# ADCS.net
KiCad netlist of a schematic drawn in EAGLE
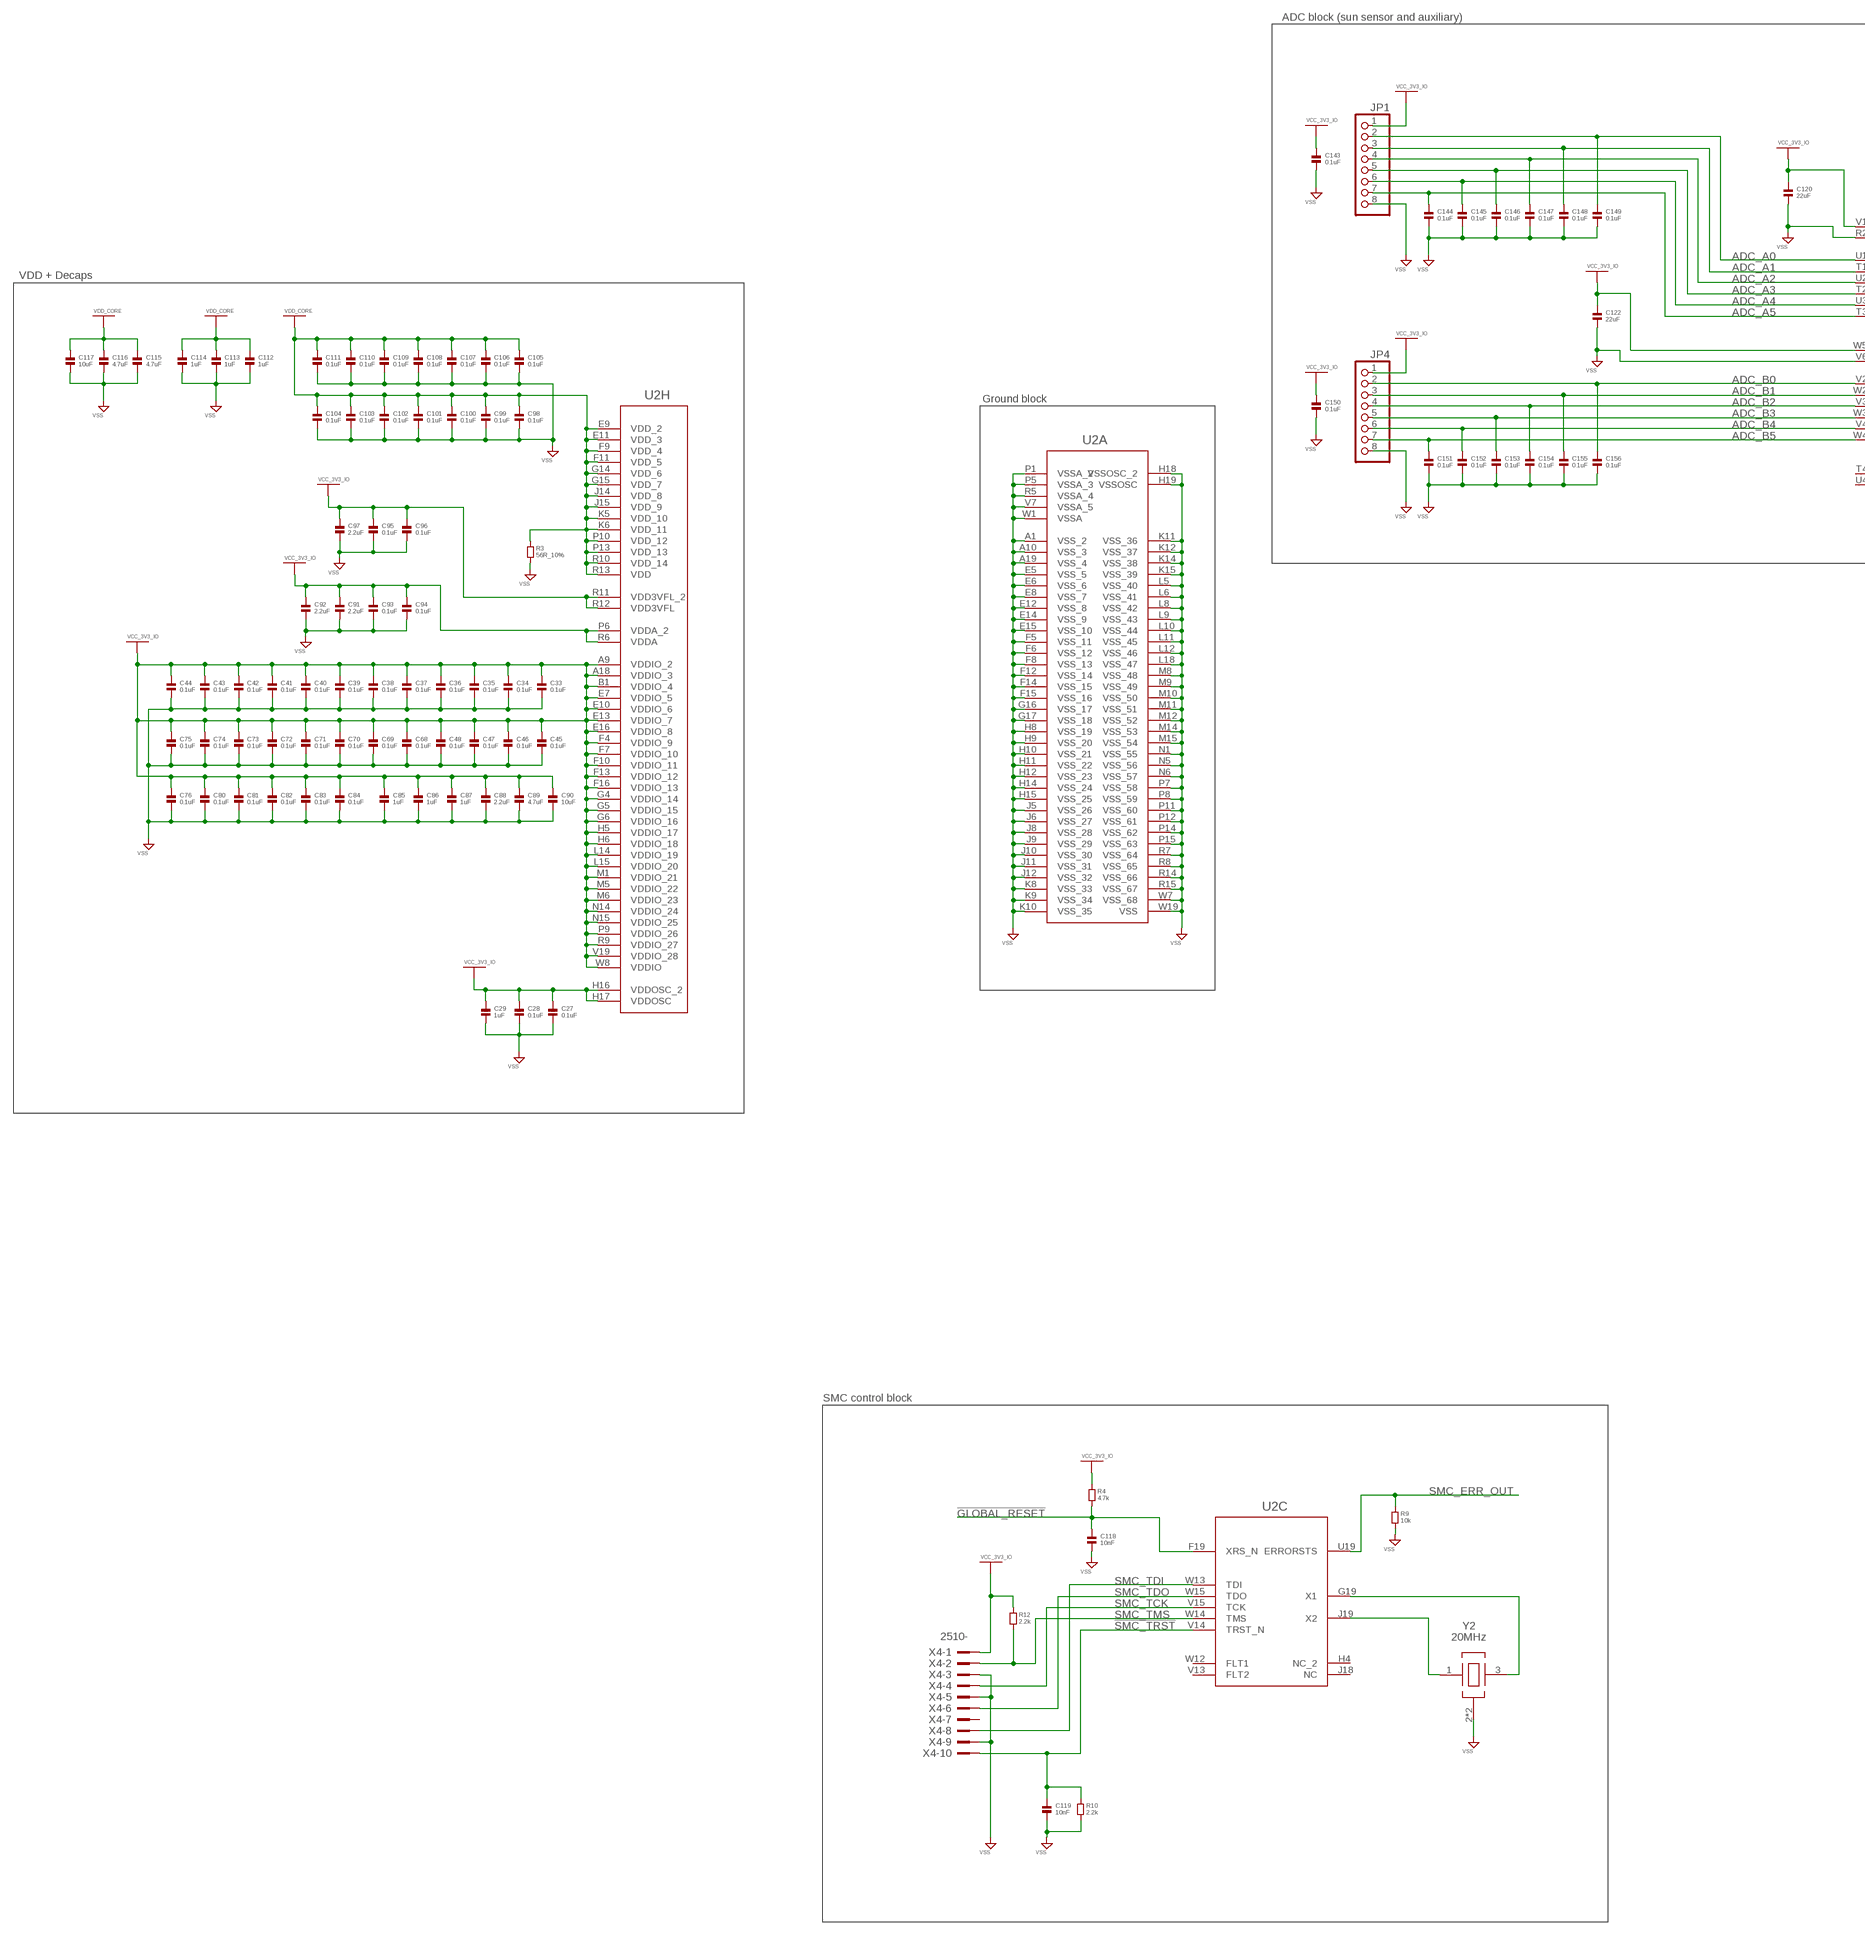
[diagram p0: schematic, sheet 1, part 1 of 2]
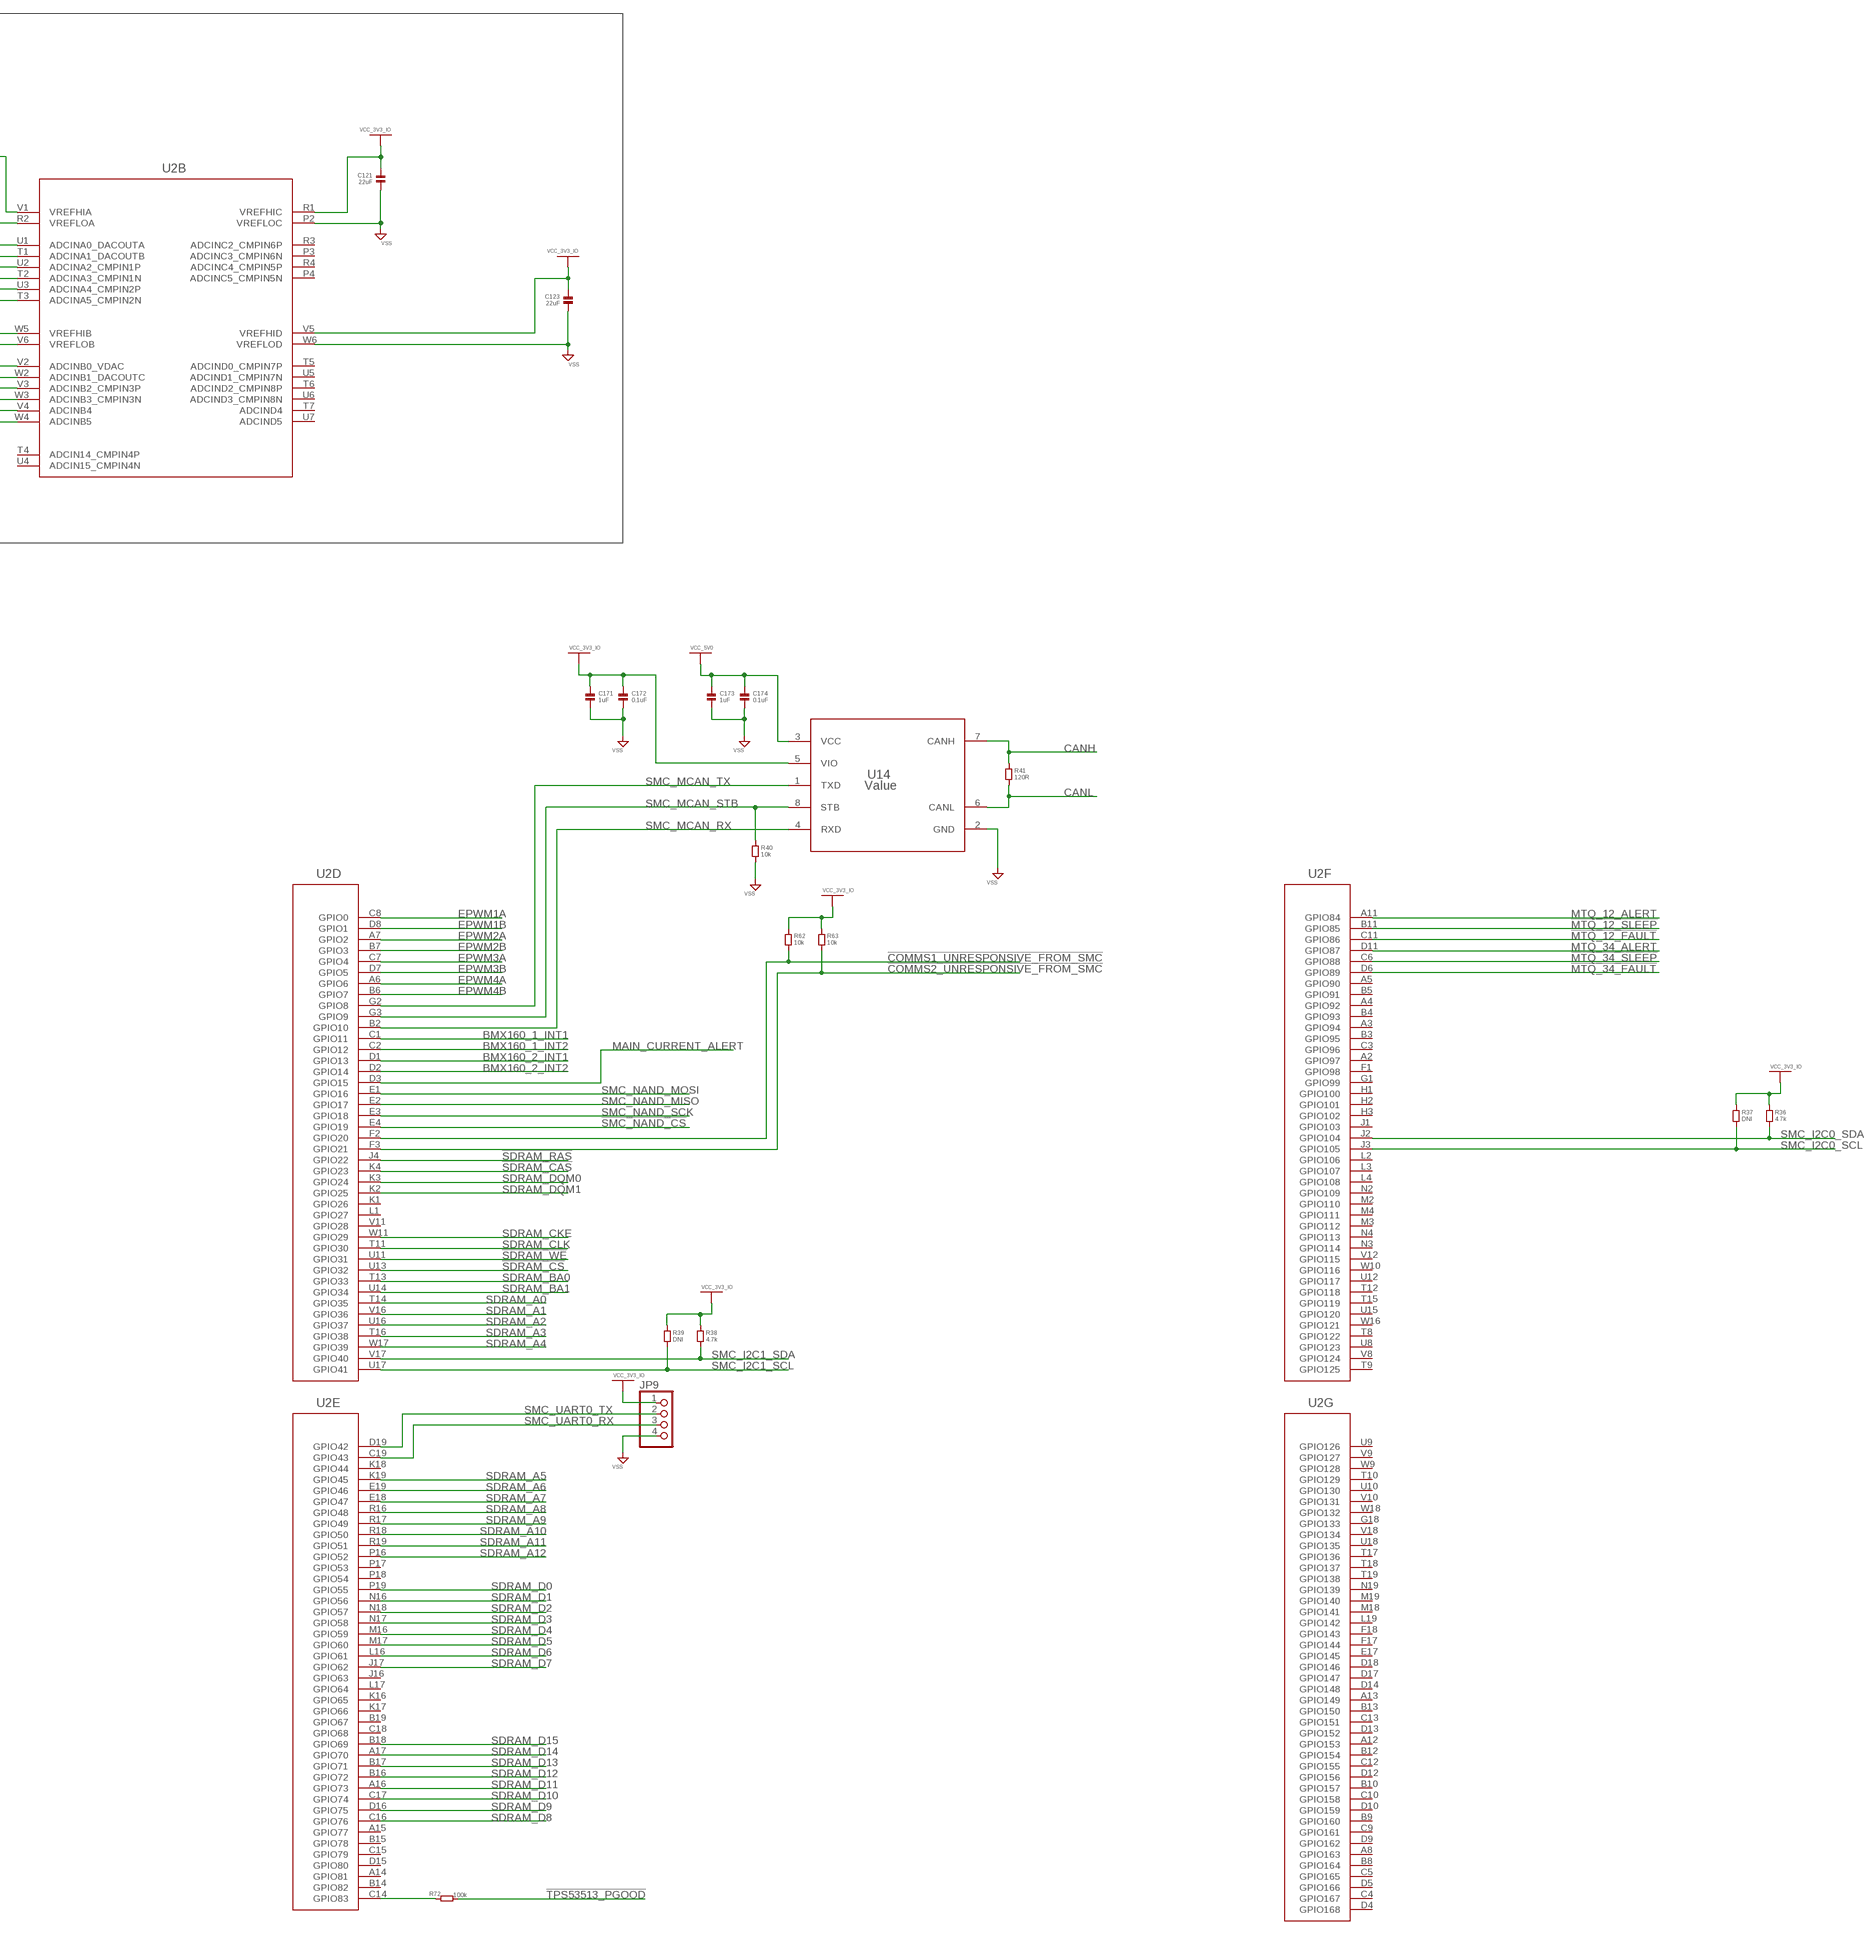
[diagram p1: schematic, sheet 1, part 2 of 2]
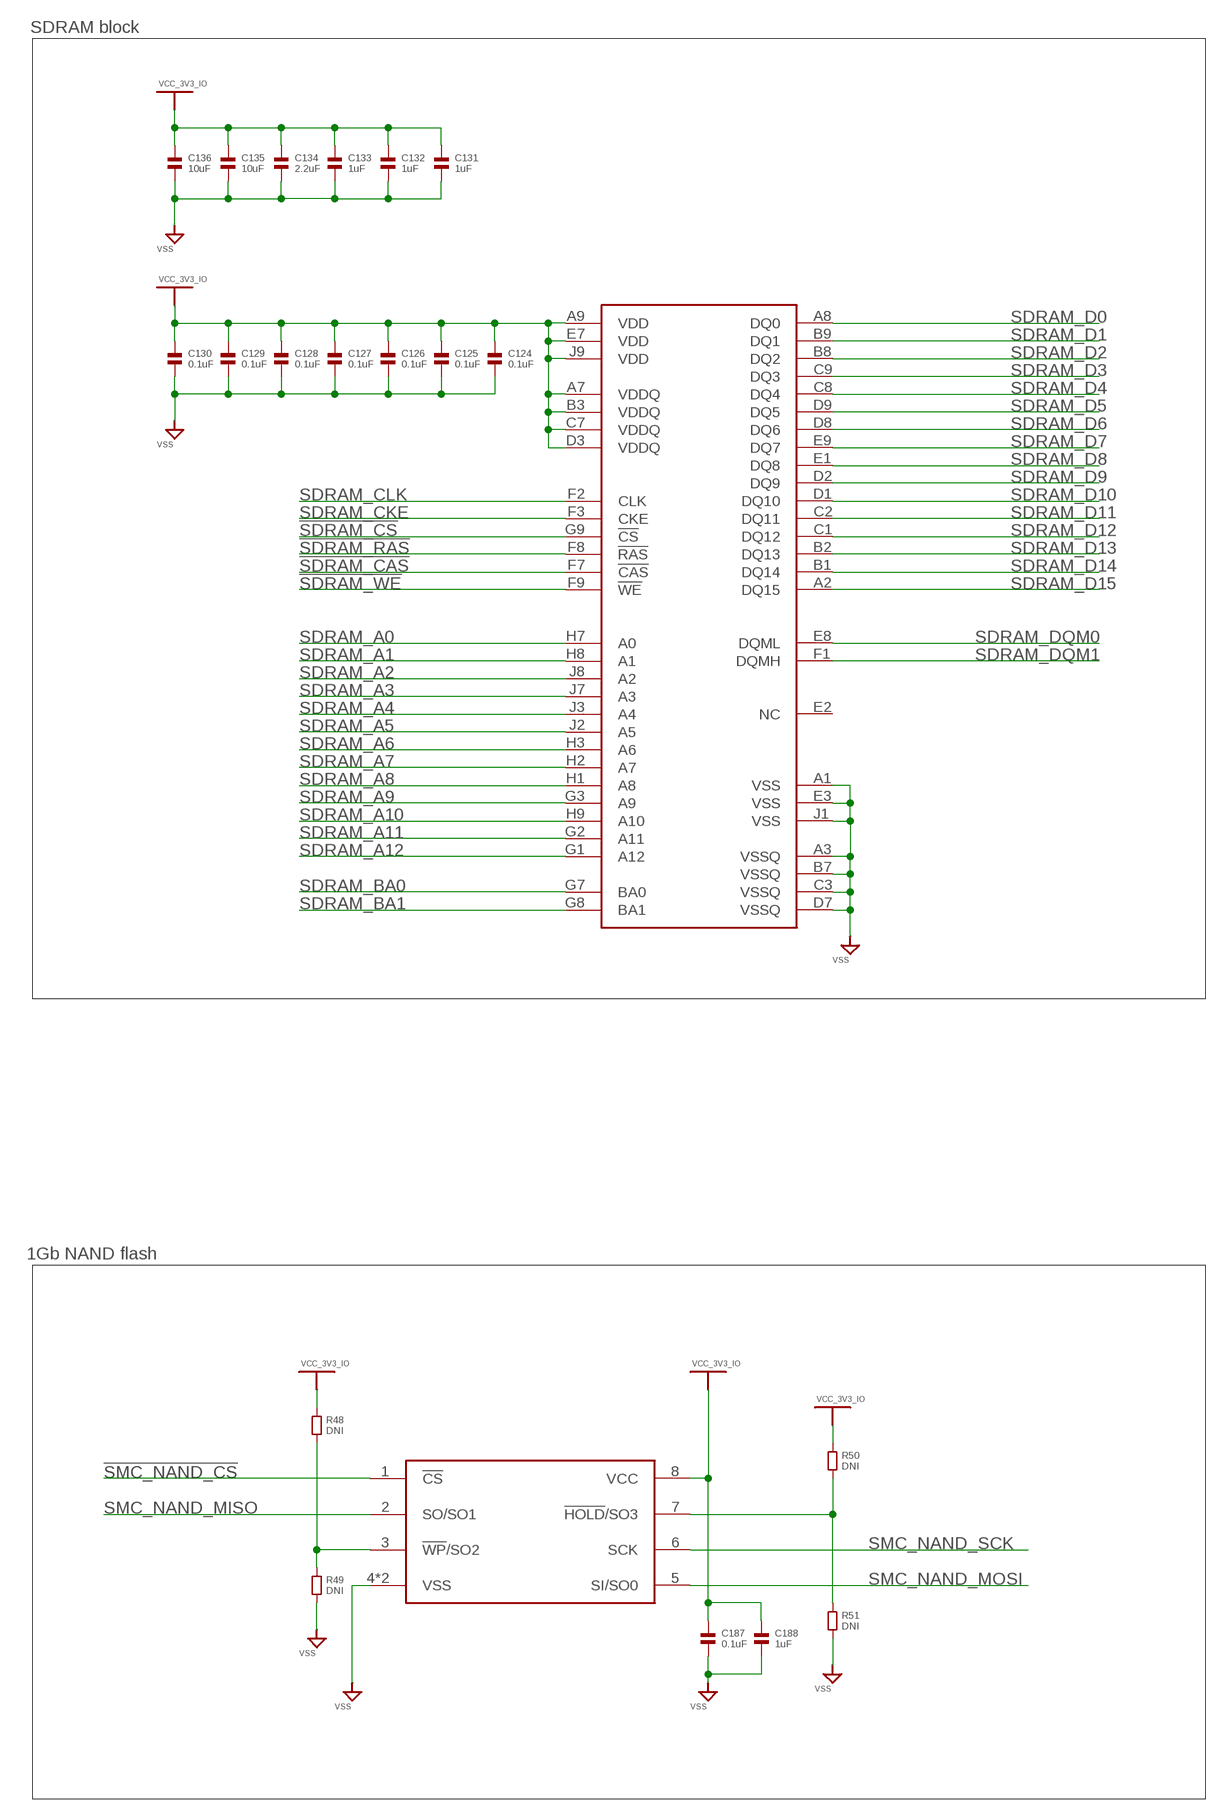
[diagram p2: schematic, sheet 2]
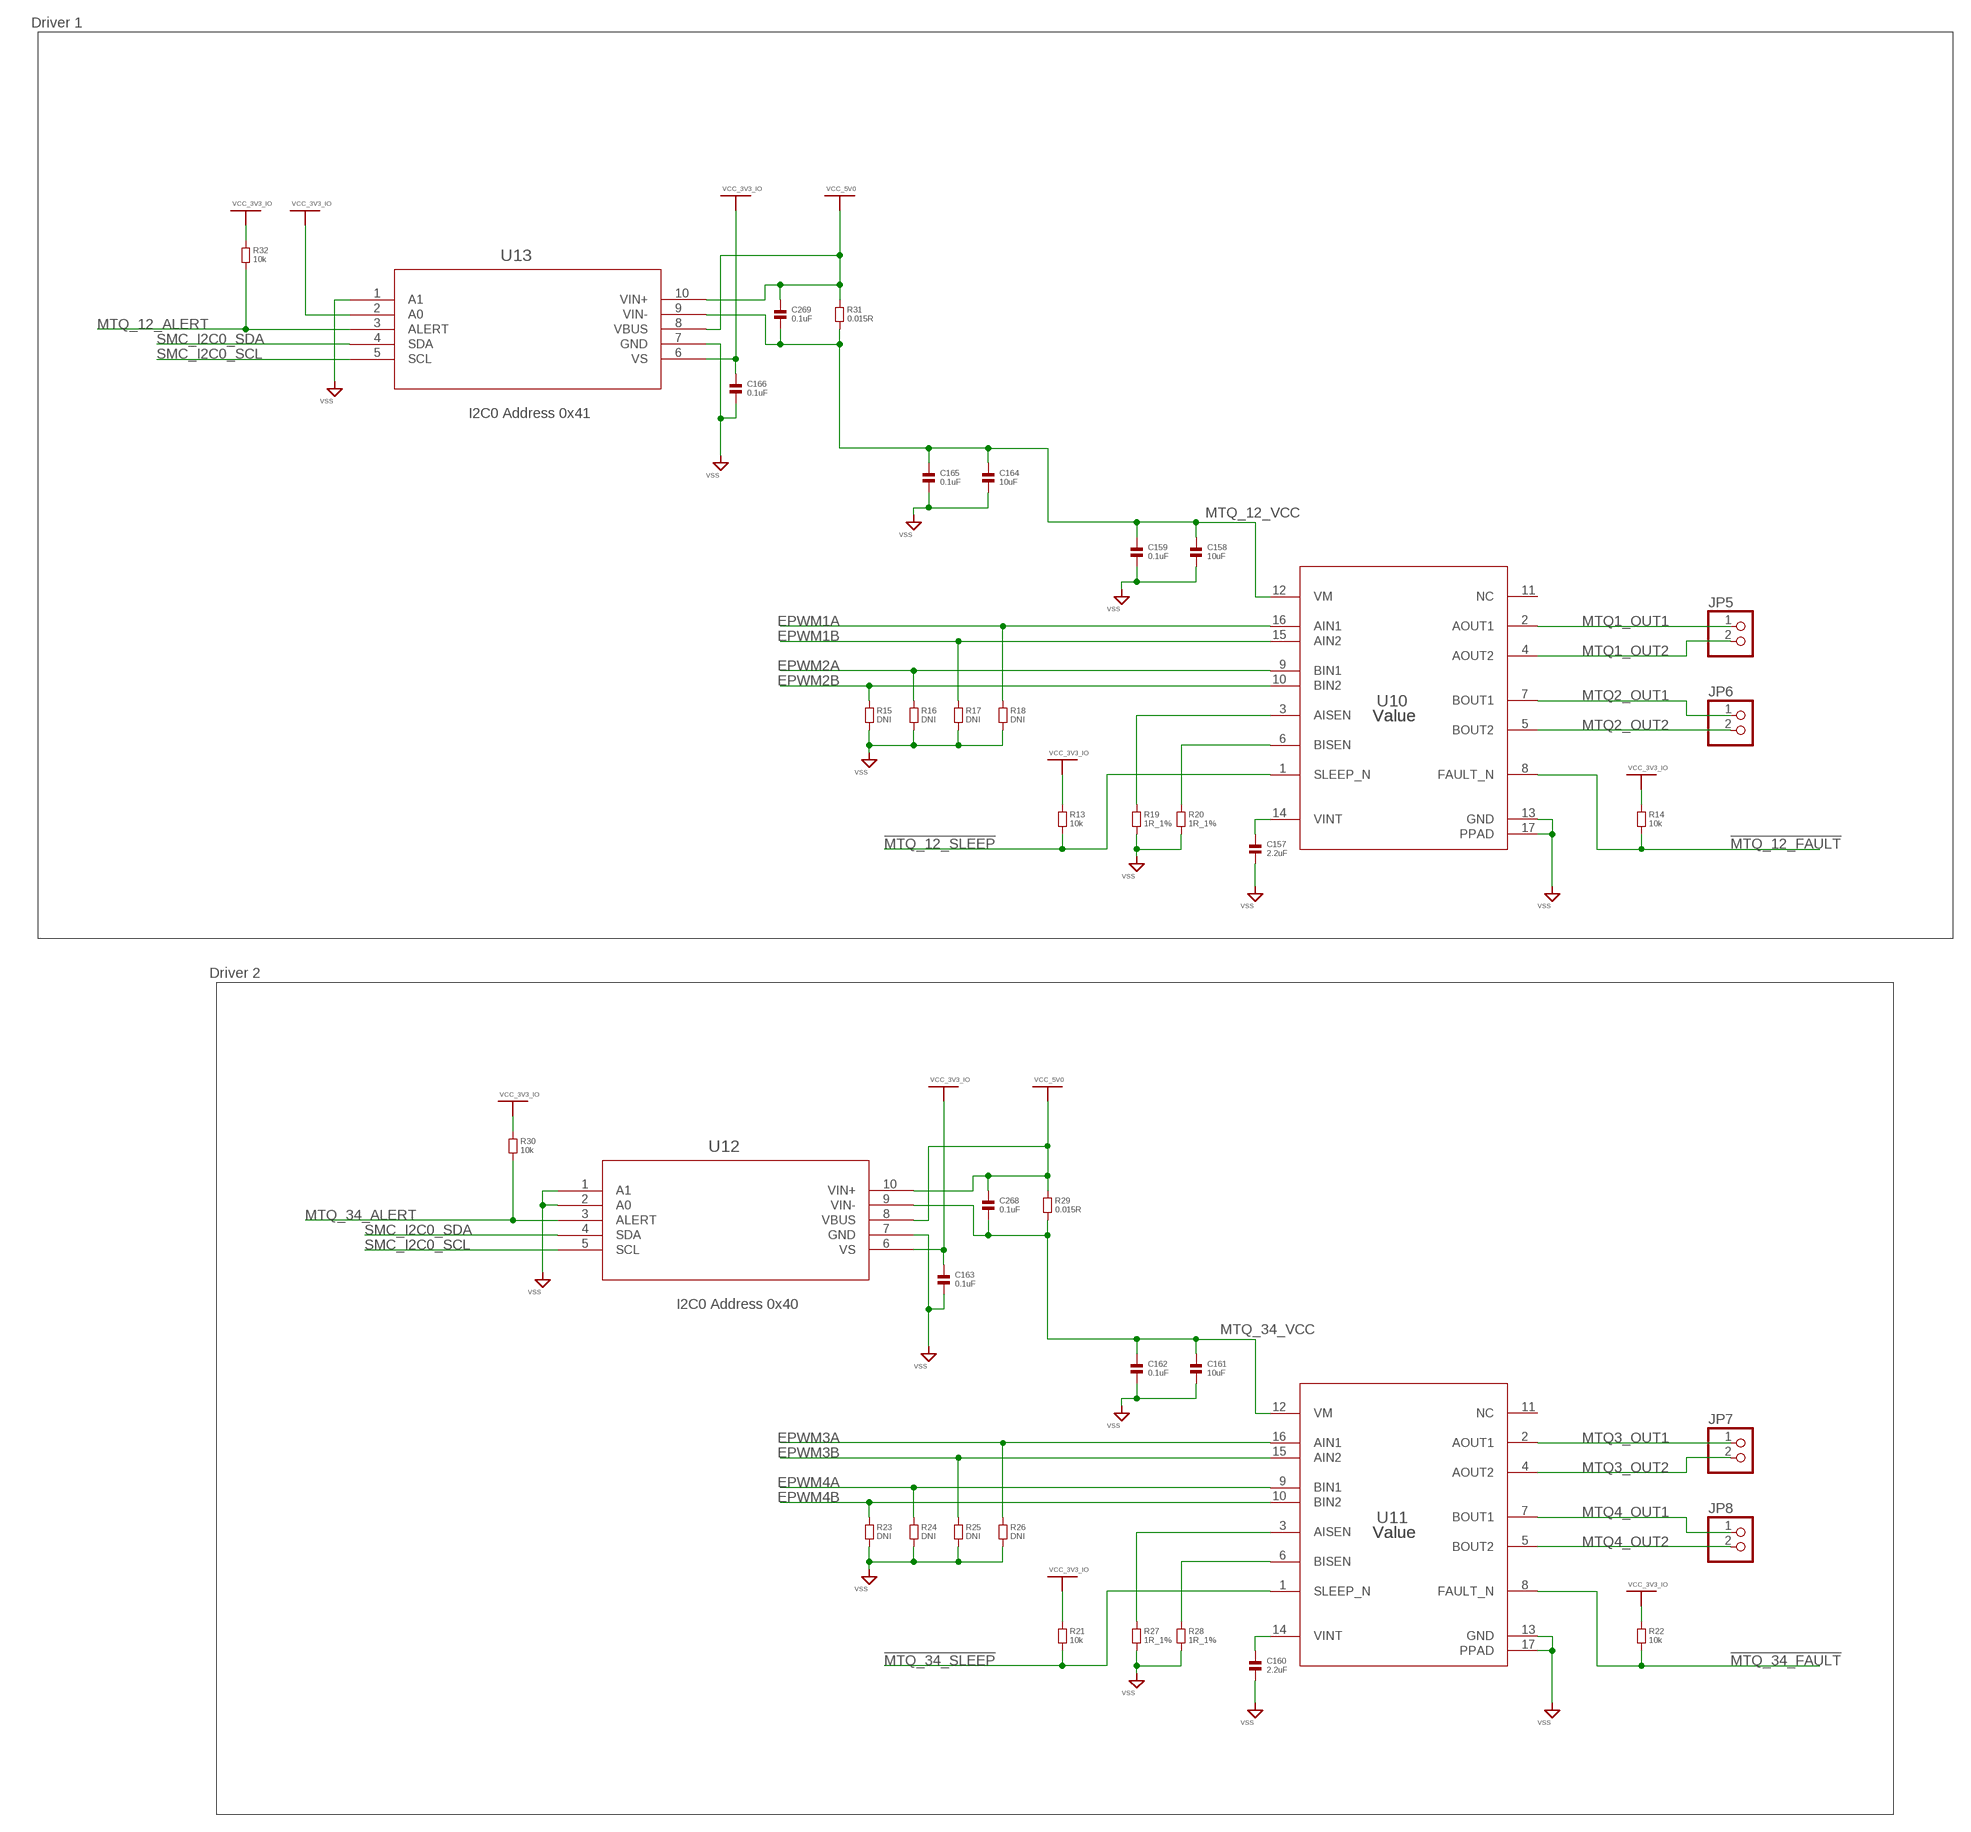
[diagram p3: schematic, sheet 3]
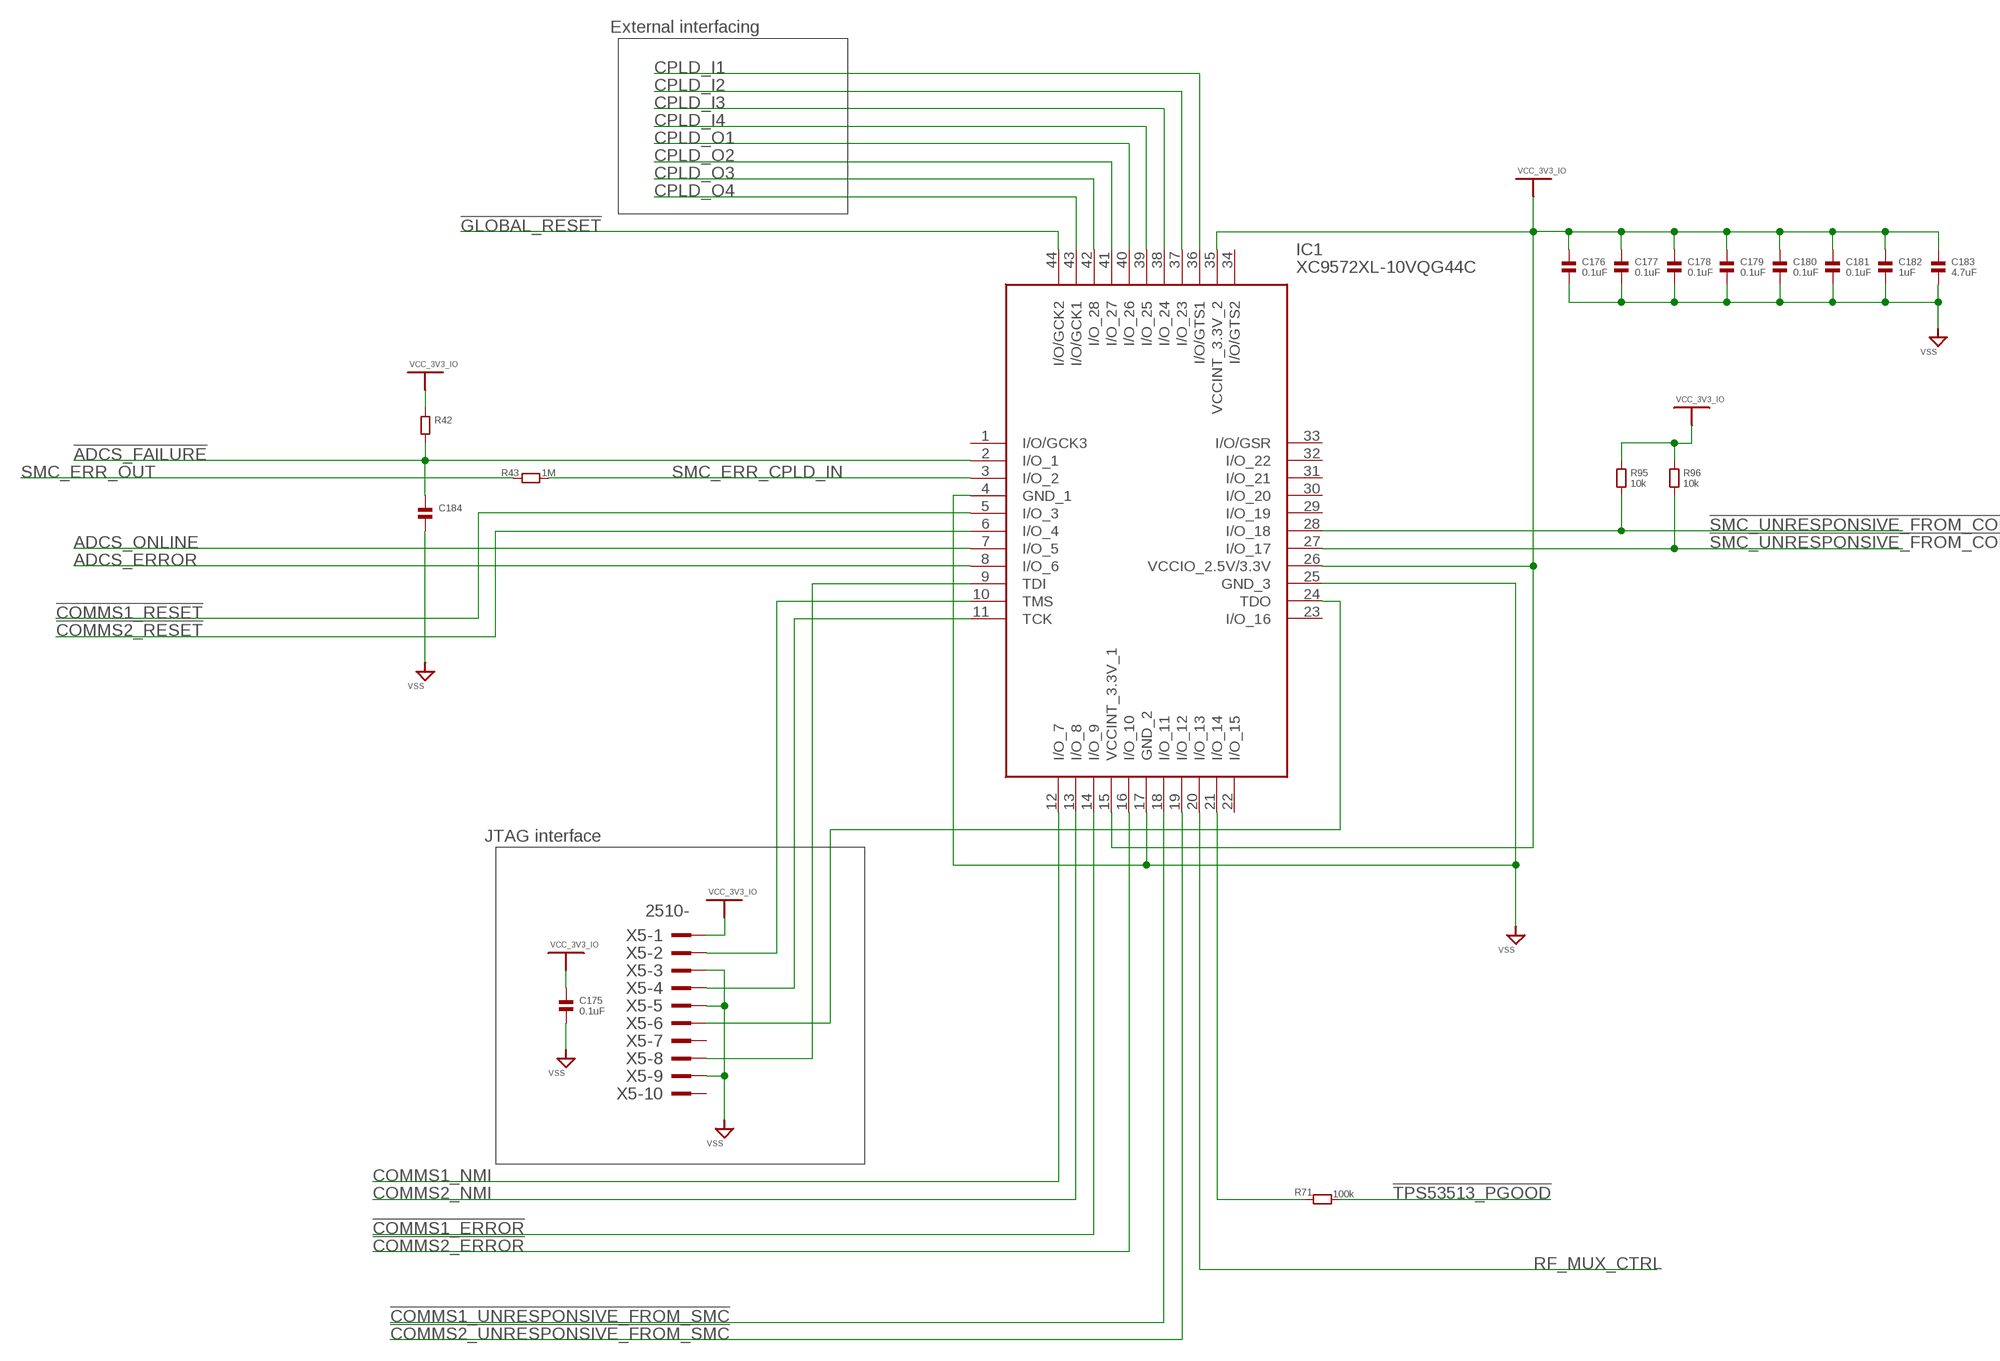
[diagram p4: schematic, sheet 4]
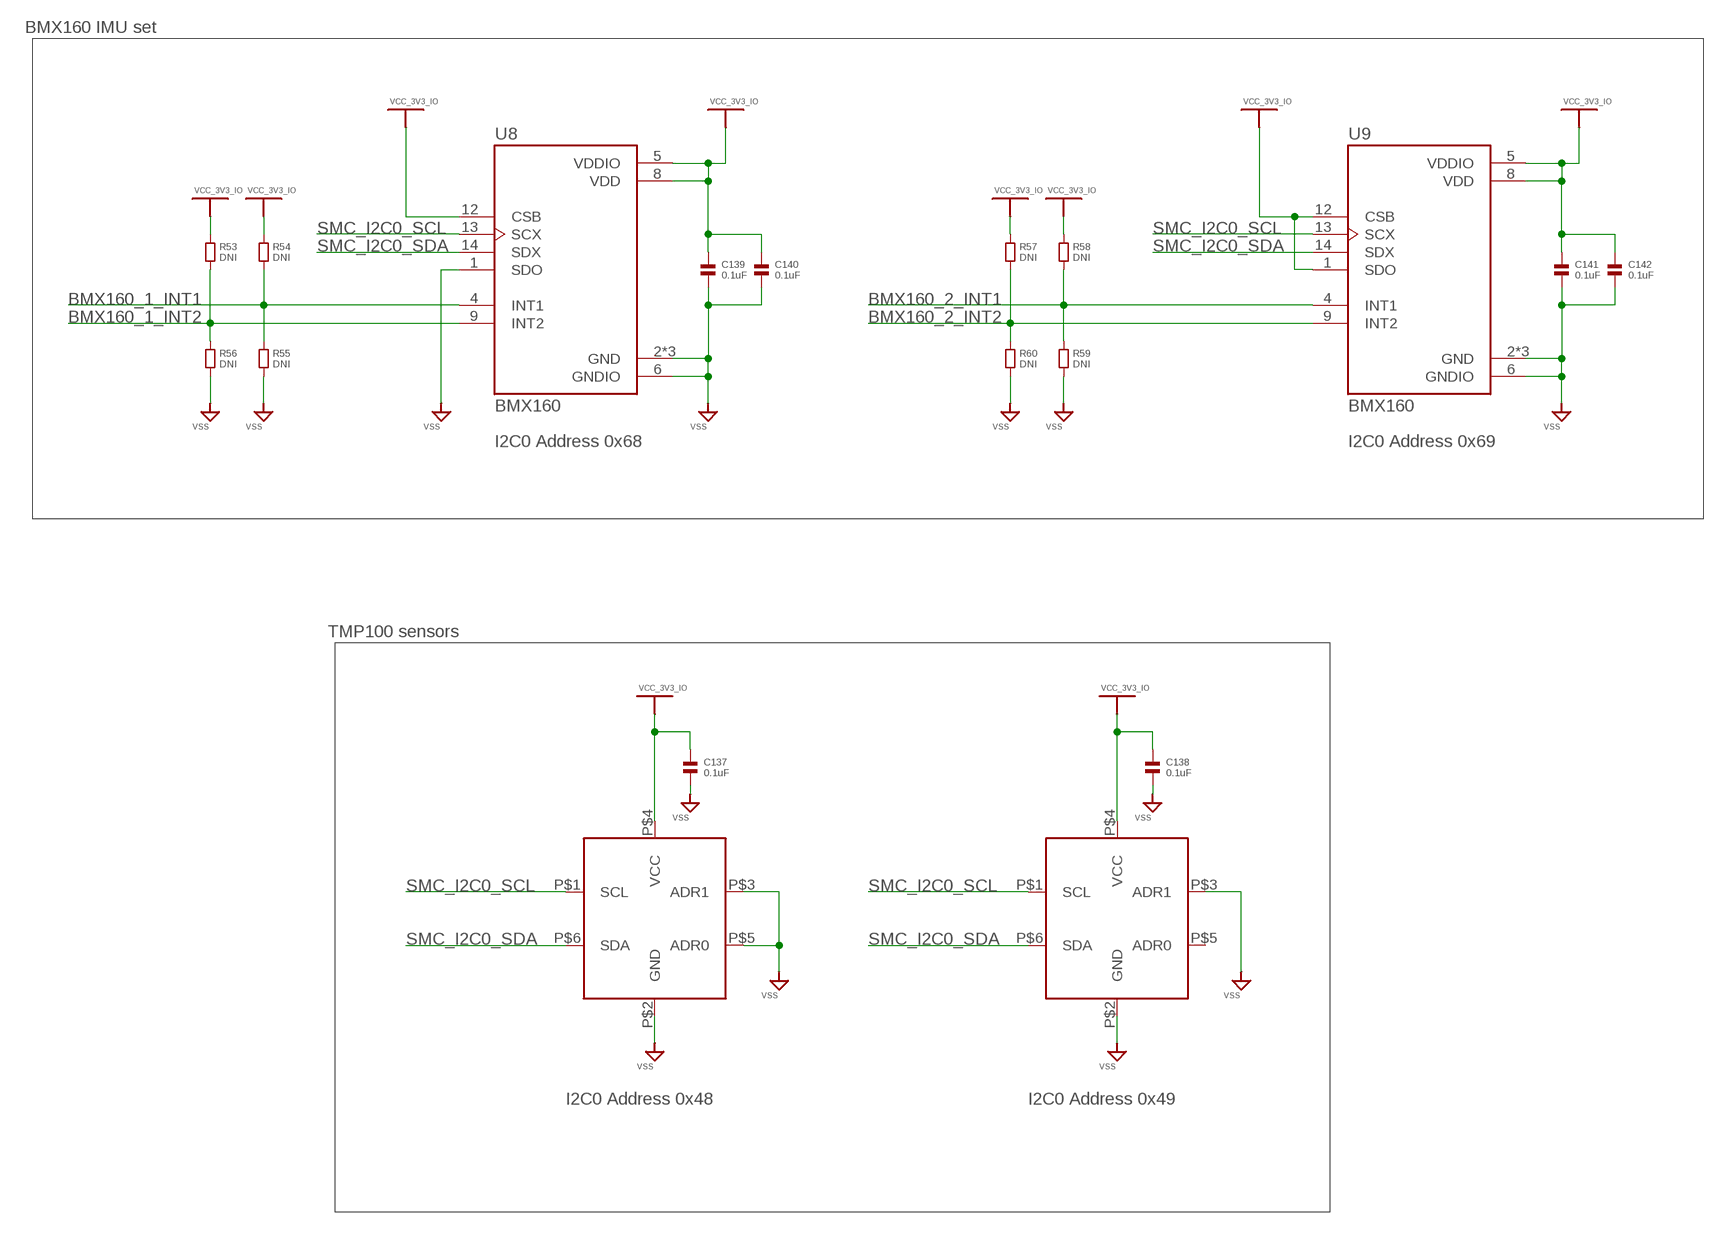
[diagram p5: schematic, sheet 5]
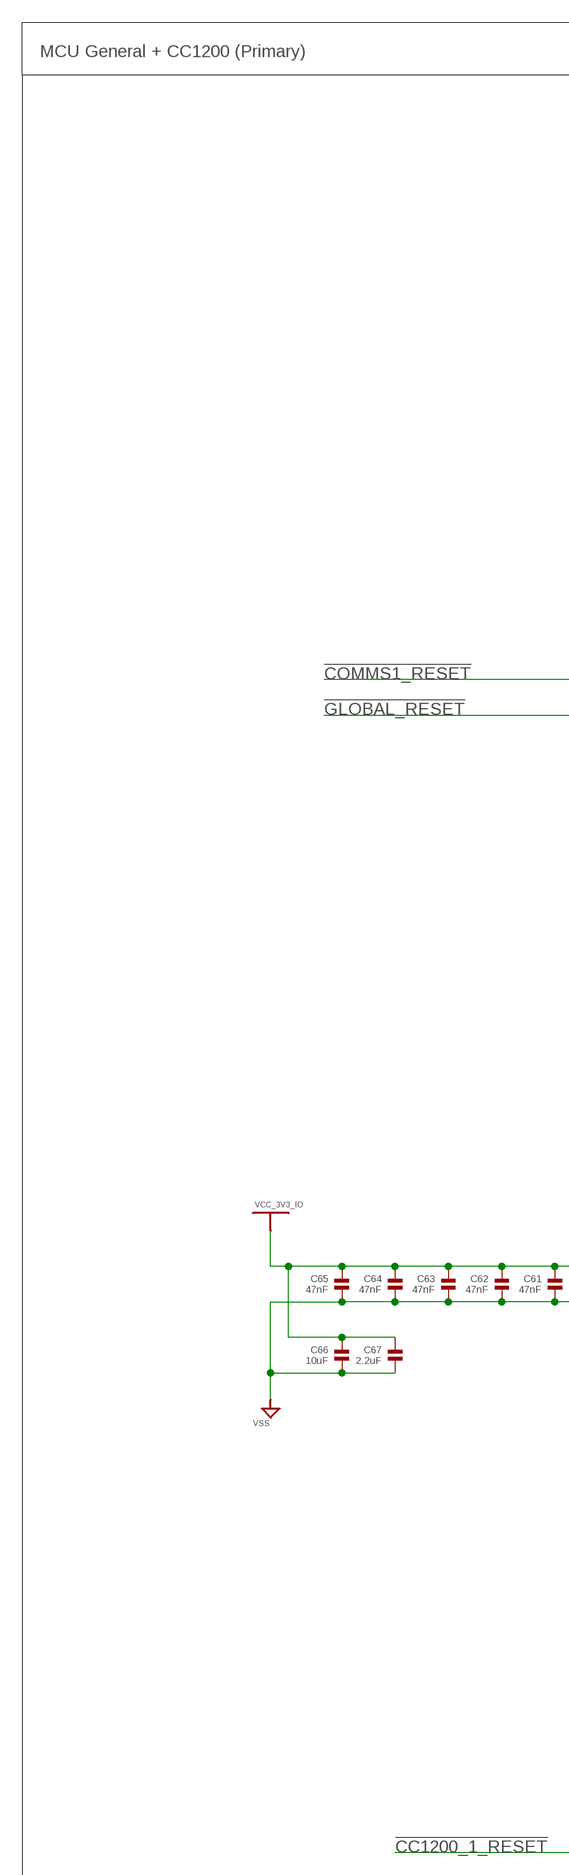
[diagram p6: schematic, sheet 6, part 1 of 2]
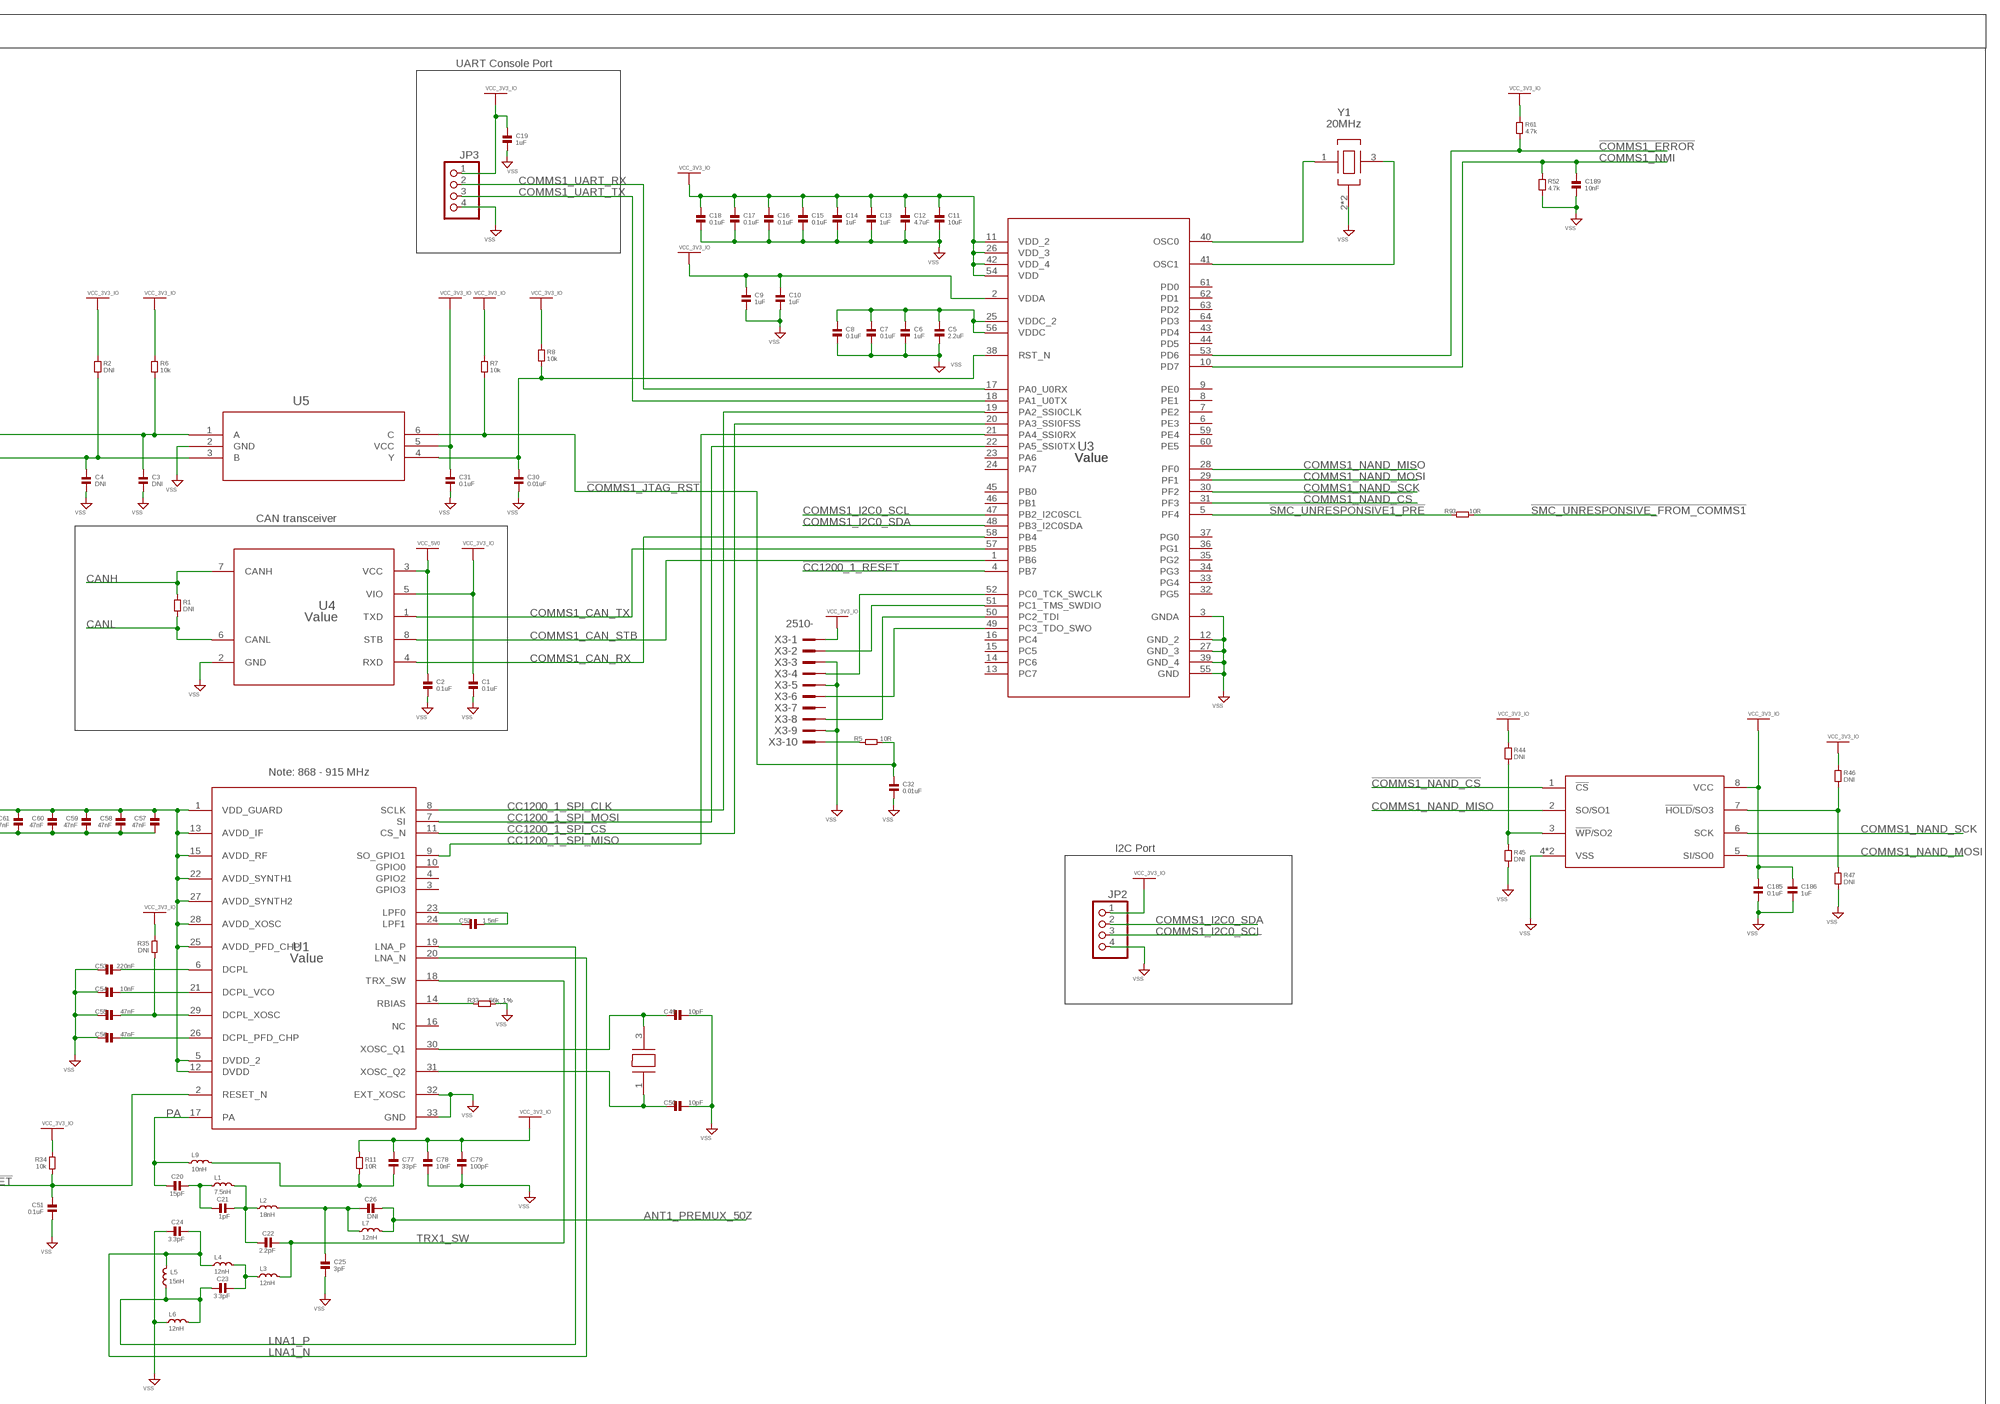
[diagram p7: schematic, sheet 6, part 2 of 2]
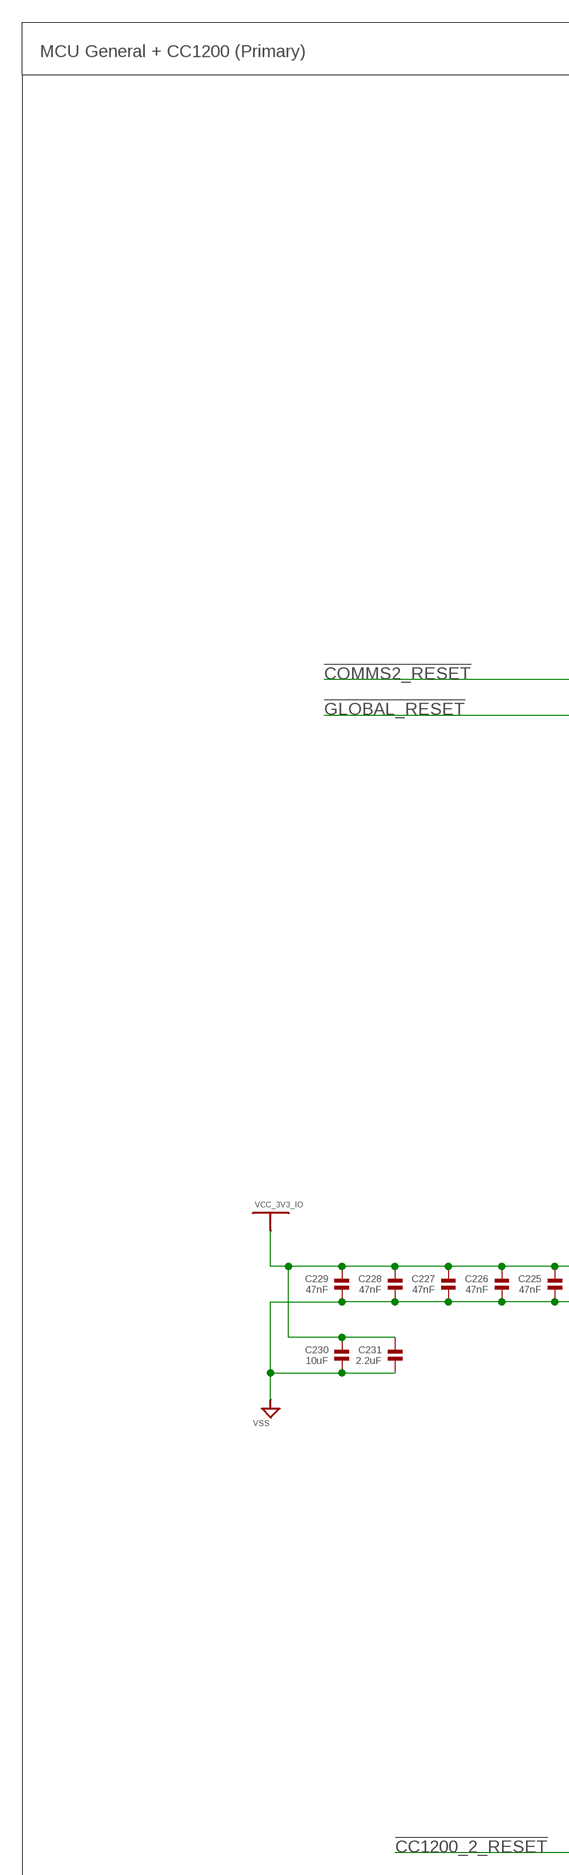
[diagram p8: schematic, sheet 7, part 1 of 2]
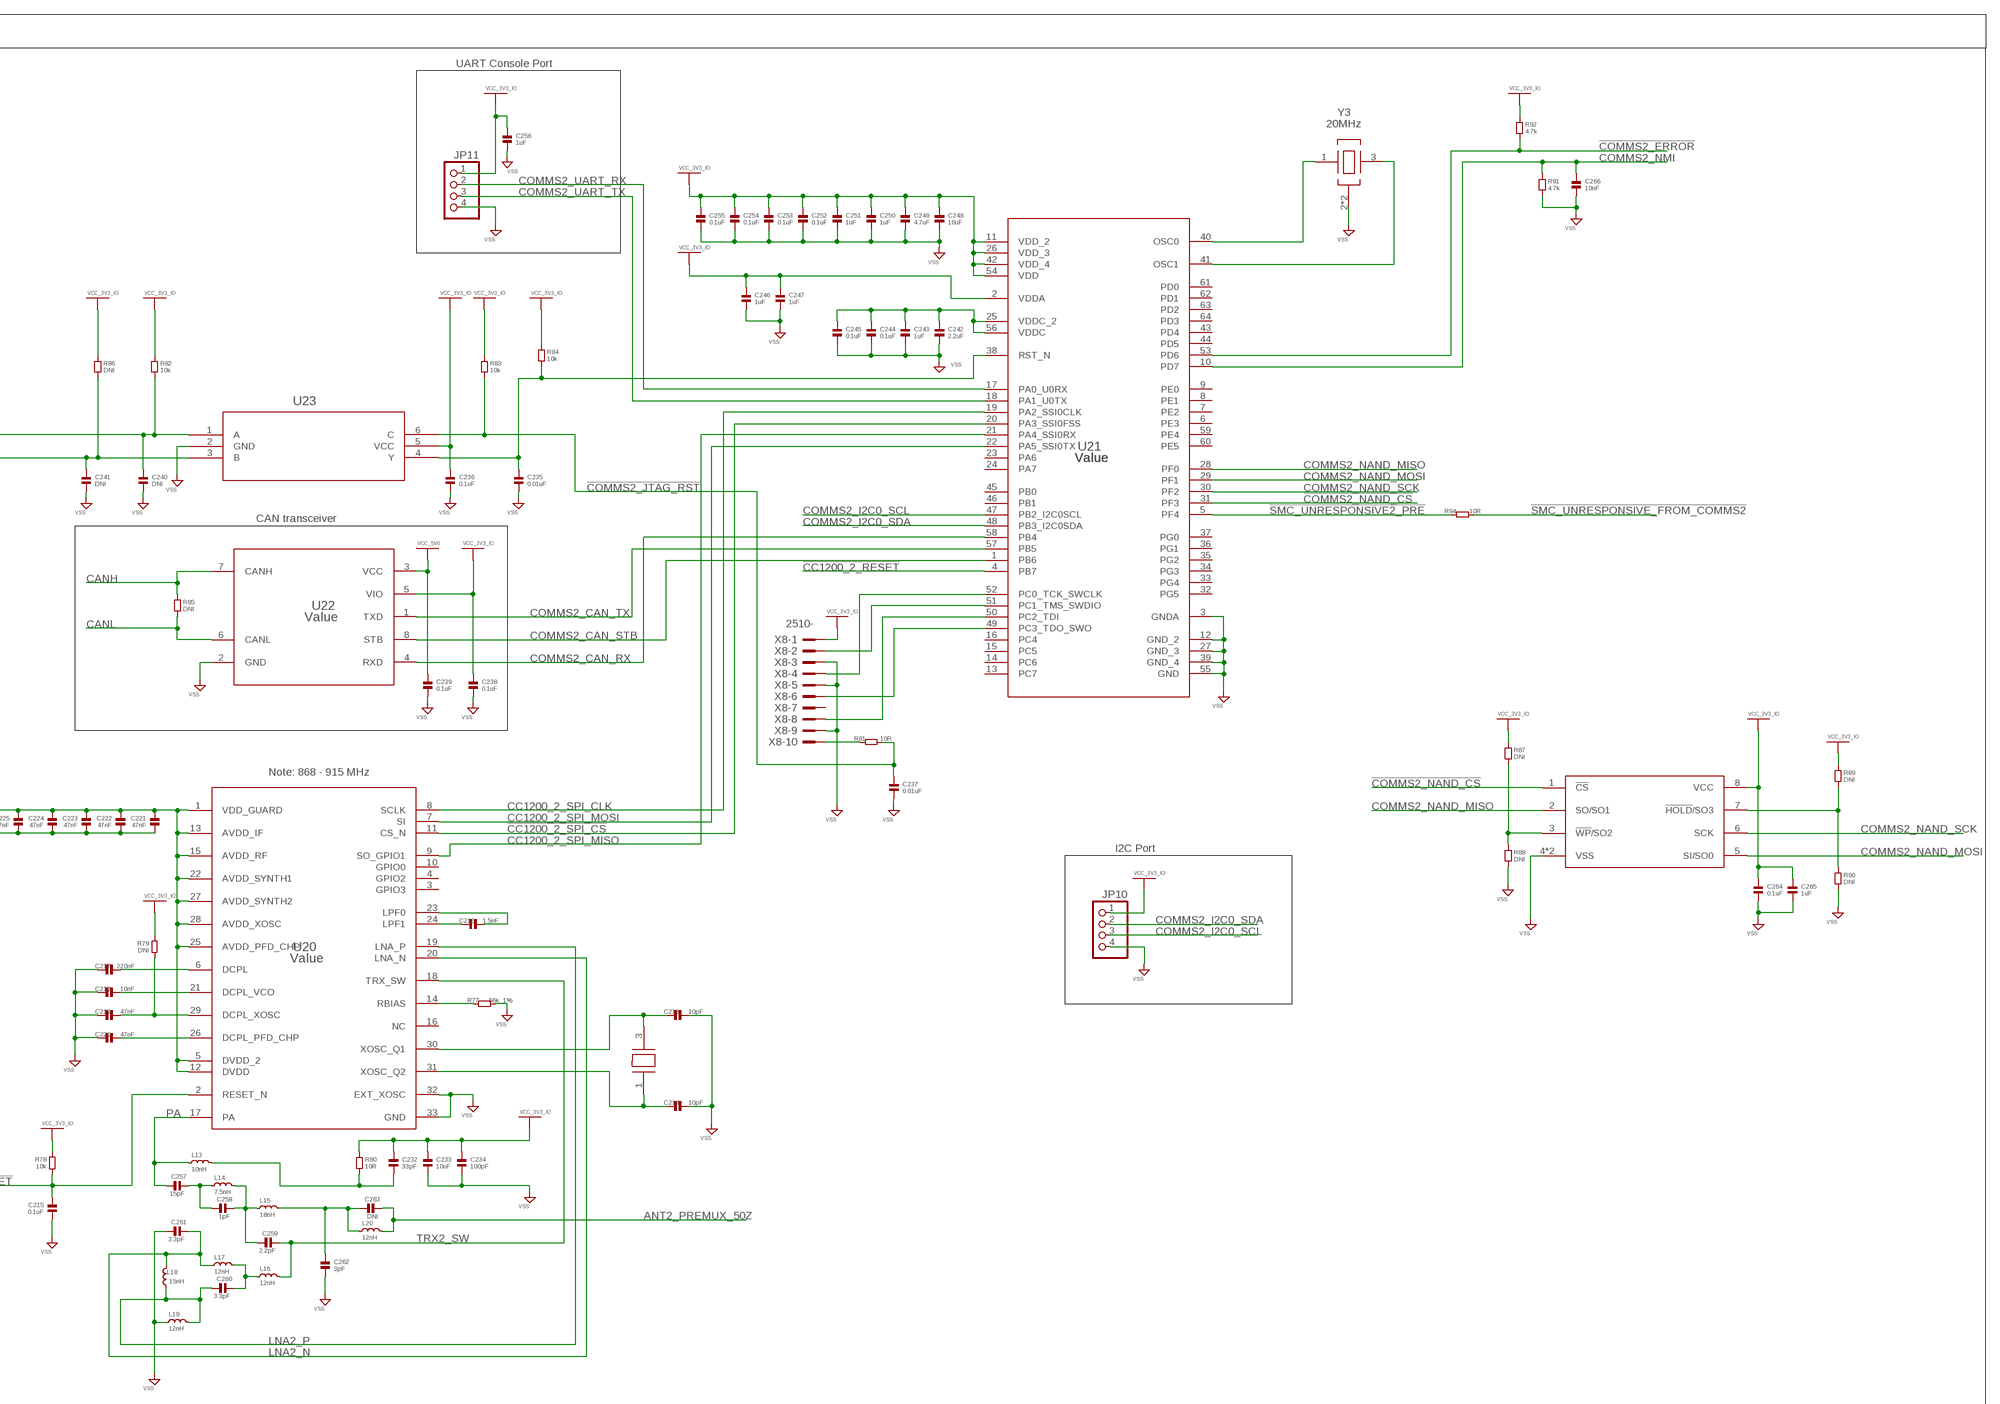
[diagram p9: schematic, sheet 7, part 2 of 2]
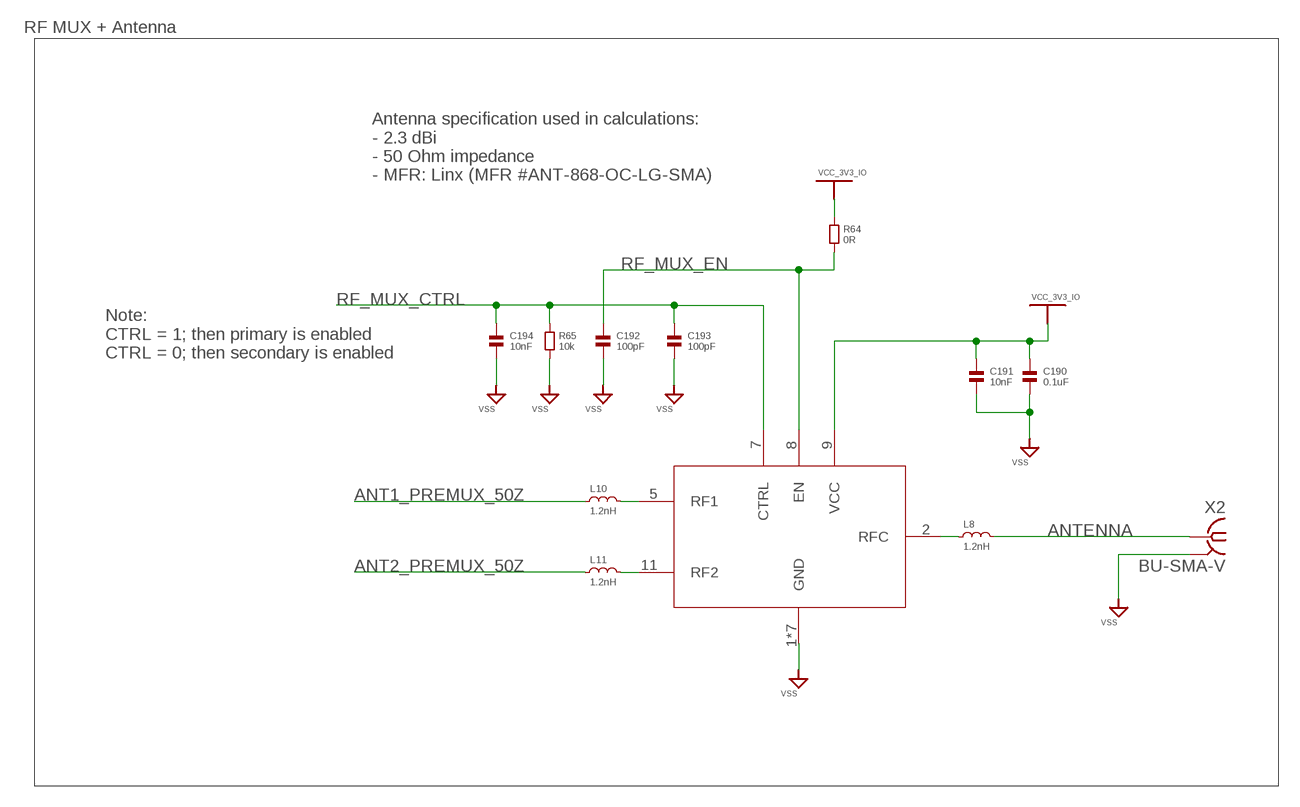
[diagram p10: schematic, sheet 8]
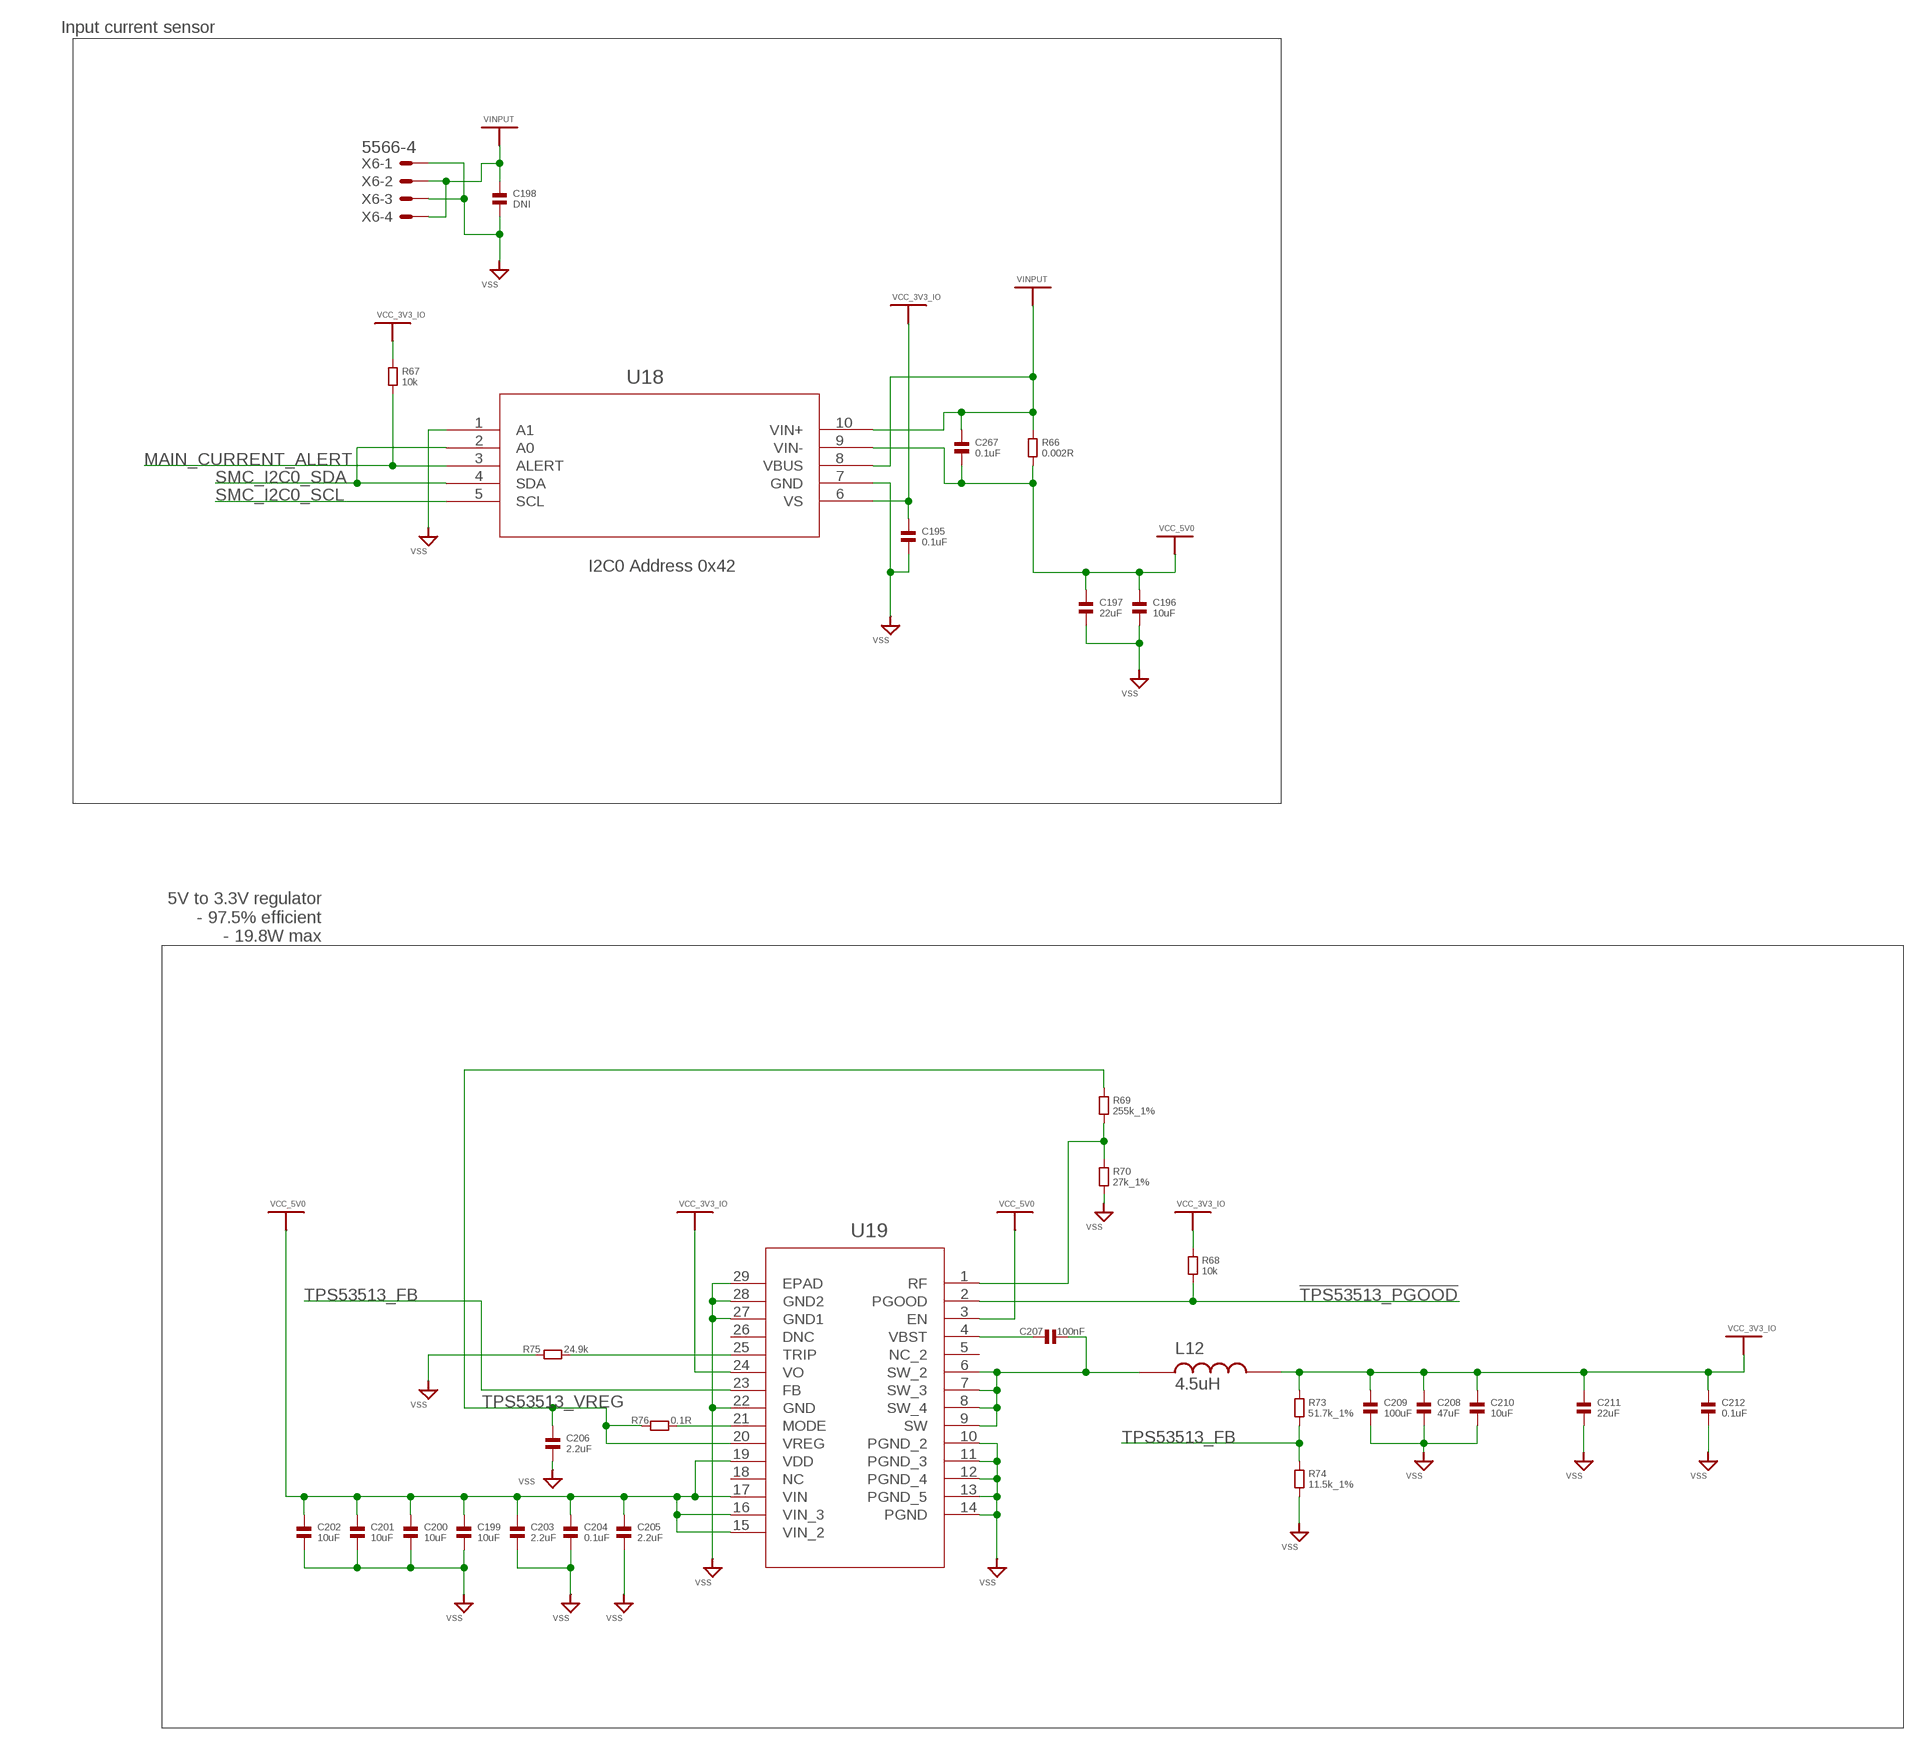
[diagram p11: schematic, sheet 9]
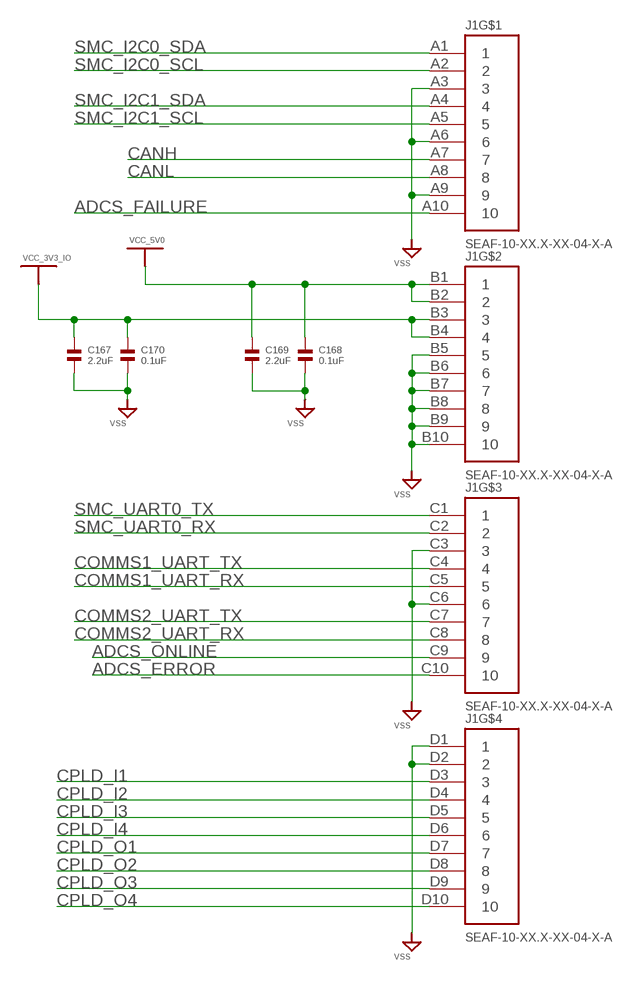
[diagram p12: schematic, sheet 10]

(export (version "E")
  (design (tool "Eeschema 10.0.6"))
  (components
    (comp (ref "C190")
      (value "0.1uF")
      (footprint "eagle-import:0603")
      (libsource (lib "eagle-import") (part "CAPACITOR.0603"))
    )
    (comp (ref "C191")
      (value "10nF")
      (footprint "eagle-import:0603")
      (libsource (lib "eagle-import") (part "CAPACITOR.0603"))
    )
    (comp (ref "C192")
      (value "100pF")
      (footprint "eagle-import:0603")
      (libsource (lib "eagle-import") (part "CAPACITOR.0603"))
    )
    (comp (ref "C193")
      (value "100pF")
      (footprint "eagle-import:0603")
      (libsource (lib "eagle-import") (part "CAPACITOR.0603"))
    )
    (comp (ref "C194")
      (value "10nF")
      (footprint "eagle-import:0603")
      (libsource (lib "eagle-import") (part "CAPACITOR.0603"))
    )
    (comp (ref "L8")
      (value "1.2nH")
      (footprint "eagle-import:0402")
      (libsource (lib "eagle-import") (part "RF-INDUCTOR.0402"))
    )
    (comp (ref "L10")
      (value "1.2nH")
      (footprint "eagle-import:0402")
      (libsource (lib "eagle-import") (part "RF-INDUCTOR.0402"))
    )
    (comp (ref "L11")
      (value "1.2nH")
      (footprint "eagle-import:0402")
      (libsource (lib "eagle-import") (part "RF-INDUCTOR.0402"))
    )
    (comp (ref "R64")
      (value "0R")
      (footprint "eagle-import:0603")
      (libsource (lib "eagle-import") (part "RESISTOR.0603"))
    )
    (comp (ref "R65")
      (value "10k")
      (footprint "eagle-import:0603")
      (libsource (lib "eagle-import") (part "RESISTOR.0603"))
    )
    (comp (ref "U17")
      (value "QORVO-RF_SWITCH-QPC7512")
      (footprint "eagle-import:QORVO-RF_SWITCH-QPC7512")
      (libsource (lib "eagle-import") (part "QORVO-RF_SWITCH-QPC7512"))
    )
    (comp (ref "X2")
      (value "BU-SMA-V")
      (footprint "eagle-import:BU-SMA-V")
      (libsource (lib "eagle-import") (part "BU-SMA-V"))
    )
    (comp (ref "C175")
      (value "0.1uF")
      (footprint "eagle-import:0603")
      (libsource (lib "eagle-import") (part "CAPACITOR.0603"))
    )
    (comp (ref "C176")
      (value "0.1uF")
      (footprint "eagle-import:0603")
      (libsource (lib "eagle-import") (part "CAPACITOR.0603"))
    )
    (comp (ref "C177")
      (value "0.1uF")
      (footprint "eagle-import:0603")
      (libsource (lib "eagle-import") (part "CAPACITOR.0603"))
    )
    (comp (ref "C178")
      (value "0.1uF")
      (footprint "eagle-import:0603")
      (libsource (lib "eagle-import") (part "CAPACITOR.0603"))
    )
    (comp (ref "C179")
      (value "0.1uF")
      (footprint "eagle-import:0603")
      (libsource (lib "eagle-import") (part "CAPACITOR.0603"))
    )
    (comp (ref "C180")
      (value "0.1uF")
      (footprint "eagle-import:0603")
      (libsource (lib "eagle-import") (part "CAPACITOR.0603"))
    )
    (comp (ref "C181")
      (value "0.1uF")
      (footprint "eagle-import:0603")
      (libsource (lib "eagle-import") (part "CAPACITOR.0603"))
    )
    (comp (ref "C182")
      (value "1uF")
      (footprint "eagle-import:0603")
      (libsource (lib "eagle-import") (part "CAPACITOR.0603"))
    )
    (comp (ref "C183")
      (value "4.7uF")
      (footprint "eagle-import:0603")
      (libsource (lib "eagle-import") (part "CAPACITOR.0603"))
    )
    (comp (ref "C184")
      (value "CAPACITOR.0603")
      (footprint "eagle-import:0603")
      (libsource (lib "eagle-import") (part "CAPACITOR.0603"))
    )
    (comp (ref "IC1")
      (value "XC9572XL-10VQG44C")
      (footprint "eagle-import:QFP80P1200X1200X120-44N")
      (libsource (lib "eagle-import") (part "XC9572XL-10VQG44C"))
    )
    (comp (ref "R42")
      (value "RESISTOR.0603")
      (footprint "eagle-import:0603")
      (libsource (lib "eagle-import") (part "RESISTOR.0603"))
    )
    (comp (ref "R43")
      (value "1M")
      (footprint "eagle-import:0603")
      (libsource (lib "eagle-import") (part "RESISTOR.0603"))
    )
    (comp (ref "R71")
      (value "100k")
      (footprint "eagle-import:0603")
      (libsource (lib "eagle-import") (part "RESISTOR.0603"))
    )
    (comp (ref "R95")
      (value "10k")
      (footprint "eagle-import:0603")
      (libsource (lib "eagle-import") (part "RESISTOR.0603"))
    )
    (comp (ref "R96")
      (value "10k")
      (footprint "eagle-import:0603")
      (libsource (lib "eagle-import") (part "RESISTOR.0603"))
    )
    (comp (ref "X5")
      (value "2510-")
      (footprint "eagle-import:PAK100_2500-10")
      (fields (field (name "MF") "3M") (field (name "MPN") "2510-6002UB"))
      (libsource (lib "eagle-import") (part "2510-"))
    )
    (comp (ref "C1")
      (value "0.1uF")
      (footprint "eagle-import:0603")
      (libsource (lib "eagle-import") (part "CAPACITOR.0603"))
    )
    (comp (ref "C2")
      (value "0.1uF")
      (footprint "eagle-import:0603")
      (libsource (lib "eagle-import") (part "CAPACITOR.0603"))
    )
    (comp (ref "C3")
      (value "DNI")
      (footprint "eagle-import:0603")
      (libsource (lib "eagle-import") (part "CAPACITOR.0603"))
    )
    (comp (ref "C4")
      (value "DNI")
      (footprint "eagle-import:0603")
      (libsource (lib "eagle-import") (part "CAPACITOR.0603"))
    )
    (comp (ref "C5")
      (value "2.2uF")
      (footprint "eagle-import:0603")
      (libsource (lib "eagle-import") (part "CAPACITOR.0603"))
    )
    (comp (ref "C6")
      (value "1uF")
      (footprint "eagle-import:0603")
      (libsource (lib "eagle-import") (part "CAPACITOR.0603"))
    )
    (comp (ref "C7")
      (value "0.1uF")
      (footprint "eagle-import:0603")
      (libsource (lib "eagle-import") (part "CAPACITOR.0603"))
    )
    (comp (ref "C8")
      (value "0.1uF")
      (footprint "eagle-import:0603")
      (libsource (lib "eagle-import") (part "CAPACITOR.0603"))
    )
    (comp (ref "C9")
      (value "1uF")
      (footprint "eagle-import:0603")
      (libsource (lib "eagle-import") (part "CAPACITOR.0603"))
    )
    (comp (ref "C10")
      (value "1uF")
      (footprint "eagle-import:0603")
      (libsource (lib "eagle-import") (part "CAPACITOR.0603"))
    )
    (comp (ref "C11")
      (value "10uF")
      (footprint "eagle-import:0603")
      (libsource (lib "eagle-import") (part "CAPACITOR.0603"))
    )
    (comp (ref "C12")
      (value "4.7uF")
      (footprint "eagle-import:0603")
      (libsource (lib "eagle-import") (part "CAPACITOR.0603"))
    )
    (comp (ref "C13")
      (value "1uF")
      (footprint "eagle-import:0603")
      (libsource (lib "eagle-import") (part "CAPACITOR.0603"))
    )
    (comp (ref "C14")
      (value "1uF")
      (footprint "eagle-import:0603")
      (libsource (lib "eagle-import") (part "CAPACITOR.0603"))
    )
    (comp (ref "C15")
      (value "0.1uF")
      (footprint "eagle-import:0603")
      (libsource (lib "eagle-import") (part "CAPACITOR.0603"))
    )
    (comp (ref "C16")
      (value "0.1uF")
      (footprint "eagle-import:0603")
      (libsource (lib "eagle-import") (part "CAPACITOR.0603"))
    )
    (comp (ref "C17")
      (value "0.1uF")
      (footprint "eagle-import:0603")
      (libsource (lib "eagle-import") (part "CAPACITOR.0603"))
    )
    (comp (ref "C18")
      (value "0.1uF")
      (footprint "eagle-import:0603")
      (libsource (lib "eagle-import") (part "CAPACITOR.0603"))
    )
    (comp (ref "C19")
      (value "1uF")
      (footprint "eagle-import:0603")
      (libsource (lib "eagle-import") (part "CAPACITOR.0603"))
    )
    (comp (ref "C20")
      (value "15pF")
      (footprint "eagle-import:0402")
      (libsource (lib "eagle-import") (part "CAPACITOR.0402"))
    )
    (comp (ref "C21")
      (value "1pF")
      (footprint "eagle-import:0402")
      (libsource (lib "eagle-import") (part "CAPACITOR.0402"))
    )
    (comp (ref "C22")
      (value "2.2pF")
      (footprint "eagle-import:0402")
      (libsource (lib "eagle-import") (part "CAPACITOR.0402"))
    )
    (comp (ref "C23")
      (value "3.3pF")
      (footprint "eagle-import:0402")
      (libsource (lib "eagle-import") (part "CAPACITOR.0402"))
    )
    (comp (ref "C24")
      (value "3.3pF")
      (footprint "eagle-import:0402")
      (libsource (lib "eagle-import") (part "CAPACITOR.0402"))
    )
    (comp (ref "C25")
      (value "3pF")
      (footprint "eagle-import:0402")
      (libsource (lib "eagle-import") (part "CAPACITOR.0402"))
    )
    (comp (ref "C26")
      (value "DNI")
      (footprint "eagle-import:0402")
      (libsource (lib "eagle-import") (part "CAPACITOR.0402"))
    )
    (comp (ref "C30")
      (value "0.01uF")
      (footprint "eagle-import:0603")
      (libsource (lib "eagle-import") (part "CAPACITOR.0603"))
    )
    (comp (ref "C31")
      (value "0.1uF")
      (footprint "eagle-import:0603")
      (libsource (lib "eagle-import") (part "CAPACITOR.0603"))
    )
    (comp (ref "C32")
      (value "0.01uF")
      (footprint "eagle-import:0603")
      (libsource (lib "eagle-import") (part "CAPACITOR.0603"))
    )
    (comp (ref "C49")
      (value "10pF")
      (footprint "eagle-import:0603")
      (libsource (lib "eagle-import") (part "CAPACITOR.0603"))
    )
    (comp (ref "C50")
      (value "10pF")
      (footprint "eagle-import:0603")
      (libsource (lib "eagle-import") (part "CAPACITOR.0603"))
    )
    (comp (ref "C51")
      (value "0.1uF")
      (footprint "eagle-import:0603")
      (libsource (lib "eagle-import") (part "CAPACITOR.0603"))
    )
    (comp (ref "C52")
      (value "1.5nF")
      (footprint "eagle-import:0402")
      (libsource (lib "eagle-import") (part "CAPACITOR.0402"))
    )
    (comp (ref "C53")
      (value "220nF")
      (footprint "eagle-import:0402")
      (libsource (lib "eagle-import") (part "CAPACITOR.0402"))
    )
    (comp (ref "C54")
      (value "10nF")
      (footprint "eagle-import:0402")
      (libsource (lib "eagle-import") (part "CAPACITOR.0402"))
    )
    (comp (ref "C55")
      (value "47nF")
      (footprint "eagle-import:0402")
      (libsource (lib "eagle-import") (part "CAPACITOR.0402"))
    )
    (comp (ref "C56")
      (value "47nF")
      (footprint "eagle-import:0402")
      (libsource (lib "eagle-import") (part "CAPACITOR.0402"))
    )
    (comp (ref "C57")
      (value "47nF")
      (footprint "eagle-import:0402")
      (libsource (lib "eagle-import") (part "CAPACITOR.0402"))
    )
    (comp (ref "C58")
      (value "47nF")
      (footprint "eagle-import:0402")
      (libsource (lib "eagle-import") (part "CAPACITOR.0402"))
    )
    (comp (ref "C59")
      (value "47nF")
      (footprint "eagle-import:0402")
      (libsource (lib "eagle-import") (part "CAPACITOR.0402"))
    )
    (comp (ref "C60")
      (value "47nF")
      (footprint "eagle-import:0402")
      (libsource (lib "eagle-import") (part "CAPACITOR.0402"))
    )
    (comp (ref "C61")
      (value "47nF")
      (footprint "eagle-import:0402")
      (libsource (lib "eagle-import") (part "CAPACITOR.0402"))
    )
    (comp (ref "C62")
      (value "47nF")
      (footprint "eagle-import:0402")
      (libsource (lib "eagle-import") (part "CAPACITOR.0402"))
    )
    (comp (ref "C63")
      (value "47nF")
      (footprint "eagle-import:0402")
      (libsource (lib "eagle-import") (part "CAPACITOR.0402"))
    )
    (comp (ref "C64")
      (value "47nF")
      (footprint "eagle-import:0402")
      (libsource (lib "eagle-import") (part "CAPACITOR.0402"))
    )
    (comp (ref "C65")
      (value "47nF")
      (footprint "eagle-import:0402")
      (libsource (lib "eagle-import") (part "CAPACITOR.0402"))
    )
    (comp (ref "C66")
      (value "10uF")
      (footprint "eagle-import:0603")
      (libsource (lib "eagle-import") (part "CAPACITOR.0603"))
    )
    (comp (ref "C67")
      (value "2.2uF")
      (footprint "eagle-import:0603")
      (libsource (lib "eagle-import") (part "CAPACITOR.0603"))
    )
    (comp (ref "C77")
      (value "33pF")
      (footprint "eagle-import:0402")
      (libsource (lib "eagle-import") (part "CAPACITOR.0402"))
    )
    (comp (ref "C78")
      (value "10nF")
      (footprint "eagle-import:0402")
      (libsource (lib "eagle-import") (part "CAPACITOR.0402"))
    )
    (comp (ref "C79")
      (value "100pF")
      (footprint "eagle-import:0402")
      (libsource (lib "eagle-import") (part "CAPACITOR.0402"))
    )
    (comp (ref "C185")
      (value "0.1uF")
      (footprint "eagle-import:0603")
      (libsource (lib "eagle-import") (part "CAPACITOR.0603"))
    )
    (comp (ref "C186")
      (value "1uF")
      (footprint "eagle-import:0603")
      (libsource (lib "eagle-import") (part "CAPACITOR.0603"))
    )
    (comp (ref "C189")
      (value "10nF")
      (footprint "eagle-import:0603")
      (libsource (lib "eagle-import") (part "CAPACITOR.0603"))
    )
    (comp (ref "JP2")
      (value "PINHD-1X4")
      (footprint "eagle-import:1X04")
      (libsource (lib "eagle-import") (part "PINHD-1X4"))
    )
    (comp (ref "JP3")
      (value "PINHD-1X4")
      (footprint "eagle-import:1X04")
      (libsource (lib "eagle-import") (part "PINHD-1X4"))
    )
    (comp (ref "L1")
      (value "7.5nH")
      (footprint "eagle-import:0402")
      (libsource (lib "eagle-import") (part "RF-INDUCTOR.0402"))
    )
    (comp (ref "L2")
      (value "18nH")
      (footprint "eagle-import:0402")
      (libsource (lib "eagle-import") (part "RF-INDUCTOR.0402"))
    )
    (comp (ref "L3")
      (value "12nH")
      (footprint "eagle-import:0402")
      (libsource (lib "eagle-import") (part "RF-INDUCTOR.0402"))
    )
    (comp (ref "L4")
      (value "12nH")
      (footprint "eagle-import:0402")
      (libsource (lib "eagle-import") (part "RF-INDUCTOR.0402"))
    )
    (comp (ref "L5")
      (value "15nH")
      (footprint "eagle-import:0402")
      (libsource (lib "eagle-import") (part "RF-INDUCTOR.0402"))
    )
    (comp (ref "L6")
      (value "12nH")
      (footprint "eagle-import:0402")
      (libsource (lib "eagle-import") (part "RF-INDUCTOR.0402"))
    )
    (comp (ref "L7")
      (value "12nH")
      (footprint "eagle-import:0402")
      (libsource (lib "eagle-import") (part "RF-INDUCTOR.0402"))
    )
    (comp (ref "L9")
      (value "10nH")
      (footprint "eagle-import:0402")
      (libsource (lib "eagle-import") (part "RF-INDUCTOR.0402"))
    )
    (comp (ref "R1")
      (value "DNI")
      (footprint "eagle-import:0603")
      (libsource (lib "eagle-import") (part "RESISTOR.0603"))
    )
    (comp (ref "R2")
      (value "DNI")
      (footprint "eagle-import:0603")
      (libsource (lib "eagle-import") (part "RESISTOR.0603"))
    )
    (comp (ref "R5")
      (value "10R")
      (footprint "eagle-import:0603")
      (libsource (lib "eagle-import") (part "RESISTOR.0603"))
    )
    (comp (ref "R6")
      (value "10k")
      (footprint "eagle-import:0603")
      (libsource (lib "eagle-import") (part "RESISTOR.0603"))
    )
    (comp (ref "R7")
      (value "10k")
      (footprint "eagle-import:0603")
      (libsource (lib "eagle-import") (part "RESISTOR.0603"))
    )
    (comp (ref "R8")
      (value "10k")
      (footprint "eagle-import:0603")
      (libsource (lib "eagle-import") (part "RESISTOR.0603"))
    )
    (comp (ref "R11")
      (value "10R")
      (footprint "eagle-import:0402")
      (libsource (lib "eagle-import") (part "RESISTOR.0402"))
    )
    (comp (ref "R33")
      (value "56k_1%")
      (footprint "eagle-import:0603")
      (libsource (lib "eagle-import") (part "RESISTOR.0603"))
    )
    (comp (ref "R34")
      (value "10k")
      (footprint "eagle-import:0603")
      (libsource (lib "eagle-import") (part "RESISTOR.0603"))
    )
    (comp (ref "R35")
      (value "DNI")
      (footprint "eagle-import:0402")
      (libsource (lib "eagle-import") (part "RESISTOR.0402"))
    )
    (comp (ref "R44")
      (value "DNI")
      (footprint "eagle-import:0603")
      (libsource (lib "eagle-import") (part "RESISTOR.0603"))
    )
    (comp (ref "R45")
      (value "DNI")
      (footprint "eagle-import:0603")
      (libsource (lib "eagle-import") (part "RESISTOR.0603"))
    )
    (comp (ref "R46")
      (value "DNI")
      (footprint "eagle-import:0603")
      (libsource (lib "eagle-import") (part "RESISTOR.0603"))
    )
    (comp (ref "R47")
      (value "DNI")
      (footprint "eagle-import:0603")
      (libsource (lib "eagle-import") (part "RESISTOR.0603"))
    )
    (comp (ref "R52")
      (value "4.7k")
      (footprint "eagle-import:0603")
      (libsource (lib "eagle-import") (part "RESISTOR.0603"))
    )
    (comp (ref "R61")
      (value "4.7k")
      (footprint "eagle-import:0603")
      (libsource (lib "eagle-import") (part "RESISTOR.0603"))
    )
    (comp (ref "R93")
      (value "10R")
      (footprint "eagle-import:0603")
      (libsource (lib "eagle-import") (part "RESISTOR.0603"))
    )
    (comp (ref "U1")
      (value "Value")
      (footprint "eagle-import:TEXAS_INSTRUMENTS-RADAR-CC1200RHBR")
      (fields
        (field (name "ALTERNATEPARTNUMBER") "CC1200RHBT")
        (field (name "MANUFACTURER") "Texas Instruments")
        (field (name "PARTNUMBER") "CC1200RHBR")
      )
      (libsource (lib "eagle-import") (part "TEXAS_INSTRUMENTS-RADAR-CC1200RHBR"))
    )
    (comp (ref "U3")
      (value "Value")
      (footprint "eagle-import:PM0064A_N")
      (fields
        (field (name "ALTERNATE_PARTNUMBER") "TM4C1230D5PMI")
        (field (name "MANUFACTURER") "Texas Instruments")
        (field (name "PARTNUMBER") "TM4C1230D5PMIR")
      )
      (libsource (lib "eagle-import") (part "TEXAS_INSTRUMENTS-MICROCONTROLLER-TM4C1230D5PMI7R"))
    )
    (comp (ref "U4")
      (value "Value")
      (footprint "eagle-import:TEXAS_INSTRUMENTS-CAN_TRANSCEIVER-TCAN1042_LED_DRIVER-TLC59731DR")
      (fields (field (name "MANUFACTURER") "Texas Instruments") (field (name "PARTNUMBER") "TCAN1042VDRQ1"))
      (libsource (lib "eagle-import") (part "TEXAS_INSTRUMENTS-CAN_TRANSCEIVER-TCAN1042VDRQ1"))
    )
    (comp (ref "U5")
      (value "TEXAS_INSTRUMENTS-AND_GATE-SN74LVC1G11_DCK_6")
      (footprint "eagle-import:TEXAS_INSTRUMENTS-AND_GATE-SN74LVC1G11_DCK_6")
      (fields
        (field (name "GENERIC_PART_NUMBER") "SN74LVC1G11")
        (field (name "MANUFACTURER") "Texas Instruments")
        (field (name "MANUFACTURER_PART_NUMBER") "sn74lvc1g11_dck_6")
      )
      (libsource (lib "eagle-import") (part "TEXAS_INSTRUMENTS-AND_GATE-SN74LVC1G11_DCK_6"))
    )
    (comp (ref "U15")
      (value "KIOXIA_AMERICA-NAND_FLASH-TC58CVG0S3HRAIG")
      (footprint "eagle-import:KIOXIA_AMERICA-NAND_FLASH-TC58CVG0S3HRAIG")
      (libsource (lib "eagle-import") (part "KIOXIA_AMERICA-NAND_FLASH-TC58CVG0S3HRAIG"))
    )
    (comp (ref "X1")
      (value "ECS_INC-OSCILLATOR-ECS-400-10-37-CKM-TR")
      (footprint "eagle-import:ECS_INC-OSCILLATOR-ECS-400-10-37-CKM-TR")
      (libsource (lib "eagle-import") (part "ECS_INC-OSCILLATOR-ECS-400-10-37-CKM-TR"))
    )
    (comp (ref "X3")
      (value "2510-")
      (footprint "eagle-import:PAK100_2500-10")
      (fields (field (name "MF") "3M") (field (name "MPN") "2510-6002UB"))
      (libsource (lib "eagle-import") (part "2510-"))
    )
    (comp (ref "Y1")
      (value "20MHz")
      (footprint "eagle-import:ESC-OSCILLATOR-ECS_200_9_33B_CTP_TR")
      (libsource (lib "eagle-import") (part "ESC-OSCILLATOR-ECS_200_9_33B_CTP_TR"))
    )
    (comp (ref "C195")
      (value "0.1uF")
      (footprint "eagle-import:0603")
      (libsource (lib "eagle-import") (part "CAPACITOR.0603"))
    )
    (comp (ref "C196")
      (value "10uF")
      (footprint "eagle-import:0805")
      (libsource (lib "eagle-import") (part "CAPACITOR.0805"))
    )
    (comp (ref "C197")
      (value "22uF")
      (footprint "eagle-import:0805")
      (libsource (lib "eagle-import") (part "CAPACITOR.0805"))
    )
    (comp (ref "C198")
      (value "DNI")
      (footprint "eagle-import:0805")
      (libsource (lib "eagle-import") (part "CAPACITOR.0805"))
    )
    (comp (ref "C199")
      (value "10uF")
      (footprint "eagle-import:0805")
      (libsource (lib "eagle-import") (part "CAPACITOR.0805"))
    )
    (comp (ref "C200")
      (value "10uF")
      (footprint "eagle-import:0805")
      (libsource (lib "eagle-import") (part "CAPACITOR.0805"))
    )
    (comp (ref "C201")
      (value "10uF")
      (footprint "eagle-import:0805")
      (libsource (lib "eagle-import") (part "CAPACITOR.0805"))
    )
    (comp (ref "C202")
      (value "10uF")
      (footprint "eagle-import:0805")
      (libsource (lib "eagle-import") (part "CAPACITOR.0805"))
    )
    (comp (ref "C203")
      (value "2.2uF")
      (footprint "eagle-import:0603")
      (libsource (lib "eagle-import") (part "CAPACITOR.0603"))
    )
    (comp (ref "C204")
      (value "0.1uF")
      (footprint "eagle-import:0603")
      (libsource (lib "eagle-import") (part "CAPACITOR.0603"))
    )
    (comp (ref "C205")
      (value "2.2uF")
      (footprint "eagle-import:0603")
      (libsource (lib "eagle-import") (part "CAPACITOR.0603"))
    )
    (comp (ref "C206")
      (value "2.2uF")
      (footprint "eagle-import:0603")
      (libsource (lib "eagle-import") (part "CAPACITOR.0603"))
    )
    (comp (ref "C207")
      (value "100nF")
      (footprint "eagle-import:0805")
      (libsource (lib "eagle-import") (part "CAPACITOR.0805"))
    )
    (comp (ref "C208")
      (value "47uF")
      (footprint "eagle-import:1206")
      (libsource (lib "eagle-import") (part "CAPACITOR.1206"))
    )
    (comp (ref "C209")
      (value "100uF")
      (footprint "eagle-import:1206")
      (libsource (lib "eagle-import") (part "CAPACITOR.1206"))
    )
    (comp (ref "C210")
      (value "10uF")
      (footprint "eagle-import:0805")
      (libsource (lib "eagle-import") (part "CAPACITOR.0805"))
    )
    (comp (ref "C211")
      (value "22uF")
      (footprint "eagle-import:0805")
      (libsource (lib "eagle-import") (part "CAPACITOR.0805"))
    )
    (comp (ref "C212")
      (value "0.1uF")
      (footprint "eagle-import:0805")
      (libsource (lib "eagle-import") (part "CAPACITOR.0805"))
    )
    (comp (ref "C267")
      (value "0.1uF")
      (footprint "eagle-import:0603")
      (libsource (lib "eagle-import") (part "CAPACITOR.0603"))
    )
    (comp (ref "L12")
      (value "4.5uH")
      (footprint "eagle-import:BOURNS-INDUCTOR-SRR1208-4R5ML")
      (libsource (lib "eagle-import") (part "BOURNS-INDUCTOR-SRR1208-4R5ML"))
    )
    (comp (ref "R66")
      (value "0.002R")
      (footprint "eagle-import:1812")
      (libsource (lib "eagle-import") (part "RESISTOR.1812"))
    )
    (comp (ref "R67")
      (value "10k")
      (footprint "eagle-import:0603")
      (libsource (lib "eagle-import") (part "RESISTOR.0603"))
    )
    (comp (ref "R68")
      (value "10k")
      (footprint "eagle-import:0603")
      (libsource (lib "eagle-import") (part "RESISTOR.0603"))
    )
    (comp (ref "R69")
      (value "255k_1%")
      (footprint "eagle-import:0603")
      (libsource (lib "eagle-import") (part "RESISTOR.0603"))
    )
    (comp (ref "R70")
      (value "27k_1%")
      (footprint "eagle-import:0603")
      (libsource (lib "eagle-import") (part "RESISTOR.0603"))
    )
    (comp (ref "R73")
      (value "51.7k_1%")
      (footprint "eagle-import:0603")
      (libsource (lib "eagle-import") (part "RESISTOR.0603"))
    )
    (comp (ref "R74")
      (value "11.5k_1%")
      (footprint "eagle-import:0603")
      (libsource (lib "eagle-import") (part "RESISTOR.0603"))
    )
    (comp (ref "R75")
      (value "24.9k")
      (footprint "eagle-import:0603")
      (libsource (lib "eagle-import") (part "RESISTOR.0603"))
    )
    (comp (ref "R76")
      (value "0.1R")
      (footprint "eagle-import:0603")
      (libsource (lib "eagle-import") (part "RESISTOR.0603"))
    )
    (comp (ref "U18")
      (value "TEXAS_INSTRUMENTS-CURRENT_MONITOR-INA226_DGS_10")
      (footprint "eagle-import:TEXAS_INSTRUMENTS-CURRENT_MONITOR-INA226_DGS_10")
      (fields
        (field (name "GENERIC_PART_NUMBER") "INA226")
        (field (name "MANUFACTURER") "Texas Instruments")
        (field (name "MANUFACTURER_PART_NUMBER") "ina226_dgs_10")
      )
      (libsource (lib "eagle-import") (part "TEXAS_INSTRUMENTS-CURRENT_MONITOR-INA226_DGS_10"))
    )
    (comp (ref "U19")
      (value "TEXAS_INSTRUMENTS-BUCK_CONVERTER-TPS53513RVER")
      (footprint "eagle-import:RVE28_TEX")
      (fields
        (field (name "MANUFACTURER_PART_NUMBER") "TPS53513RVER")
        (field (name "COPYRIGHT") "Copyright (C) 2018 Accelerated Designs. All rights reserved")
      )
      (libsource (lib "eagle-import") (part "TEXAS_INSTRUMENTS-BUCK_CONVERTER-TPS53513RVER"))
    )
    (comp (ref "X6")
      (value "5566-4")
      (footprint "eagle-import:5566-4")
      (fields (field (name "MF") "MOLEX"))
      (libsource (lib "eagle-import") (part "5566-4"))
    )
    (comp (ref "C213")
      (value "10pF")
      (footprint "eagle-import:0603")
      (libsource (lib "eagle-import") (part "CAPACITOR.0603"))
    )
    (comp (ref "C214")
      (value "10pF")
      (footprint "eagle-import:0603")
      (libsource (lib "eagle-import") (part "CAPACITOR.0603"))
    )
    (comp (ref "C215")
      (value "0.1uF")
      (footprint "eagle-import:0603")
      (libsource (lib "eagle-import") (part "CAPACITOR.0603"))
    )
    (comp (ref "C216")
      (value "1.5nF")
      (footprint "eagle-import:0402")
      (libsource (lib "eagle-import") (part "CAPACITOR.0402"))
    )
    (comp (ref "C217")
      (value "220nF")
      (footprint "eagle-import:0402")
      (libsource (lib "eagle-import") (part "CAPACITOR.0402"))
    )
    (comp (ref "C218")
      (value "10nF")
      (footprint "eagle-import:0402")
      (libsource (lib "eagle-import") (part "CAPACITOR.0402"))
    )
    (comp (ref "C219")
      (value "47nF")
      (footprint "eagle-import:0402")
      (libsource (lib "eagle-import") (part "CAPACITOR.0402"))
    )
    (comp (ref "C220")
      (value "47nF")
      (footprint "eagle-import:0402")
      (libsource (lib "eagle-import") (part "CAPACITOR.0402"))
    )
    (comp (ref "C221")
      (value "47nF")
      (footprint "eagle-import:0402")
      (libsource (lib "eagle-import") (part "CAPACITOR.0402"))
    )
    (comp (ref "C222")
      (value "47nF")
      (footprint "eagle-import:0402")
      (libsource (lib "eagle-import") (part "CAPACITOR.0402"))
    )
    (comp (ref "C223")
      (value "47nF")
      (footprint "eagle-import:0402")
      (libsource (lib "eagle-import") (part "CAPACITOR.0402"))
    )
    (comp (ref "C224")
      (value "47nF")
      (footprint "eagle-import:0402")
      (libsource (lib "eagle-import") (part "CAPACITOR.0402"))
    )
    (comp (ref "C225")
      (value "47nF")
      (footprint "eagle-import:0402")
      (libsource (lib "eagle-import") (part "CAPACITOR.0402"))
    )
    (comp (ref "C226")
      (value "47nF")
      (footprint "eagle-import:0402")
      (libsource (lib "eagle-import") (part "CAPACITOR.0402"))
    )
    (comp (ref "C227")
      (value "47nF")
      (footprint "eagle-import:0402")
      (libsource (lib "eagle-import") (part "CAPACITOR.0402"))
    )
    (comp (ref "C228")
      (value "47nF")
      (footprint "eagle-import:0402")
      (libsource (lib "eagle-import") (part "CAPACITOR.0402"))
    )
    (comp (ref "C229")
      (value "47nF")
      (footprint "eagle-import:0402")
      (libsource (lib "eagle-import") (part "CAPACITOR.0402"))
    )
    (comp (ref "C230")
      (value "10uF")
      (footprint "eagle-import:0603")
      (libsource (lib "eagle-import") (part "CAPACITOR.0603"))
    )
    (comp (ref "C231")
      (value "2.2uF")
      (footprint "eagle-import:0603")
      (libsource (lib "eagle-import") (part "CAPACITOR.0603"))
    )
    (comp (ref "C232")
      (value "33pF")
      (footprint "eagle-import:0402")
      (libsource (lib "eagle-import") (part "CAPACITOR.0402"))
    )
    (comp (ref "C233")
      (value "10nF")
      (footprint "eagle-import:0402")
      (libsource (lib "eagle-import") (part "CAPACITOR.0402"))
    )
    (comp (ref "C234")
      (value "100pF")
      (footprint "eagle-import:0402")
      (libsource (lib "eagle-import") (part "CAPACITOR.0402"))
    )
    (comp (ref "C235")
      (value "0.01uF")
      (footprint "eagle-import:0603")
      (libsource (lib "eagle-import") (part "CAPACITOR.0603"))
    )
    (comp (ref "C236")
      (value "0.1uF")
      (footprint "eagle-import:0603")
      (libsource (lib "eagle-import") (part "CAPACITOR.0603"))
    )
    (comp (ref "C237")
      (value "0.01uF")
      (footprint "eagle-import:0603")
      (libsource (lib "eagle-import") (part "CAPACITOR.0603"))
    )
    (comp (ref "C238")
      (value "0.1uF")
      (footprint "eagle-import:0603")
      (libsource (lib "eagle-import") (part "CAPACITOR.0603"))
    )
    (comp (ref "C239")
      (value "0.1uF")
      (footprint "eagle-import:0603")
      (libsource (lib "eagle-import") (part "CAPACITOR.0603"))
    )
    (comp (ref "C240")
      (value "DNI")
      (footprint "eagle-import:0603")
      (libsource (lib "eagle-import") (part "CAPACITOR.0603"))
    )
    (comp (ref "C241")
      (value "DNI")
      (footprint "eagle-import:0603")
      (libsource (lib "eagle-import") (part "CAPACITOR.0603"))
    )
    (comp (ref "C242")
      (value "2.2uF")
      (footprint "eagle-import:0603")
      (libsource (lib "eagle-import") (part "CAPACITOR.0603"))
    )
    (comp (ref "C243")
      (value "1uF")
      (footprint "eagle-import:0603")
      (libsource (lib "eagle-import") (part "CAPACITOR.0603"))
    )
    (comp (ref "C244")
      (value "0.1uF")
      (footprint "eagle-import:0603")
      (libsource (lib "eagle-import") (part "CAPACITOR.0603"))
    )
    (comp (ref "C245")
      (value "0.1uF")
      (footprint "eagle-import:0603")
      (libsource (lib "eagle-import") (part "CAPACITOR.0603"))
    )
    (comp (ref "C246")
      (value "1uF")
      (footprint "eagle-import:0603")
      (libsource (lib "eagle-import") (part "CAPACITOR.0603"))
    )
    (comp (ref "C247")
      (value "1uF")
      (footprint "eagle-import:0603")
      (libsource (lib "eagle-import") (part "CAPACITOR.0603"))
    )
    (comp (ref "C248")
      (value "10uF")
      (footprint "eagle-import:0603")
      (libsource (lib "eagle-import") (part "CAPACITOR.0603"))
    )
    (comp (ref "C249")
      (value "4.7uF")
      (footprint "eagle-import:0603")
      (libsource (lib "eagle-import") (part "CAPACITOR.0603"))
    )
    (comp (ref "C250")
      (value "1uF")
      (footprint "eagle-import:0603")
      (libsource (lib "eagle-import") (part "CAPACITOR.0603"))
    )
    (comp (ref "C251")
      (value "1uF")
      (footprint "eagle-import:0603")
      (libsource (lib "eagle-import") (part "CAPACITOR.0603"))
    )
    (comp (ref "C252")
      (value "0.1uF")
      (footprint "eagle-import:0603")
      (libsource (lib "eagle-import") (part "CAPACITOR.0603"))
    )
    (comp (ref "C253")
      (value "0.1uF")
      (footprint "eagle-import:0603")
      (libsource (lib "eagle-import") (part "CAPACITOR.0603"))
    )
    (comp (ref "C254")
      (value "0.1uF")
      (footprint "eagle-import:0603")
      (libsource (lib "eagle-import") (part "CAPACITOR.0603"))
    )
    (comp (ref "C255")
      (value "0.1uF")
      (footprint "eagle-import:0603")
      (libsource (lib "eagle-import") (part "CAPACITOR.0603"))
    )
    (comp (ref "C256")
      (value "1uF")
      (footprint "eagle-import:0603")
      (libsource (lib "eagle-import") (part "CAPACITOR.0603"))
    )
    (comp (ref "C257")
      (value "15pF")
      (footprint "eagle-import:0402")
      (libsource (lib "eagle-import") (part "CAPACITOR.0402"))
    )
    (comp (ref "C258")
      (value "1pF")
      (footprint "eagle-import:0402")
      (libsource (lib "eagle-import") (part "CAPACITOR.0402"))
    )
    (comp (ref "C259")
      (value "2.2pF")
      (footprint "eagle-import:0402")
      (libsource (lib "eagle-import") (part "CAPACITOR.0402"))
    )
    (comp (ref "C260")
      (value "3.3pF")
      (footprint "eagle-import:0402")
      (libsource (lib "eagle-import") (part "CAPACITOR.0402"))
    )
    (comp (ref "C261")
      (value "3.3pF")
      (footprint "eagle-import:0402")
      (libsource (lib "eagle-import") (part "CAPACITOR.0402"))
    )
    (comp (ref "C262")
      (value "3pF")
      (footprint "eagle-import:0402")
      (libsource (lib "eagle-import") (part "CAPACITOR.0402"))
    )
    (comp (ref "C263")
      (value "DNI")
      (footprint "eagle-import:0402")
      (libsource (lib "eagle-import") (part "CAPACITOR.0402"))
    )
    (comp (ref "C264")
      (value "0.1uF")
      (footprint "eagle-import:0603")
      (libsource (lib "eagle-import") (part "CAPACITOR.0603"))
    )
    (comp (ref "C265")
      (value "1uF")
      (footprint "eagle-import:0603")
      (libsource (lib "eagle-import") (part "CAPACITOR.0603"))
    )
    (comp (ref "C266")
      (value "10nF")
      (footprint "eagle-import:0603")
      (libsource (lib "eagle-import") (part "CAPACITOR.0603"))
    )
    (comp (ref "JP10")
      (value "PINHD-1X4")
      (footprint "eagle-import:1X04")
      (libsource (lib "eagle-import") (part "PINHD-1X4"))
    )
    (comp (ref "JP11")
      (value "PINHD-1X4")
      (footprint "eagle-import:1X04")
      (libsource (lib "eagle-import") (part "PINHD-1X4"))
    )
    (comp (ref "L13")
      (value "10nH")
      (footprint "eagle-import:0402")
      (libsource (lib "eagle-import") (part "RF-INDUCTOR.0402"))
    )
    (comp (ref "L14")
      (value "7.5nH")
      (footprint "eagle-import:0402")
      (libsource (lib "eagle-import") (part "RF-INDUCTOR.0402"))
    )
    (comp (ref "L15")
      (value "18nH")
      (footprint "eagle-import:0402")
      (libsource (lib "eagle-import") (part "RF-INDUCTOR.0402"))
    )
    (comp (ref "L16")
      (value "12nH")
      (footprint "eagle-import:0402")
      (libsource (lib "eagle-import") (part "RF-INDUCTOR.0402"))
    )
    (comp (ref "L17")
      (value "12nH")
      (footprint "eagle-import:0402")
      (libsource (lib "eagle-import") (part "RF-INDUCTOR.0402"))
    )
    (comp (ref "L18")
      (value "15nH")
      (footprint "eagle-import:0402")
      (libsource (lib "eagle-import") (part "RF-INDUCTOR.0402"))
    )
    (comp (ref "L19")
      (value "12nH")
      (footprint "eagle-import:0402")
      (libsource (lib "eagle-import") (part "RF-INDUCTOR.0402"))
    )
    (comp (ref "L20")
      (value "12nH")
      (footprint "eagle-import:0402")
      (libsource (lib "eagle-import") (part "RF-INDUCTOR.0402"))
    )
    (comp (ref "R77")
      (value "56k_1%")
      (footprint "eagle-import:0603")
      (libsource (lib "eagle-import") (part "RESISTOR.0603"))
    )
    (comp (ref "R78")
      (value "10k")
      (footprint "eagle-import:0603")
      (libsource (lib "eagle-import") (part "RESISTOR.0603"))
    )
    (comp (ref "R79")
      (value "DNI")
      (footprint "eagle-import:0402")
      (libsource (lib "eagle-import") (part "RESISTOR.0402"))
    )
    (comp (ref "R80")
      (value "10R")
      (footprint "eagle-import:0402")
      (libsource (lib "eagle-import") (part "RESISTOR.0402"))
    )
    (comp (ref "R81")
      (value "10R")
      (footprint "eagle-import:0603")
      (libsource (lib "eagle-import") (part "RESISTOR.0603"))
    )
    (comp (ref "R82")
      (value "10k")
      (footprint "eagle-import:0603")
      (libsource (lib "eagle-import") (part "RESISTOR.0603"))
    )
    (comp (ref "R83")
      (value "10k")
      (footprint "eagle-import:0603")
      (libsource (lib "eagle-import") (part "RESISTOR.0603"))
    )
    (comp (ref "R84")
      (value "10k")
      (footprint "eagle-import:0603")
      (libsource (lib "eagle-import") (part "RESISTOR.0603"))
    )
    (comp (ref "R85")
      (value "DNI")
      (footprint "eagle-import:0603")
      (libsource (lib "eagle-import") (part "RESISTOR.0603"))
    )
    (comp (ref "R86")
      (value "DNI")
      (footprint "eagle-import:0603")
      (libsource (lib "eagle-import") (part "RESISTOR.0603"))
    )
    (comp (ref "R87")
      (value "DNI")
      (footprint "eagle-import:0603")
      (libsource (lib "eagle-import") (part "RESISTOR.0603"))
    )
    (comp (ref "R88")
      (value "DNI")
      (footprint "eagle-import:0603")
      (libsource (lib "eagle-import") (part "RESISTOR.0603"))
    )
    (comp (ref "R89")
      (value "DNI")
      (footprint "eagle-import:0603")
      (libsource (lib "eagle-import") (part "RESISTOR.0603"))
    )
    (comp (ref "R90")
      (value "DNI")
      (footprint "eagle-import:0603")
      (libsource (lib "eagle-import") (part "RESISTOR.0603"))
    )
    (comp (ref "R91")
      (value "4.7k")
      (footprint "eagle-import:0603")
      (libsource (lib "eagle-import") (part "RESISTOR.0603"))
    )
    (comp (ref "R92")
      (value "4.7k")
      (footprint "eagle-import:0603")
      (libsource (lib "eagle-import") (part "RESISTOR.0603"))
    )
    (comp (ref "R94")
      (value "10R")
      (footprint "eagle-import:0603")
      (libsource (lib "eagle-import") (part "RESISTOR.0603"))
    )
    (comp (ref "U20")
      (value "Value")
      (footprint "eagle-import:TEXAS_INSTRUMENTS-RADAR-CC1200RHBR")
      (fields
        (field (name "ALTERNATEPARTNUMBER") "CC1200RHBT")
        (field (name "MANUFACTURER") "Texas Instruments")
        (field (name "PARTNUMBER") "CC1200RHBR")
      )
      (libsource (lib "eagle-import") (part "TEXAS_INSTRUMENTS-RADAR-CC1200RHBR"))
    )
    (comp (ref "U21")
      (value "Value")
      (footprint "eagle-import:PM0064A_N")
      (fields
        (field (name "ALTERNATE_PARTNUMBER") "TM4C1230D5PMI")
        (field (name "MANUFACTURER") "Texas Instruments")
        (field (name "PARTNUMBER") "TM4C1230D5PMIR")
      )
      (libsource (lib "eagle-import") (part "TEXAS_INSTRUMENTS-MICROCONTROLLER-TM4C1230D5PMI7R"))
    )
    (comp (ref "U22")
      (value "Value")
      (footprint "eagle-import:TEXAS_INSTRUMENTS-CAN_TRANSCEIVER-TCAN1042_LED_DRIVER-TLC59731DR")
      (fields (field (name "MANUFACTURER") "Texas Instruments") (field (name "PARTNUMBER") "TCAN1042VDRQ1"))
      (libsource (lib "eagle-import") (part "TEXAS_INSTRUMENTS-CAN_TRANSCEIVER-TCAN1042VDRQ1"))
    )
    (comp (ref "U23")
      (value "TEXAS_INSTRUMENTS-AND_GATE-SN74LVC1G11_DCK_6")
      (footprint "eagle-import:TEXAS_INSTRUMENTS-AND_GATE-SN74LVC1G11_DCK_6")
      (fields
        (field (name "GENERIC_PART_NUMBER") "SN74LVC1G11")
        (field (name "MANUFACTURER") "Texas Instruments")
        (field (name "MANUFACTURER_PART_NUMBER") "sn74lvc1g11_dck_6")
      )
      (libsource (lib "eagle-import") (part "TEXAS_INSTRUMENTS-AND_GATE-SN74LVC1G11_DCK_6"))
    )
    (comp (ref "U24")
      (value "KIOXIA_AMERICA-NAND_FLASH-TC58CVG0S3HRAIG")
      (footprint "eagle-import:KIOXIA_AMERICA-NAND_FLASH-TC58CVG0S3HRAIG")
      (libsource (lib "eagle-import") (part "KIOXIA_AMERICA-NAND_FLASH-TC58CVG0S3HRAIG"))
    )
    (comp (ref "X7")
      (value "ECS_INC-OSCILLATOR-ECS-400-10-37-CKM-TR")
      (footprint "eagle-import:ECS_INC-OSCILLATOR-ECS-400-10-37-CKM-TR")
      (libsource (lib "eagle-import") (part "ECS_INC-OSCILLATOR-ECS-400-10-37-CKM-TR"))
    )
    (comp (ref "X8")
      (value "2510-")
      (footprint "eagle-import:PAK100_2500-10")
      (fields (field (name "MF") "3M") (field (name "MPN") "2510-6002UB"))
      (libsource (lib "eagle-import") (part "2510-"))
    )
    (comp (ref "Y3")
      (value "20MHz")
      (footprint "eagle-import:ESC-OSCILLATOR-ECS_200_9_33B_CTP_TR")
      (libsource (lib "eagle-import") (part "ESC-OSCILLATOR-ECS_200_9_33B_CTP_TR"))
    )
    (comp (ref "C137")
      (value "0.1uF")
      (footprint "eagle-import:0603")
      (libsource (lib "eagle-import") (part "CAPACITOR.0603"))
    )
    (comp (ref "C138")
      (value "0.1uF")
      (footprint "eagle-import:0603")
      (libsource (lib "eagle-import") (part "CAPACITOR.0603"))
    )
    (comp (ref "C139")
      (value "0.1uF")
      (footprint "eagle-import:0603")
      (libsource (lib "eagle-import") (part "CAPACITOR.0603"))
    )
    (comp (ref "C140")
      (value "0.1uF")
      (footprint "eagle-import:0603")
      (libsource (lib "eagle-import") (part "CAPACITOR.0603"))
    )
    (comp (ref "C141")
      (value "0.1uF")
      (footprint "eagle-import:0603")
      (libsource (lib "eagle-import") (part "CAPACITOR.0603"))
    )
    (comp (ref "C142")
      (value "0.1uF")
      (footprint "eagle-import:0603")
      (libsource (lib "eagle-import") (part "CAPACITOR.0603"))
    )
    (comp (ref "R53")
      (value "DNI")
      (footprint "eagle-import:0603")
      (libsource (lib "eagle-import") (part "RESISTOR.0603"))
    )
    (comp (ref "R54")
      (value "DNI")
      (footprint "eagle-import:0603")
      (libsource (lib "eagle-import") (part "RESISTOR.0603"))
    )
    (comp (ref "R55")
      (value "DNI")
      (footprint "eagle-import:0603")
      (libsource (lib "eagle-import") (part "RESISTOR.0603"))
    )
    (comp (ref "R56")
      (value "DNI")
      (footprint "eagle-import:0603")
      (libsource (lib "eagle-import") (part "RESISTOR.0603"))
    )
    (comp (ref "R57")
      (value "DNI")
      (footprint "eagle-import:0603")
      (libsource (lib "eagle-import") (part "RESISTOR.0603"))
    )
    (comp (ref "R58")
      (value "DNI")
      (footprint "eagle-import:0603")
      (libsource (lib "eagle-import") (part "RESISTOR.0603"))
    )
    (comp (ref "R59")
      (value "DNI")
      (footprint "eagle-import:0603")
      (libsource (lib "eagle-import") (part "RESISTOR.0603"))
    )
    (comp (ref "R60")
      (value "DNI")
      (footprint "eagle-import:0603")
      (libsource (lib "eagle-import") (part "RESISTOR.0603"))
    )
    (comp (ref "U7")
      (value "TMP100")
      (footprint "eagle-import:SOT23-6")
      (libsource (lib "eagle-import") (part "TMP100"))
    )
    (comp (ref "U8")
      (value "BMX160")
      (footprint "eagle-import:PQFN50P250X300X100-14N")
      (fields (field (name "MF") "Bosch Sensortec"))
      (libsource (lib "eagle-import") (part "BMX160"))
    )
    (comp (ref "U9")
      (value "BMX160")
      (footprint "eagle-import:PQFN50P250X300X100-14N")
      (fields (field (name "MF") "Bosch Sensortec"))
      (libsource (lib "eagle-import") (part "BMX160"))
    )
    (comp (ref "U34")
      (value "TMP100")
      (footprint "eagle-import:SOT23-6")
      (libsource (lib "eagle-import") (part "TMP100"))
    )
    (comp (ref "C157")
      (value "2.2uF")
      (footprint "eagle-import:0603")
      (libsource (lib "eagle-import") (part "CAPACITOR.0603"))
    )
    (comp (ref "C158")
      (value "10uF")
      (footprint "eagle-import:0805")
      (libsource (lib "eagle-import") (part "CAPACITOR.0805"))
    )
    (comp (ref "C159")
      (value "0.1uF")
      (footprint "eagle-import:0603")
      (libsource (lib "eagle-import") (part "CAPACITOR.0603"))
    )
    (comp (ref "C160")
      (value "2.2uF")
      (footprint "eagle-import:0603")
      (libsource (lib "eagle-import") (part "CAPACITOR.0603"))
    )
    (comp (ref "C161")
      (value "10uF")
      (footprint "eagle-import:0805")
      (libsource (lib "eagle-import") (part "CAPACITOR.0805"))
    )
    (comp (ref "C162")
      (value "0.1uF")
      (footprint "eagle-import:0603")
      (libsource (lib "eagle-import") (part "CAPACITOR.0603"))
    )
    (comp (ref "C163")
      (value "0.1uF")
      (footprint "eagle-import:0603")
      (libsource (lib "eagle-import") (part "CAPACITOR.0603"))
    )
    (comp (ref "C164")
      (value "10uF")
      (footprint "eagle-import:0805")
      (libsource (lib "eagle-import") (part "CAPACITOR.0805"))
    )
    (comp (ref "C165")
      (value "0.1uF")
      (footprint "eagle-import:0603")
      (libsource (lib "eagle-import") (part "CAPACITOR.0603"))
    )
    (comp (ref "C166")
      (value "0.1uF")
      (footprint "eagle-import:0603")
      (libsource (lib "eagle-import") (part "CAPACITOR.0603"))
    )
    (comp (ref "C268")
      (value "0.1uF")
      (footprint "eagle-import:0603")
      (libsource (lib "eagle-import") (part "CAPACITOR.0603"))
    )
    (comp (ref "C269")
      (value "0.1uF")
      (footprint "eagle-import:0603")
      (libsource (lib "eagle-import") (part "CAPACITOR.0603"))
    )
    (comp (ref "JP5")
      (value "PINHD-1X2")
      (footprint "eagle-import:1X02")
      (libsource (lib "eagle-import") (part "PINHD-1X2"))
    )
    (comp (ref "JP6")
      (value "PINHD-1X2")
      (footprint "eagle-import:1X02")
      (libsource (lib "eagle-import") (part "PINHD-1X2"))
    )
    (comp (ref "JP7")
      (value "PINHD-1X2")
      (footprint "eagle-import:1X02")
      (libsource (lib "eagle-import") (part "PINHD-1X2"))
    )
    (comp (ref "JP8")
      (value "PINHD-1X2")
      (footprint "eagle-import:1X02")
      (libsource (lib "eagle-import") (part "PINHD-1X2"))
    )
    (comp (ref "R13")
      (value "10k")
      (footprint "eagle-import:0603")
      (libsource (lib "eagle-import") (part "RESISTOR.0603"))
    )
    (comp (ref "R14")
      (value "10k")
      (footprint "eagle-import:0603")
      (libsource (lib "eagle-import") (part "RESISTOR.0603"))
    )
    (comp (ref "R15")
      (value "DNI")
      (footprint "eagle-import:0603")
      (libsource (lib "eagle-import") (part "RESISTOR.0603"))
    )
    (comp (ref "R16")
      (value "DNI")
      (footprint "eagle-import:0603")
      (libsource (lib "eagle-import") (part "RESISTOR.0603"))
    )
    (comp (ref "R17")
      (value "DNI")
      (footprint "eagle-import:0603")
      (libsource (lib "eagle-import") (part "RESISTOR.0603"))
    )
    (comp (ref "R18")
      (value "DNI")
      (footprint "eagle-import:0603")
      (libsource (lib "eagle-import") (part "RESISTOR.0603"))
    )
    (comp (ref "R19")
      (value "1R_1%")
      (footprint "eagle-import:0603")
      (libsource (lib "eagle-import") (part "RESISTOR.0603"))
    )
    (comp (ref "R20")
      (value "1R_1%")
      (footprint "eagle-import:0603")
      (libsource (lib "eagle-import") (part "RESISTOR.0603"))
    )
    (comp (ref "R21")
      (value "10k")
      (footprint "eagle-import:0603")
      (libsource (lib "eagle-import") (part "RESISTOR.0603"))
    )
    (comp (ref "R22")
      (value "10k")
      (footprint "eagle-import:0603")
      (libsource (lib "eagle-import") (part "RESISTOR.0603"))
    )
    (comp (ref "R23")
      (value "DNI")
      (footprint "eagle-import:0603")
      (libsource (lib "eagle-import") (part "RESISTOR.0603"))
    )
    (comp (ref "R24")
      (value "DNI")
      (footprint "eagle-import:0603")
      (libsource (lib "eagle-import") (part "RESISTOR.0603"))
    )
    (comp (ref "R25")
      (value "DNI")
      (footprint "eagle-import:0603")
      (libsource (lib "eagle-import") (part "RESISTOR.0603"))
    )
    (comp (ref "R26")
      (value "DNI")
      (footprint "eagle-import:0603")
      (libsource (lib "eagle-import") (part "RESISTOR.0603"))
    )
    (comp (ref "R27")
      (value "1R_1%")
      (footprint "eagle-import:0603")
      (libsource (lib "eagle-import") (part "RESISTOR.0603"))
    )
    (comp (ref "R28")
      (value "1R_1%")
      (footprint "eagle-import:0603")
      (libsource (lib "eagle-import") (part "RESISTOR.0603"))
    )
    (comp (ref "R29")
      (value "0.015R")
      (footprint "eagle-import:1206")
      (libsource (lib "eagle-import") (part "RESISTOR.1206"))
    )
    (comp (ref "R30")
      (value "10k")
      (footprint "eagle-import:0603")
      (libsource (lib "eagle-import") (part "RESISTOR.0603"))
    )
    (comp (ref "R31")
      (value "0.015R")
      (footprint "eagle-import:1206")
      (libsource (lib "eagle-import") (part "RESISTOR.1206"))
    )
    (comp (ref "R32")
      (value "10k")
      (footprint "eagle-import:0603")
      (libsource (lib "eagle-import") (part "RESISTOR.0603"))
    )
    (comp (ref "U10")
      (value "Value")
      (footprint "eagle-import:PWP0016K_N")
      (fields (field (name "MANUFACTURER") "Texas Instruments") (field (name "PARTNUMBER") "DRV8833CPWPR"))
      (libsource (lib "eagle-import") (part "TEXAS_INSTRUMENTS-MOTOR_PWM_DRIVER-DRV8833CPWP"))
    )
    (comp (ref "U11")
      (value "Value")
      (footprint "eagle-import:PWP0016K_N")
      (fields (field (name "MANUFACTURER") "Texas Instruments") (field (name "PARTNUMBER") "DRV8833CPWPR"))
      (libsource (lib "eagle-import") (part "TEXAS_INSTRUMENTS-MOTOR_PWM_DRIVER-DRV8833CPWP"))
    )
    (comp (ref "U12")
      (value "TEXAS_INSTRUMENTS-CURRENT_MONITOR-INA226_DGS_10")
      (footprint "eagle-import:TEXAS_INSTRUMENTS-CURRENT_MONITOR-INA226_DGS_10")
      (fields
        (field (name "GENERIC_PART_NUMBER") "INA226")
        (field (name "MANUFACTURER") "Texas Instruments")
        (field (name "MANUFACTURER_PART_NUMBER") "ina226_dgs_10")
      )
      (libsource (lib "eagle-import") (part "TEXAS_INSTRUMENTS-CURRENT_MONITOR-INA226_DGS_10"))
    )
    (comp (ref "U13")
      (value "TEXAS_INSTRUMENTS-CURRENT_MONITOR-INA226_DGS_10")
      (footprint "eagle-import:TEXAS_INSTRUMENTS-CURRENT_MONITOR-INA226_DGS_10")
      (fields
        (field (name "GENERIC_PART_NUMBER") "INA226")
        (field (name "MANUFACTURER") "Texas Instruments")
        (field (name "MANUFACTURER_PART_NUMBER") "ina226_dgs_10")
      )
      (libsource (lib "eagle-import") (part "TEXAS_INSTRUMENTS-CURRENT_MONITOR-INA226_DGS_10"))
    )
    (comp (ref "C27")
      (value "0.1uF")
      (footprint "eagle-import:0402")
      (libsource (lib "eagle-import") (part "CAPACITOR.0402"))
    )
    (comp (ref "C28")
      (value "0.1uF")
      (footprint "eagle-import:0402")
      (libsource (lib "eagle-import") (part "CAPACITOR.0402"))
    )
    (comp (ref "C29")
      (value "1uF")
      (footprint "eagle-import:0402")
      (libsource (lib "eagle-import") (part "CAPACITOR.0402"))
    )
    (comp (ref "C33")
      (value "0.1uF")
      (footprint "eagle-import:0402")
      (libsource (lib "eagle-import") (part "CAPACITOR.0402"))
    )
    (comp (ref "C34")
      (value "0.1uF")
      (footprint "eagle-import:0402")
      (libsource (lib "eagle-import") (part "CAPACITOR.0402"))
    )
    (comp (ref "C35")
      (value "0.1uF")
      (footprint "eagle-import:0402")
      (libsource (lib "eagle-import") (part "CAPACITOR.0402"))
    )
    (comp (ref "C36")
      (value "0.1uF")
      (footprint "eagle-import:0402")
      (libsource (lib "eagle-import") (part "CAPACITOR.0402"))
    )
    (comp (ref "C37")
      (value "0.1uF")
      (footprint "eagle-import:0402")
      (libsource (lib "eagle-import") (part "CAPACITOR.0402"))
    )
    (comp (ref "C38")
      (value "0.1uF")
      (footprint "eagle-import:0402")
      (libsource (lib "eagle-import") (part "CAPACITOR.0402"))
    )
    (comp (ref "C39")
      (value "0.1uF")
      (footprint "eagle-import:0402")
      (libsource (lib "eagle-import") (part "CAPACITOR.0402"))
    )
    (comp (ref "C40")
      (value "0.1uF")
      (footprint "eagle-import:0402")
      (libsource (lib "eagle-import") (part "CAPACITOR.0402"))
    )
    (comp (ref "C41")
      (value "0.1uF")
      (footprint "eagle-import:0402")
      (libsource (lib "eagle-import") (part "CAPACITOR.0402"))
    )
    (comp (ref "C42")
      (value "0.1uF")
      (footprint "eagle-import:0402")
      (libsource (lib "eagle-import") (part "CAPACITOR.0402"))
    )
    (comp (ref "C43")
      (value "0.1uF")
      (footprint "eagle-import:0402")
      (libsource (lib "eagle-import") (part "CAPACITOR.0402"))
    )
    (comp (ref "C44")
      (value "0.1uF")
      (footprint "eagle-import:0402")
      (libsource (lib "eagle-import") (part "CAPACITOR.0402"))
    )
    (comp (ref "C45")
      (value "0.1uF")
      (footprint "eagle-import:0402")
      (libsource (lib "eagle-import") (part "CAPACITOR.0402"))
    )
    (comp (ref "C46")
      (value "0.1uF")
      (footprint "eagle-import:0402")
      (libsource (lib "eagle-import") (part "CAPACITOR.0402"))
    )
    (comp (ref "C47")
      (value "0.1uF")
      (footprint "eagle-import:0402")
      (libsource (lib "eagle-import") (part "CAPACITOR.0402"))
    )
    (comp (ref "C48")
      (value "0.1uF")
      (footprint "eagle-import:0402")
      (libsource (lib "eagle-import") (part "CAPACITOR.0402"))
    )
    (comp (ref "C68")
      (value "0.1uF")
      (footprint "eagle-import:0402")
      (libsource (lib "eagle-import") (part "CAPACITOR.0402"))
    )
    (comp (ref "C69")
      (value "0.1uF")
      (footprint "eagle-import:0402")
      (libsource (lib "eagle-import") (part "CAPACITOR.0402"))
    )
    (comp (ref "C70")
      (value "0.1uF")
      (footprint "eagle-import:0402")
      (libsource (lib "eagle-import") (part "CAPACITOR.0402"))
    )
    (comp (ref "C71")
      (value "0.1uF")
      (footprint "eagle-import:0402")
      (libsource (lib "eagle-import") (part "CAPACITOR.0402"))
    )
    (comp (ref "C72")
      (value "0.1uF")
      (footprint "eagle-import:0402")
      (libsource (lib "eagle-import") (part "CAPACITOR.0402"))
    )
    (comp (ref "C73")
      (value "0.1uF")
      (footprint "eagle-import:0402")
      (libsource (lib "eagle-import") (part "CAPACITOR.0402"))
    )
    (comp (ref "C74")
      (value "0.1uF")
      (footprint "eagle-import:0402")
      (libsource (lib "eagle-import") (part "CAPACITOR.0402"))
    )
    (comp (ref "C75")
      (value "0.1uF")
      (footprint "eagle-import:0402")
      (libsource (lib "eagle-import") (part "CAPACITOR.0402"))
    )
    (comp (ref "C76")
      (value "0.1uF")
      (footprint "eagle-import:0402")
      (libsource (lib "eagle-import") (part "CAPACITOR.0402"))
    )
    (comp (ref "C80")
      (value "0.1uF")
      (footprint "eagle-import:0402")
      (libsource (lib "eagle-import") (part "CAPACITOR.0402"))
    )
    (comp (ref "C81")
      (value "0.1uF")
      (footprint "eagle-import:0402")
      (libsource (lib "eagle-import") (part "CAPACITOR.0402"))
    )
    (comp (ref "C82")
      (value "0.1uF")
      (footprint "eagle-import:0402")
      (libsource (lib "eagle-import") (part "CAPACITOR.0402"))
    )
    (comp (ref "C83")
      (value "0.1uF")
      (footprint "eagle-import:0402")
      (libsource (lib "eagle-import") (part "CAPACITOR.0402"))
    )
    (comp (ref "C84")
      (value "0.1uF")
      (footprint "eagle-import:0402")
      (libsource (lib "eagle-import") (part "CAPACITOR.0402"))
    )
    (comp (ref "C85")
      (value "1uF")
      (footprint "eagle-import:0402")
      (libsource (lib "eagle-import") (part "CAPACITOR.0402"))
    )
    (comp (ref "C86")
      (value "1uF")
      (footprint "eagle-import:0402")
      (libsource (lib "eagle-import") (part "CAPACITOR.0402"))
    )
    (comp (ref "C87")
      (value "1uF")
      (footprint "eagle-import:0402")
      (libsource (lib "eagle-import") (part "CAPACITOR.0402"))
    )
    (comp (ref "C88")
      (value "2.2uF")
      (footprint "eagle-import:0402")
      (libsource (lib "eagle-import") (part "CAPACITOR.0402"))
    )
    (comp (ref "C89")
      (value "4.7uF")
      (footprint "eagle-import:0603")
      (libsource (lib "eagle-import") (part "CAPACITOR.0603"))
    )
    (comp (ref "C90")
      (value "10uF")
      (footprint "eagle-import:0603")
      (libsource (lib "eagle-import") (part "CAPACITOR.0603"))
    )
    (comp (ref "C91")
      (value "2.2uF")
      (footprint "eagle-import:0402")
      (libsource (lib "eagle-import") (part "CAPACITOR.0402"))
    )
    (comp (ref "C92")
      (value "2.2uF")
      (footprint "eagle-import:0402")
      (libsource (lib "eagle-import") (part "CAPACITOR.0402"))
    )
    (comp (ref "C93")
      (value "0.1uF")
      (footprint "eagle-import:0402")
      (libsource (lib "eagle-import") (part "CAPACITOR.0402"))
    )
    (comp (ref "C94")
      (value "0.1uF")
      (footprint "eagle-import:0402")
      (libsource (lib "eagle-import") (part "CAPACITOR.0402"))
    )
    (comp (ref "C95")
      (value "0.1uF")
      (footprint "eagle-import:0402")
      (libsource (lib "eagle-import") (part "CAPACITOR.0402"))
    )
    (comp (ref "C96")
      (value "0.1uF")
      (footprint "eagle-import:0402")
      (libsource (lib "eagle-import") (part "CAPACITOR.0402"))
    )
    (comp (ref "C97")
      (value "2.2uF")
      (footprint "eagle-import:0402")
      (libsource (lib "eagle-import") (part "CAPACITOR.0402"))
    )
    (comp (ref "C98")
      (value "0.1uF")
      (footprint "eagle-import:0402")
      (libsource (lib "eagle-import") (part "CAPACITOR.0402"))
    )
    (comp (ref "C99")
      (value "0.1uF")
      (footprint "eagle-import:0402")
      (libsource (lib "eagle-import") (part "CAPACITOR.0402"))
    )
    (comp (ref "C100")
      (value "0.1uF")
      (footprint "eagle-import:0402")
      (libsource (lib "eagle-import") (part "CAPACITOR.0402"))
    )
    (comp (ref "C101")
      (value "0.1uF")
      (footprint "eagle-import:0402")
      (libsource (lib "eagle-import") (part "CAPACITOR.0402"))
    )
    (comp (ref "C102")
      (value "0.1uF")
      (footprint "eagle-import:0402")
      (libsource (lib "eagle-import") (part "CAPACITOR.0402"))
    )
    (comp (ref "C103")
      (value "0.1uF")
      (footprint "eagle-import:0402")
      (libsource (lib "eagle-import") (part "CAPACITOR.0402"))
    )
    (comp (ref "C104")
      (value "0.1uF")
      (footprint "eagle-import:0402")
      (libsource (lib "eagle-import") (part "CAPACITOR.0402"))
    )
    (comp (ref "C105")
      (value "0.1uF")
      (footprint "eagle-import:0402")
      (libsource (lib "eagle-import") (part "CAPACITOR.0402"))
    )
    (comp (ref "C106")
      (value "0.1uF")
      (footprint "eagle-import:0402")
      (libsource (lib "eagle-import") (part "CAPACITOR.0402"))
    )
    (comp (ref "C107")
      (value "0.1uF")
      (footprint "eagle-import:0402")
      (libsource (lib "eagle-import") (part "CAPACITOR.0402"))
    )
    (comp (ref "C108")
      (value "0.1uF")
      (footprint "eagle-import:0402")
      (libsource (lib "eagle-import") (part "CAPACITOR.0402"))
    )
    (comp (ref "C109")
      (value "0.1uF")
      (footprint "eagle-import:0402")
      (libsource (lib "eagle-import") (part "CAPACITOR.0402"))
    )
    (comp (ref "C110")
      (value "0.1uF")
      (footprint "eagle-import:0402")
      (libsource (lib "eagle-import") (part "CAPACITOR.0402"))
    )
    (comp (ref "C111")
      (value "0.1uF")
      (footprint "eagle-import:0402")
      (libsource (lib "eagle-import") (part "CAPACITOR.0402"))
    )
    (comp (ref "C112")
      (value "1uF")
      (footprint "eagle-import:0402")
      (libsource (lib "eagle-import") (part "CAPACITOR.0402"))
    )
    (comp (ref "C113")
      (value "1uF")
      (footprint "eagle-import:0402")
      (libsource (lib "eagle-import") (part "CAPACITOR.0402"))
    )
    (comp (ref "C114")
      (value "1uF")
      (footprint "eagle-import:0402")
      (libsource (lib "eagle-import") (part "CAPACITOR.0402"))
    )
    (comp (ref "C115")
      (value "4.7uF")
      (footprint "eagle-import:0603")
      (libsource (lib "eagle-import") (part "CAPACITOR.0603"))
    )
    (comp (ref "C116")
      (value "4.7uF")
      (footprint "eagle-import:0603")
      (libsource (lib "eagle-import") (part "CAPACITOR.0603"))
    )
    (comp (ref "C117")
      (value "10uF")
      (footprint "eagle-import:0603")
      (libsource (lib "eagle-import") (part "CAPACITOR.0603"))
    )
    (comp (ref "C118")
      (value "10nF")
      (footprint "eagle-import:0603")
      (libsource (lib "eagle-import") (part "CAPACITOR.0603"))
    )
    (comp (ref "C119")
      (value "10nF")
      (footprint "eagle-import:0603")
      (libsource (lib "eagle-import") (part "CAPACITOR.0603"))
    )
    (comp (ref "C120")
      (value "22uF")
      (footprint "eagle-import:0603")
      (libsource (lib "eagle-import") (part "CAPACITOR.0603"))
    )
    (comp (ref "C121")
      (value "22uF")
      (footprint "eagle-import:0603")
      (libsource (lib "eagle-import") (part "CAPACITOR.0603"))
    )
    (comp (ref "C122")
      (value "22uF")
      (footprint "eagle-import:0603")
      (libsource (lib "eagle-import") (part "CAPACITOR.0603"))
    )
    (comp (ref "C123")
      (value "22uF")
      (footprint "eagle-import:0603")
      (libsource (lib "eagle-import") (part "CAPACITOR.0603"))
    )
    (comp (ref "C143")
      (value "0.1uF")
      (footprint "eagle-import:0603")
      (libsource (lib "eagle-import") (part "CAPACITOR.0603"))
    )
    (comp (ref "C144")
      (value "0.1uF")
      (footprint "eagle-import:0603")
      (libsource (lib "eagle-import") (part "CAPACITOR.0603"))
    )
    (comp (ref "C145")
      (value "0.1uF")
      (footprint "eagle-import:0603")
      (libsource (lib "eagle-import") (part "CAPACITOR.0603"))
    )
    (comp (ref "C146")
      (value "0.1uF")
      (footprint "eagle-import:0603")
      (libsource (lib "eagle-import") (part "CAPACITOR.0603"))
    )
    (comp (ref "C147")
      (value "0.1uF")
      (footprint "eagle-import:0603")
      (libsource (lib "eagle-import") (part "CAPACITOR.0603"))
    )
    (comp (ref "C148")
      (value "0.1uF")
      (footprint "eagle-import:0603")
      (libsource (lib "eagle-import") (part "CAPACITOR.0603"))
    )
    (comp (ref "C149")
      (value "0.1uF")
      (footprint "eagle-import:0603")
      (libsource (lib "eagle-import") (part "CAPACITOR.0603"))
    )
    (comp (ref "C150")
      (value "0.1uF")
      (footprint "eagle-import:0603")
      (libsource (lib "eagle-import") (part "CAPACITOR.0603"))
    )
    (comp (ref "C151")
      (value "0.1uF")
      (footprint "eagle-import:0603")
      (libsource (lib "eagle-import") (part "CAPACITOR.0603"))
    )
    (comp (ref "C152")
      (value "0.1uF")
      (footprint "eagle-import:0603")
      (libsource (lib "eagle-import") (part "CAPACITOR.0603"))
    )
    (comp (ref "C153")
      (value "0.1uF")
      (footprint "eagle-import:0603")
      (libsource (lib "eagle-import") (part "CAPACITOR.0603"))
    )
    (comp (ref "C154")
      (value "0.1uF")
      (footprint "eagle-import:0603")
      (libsource (lib "eagle-import") (part "CAPACITOR.0603"))
    )
    (comp (ref "C155")
      (value "0.1uF")
      (footprint "eagle-import:0603")
      (libsource (lib "eagle-import") (part "CAPACITOR.0603"))
    )
    (comp (ref "C156")
      (value "0.1uF")
      (footprint "eagle-import:0603")
      (libsource (lib "eagle-import") (part "CAPACITOR.0603"))
    )
    (comp (ref "C171")
      (value "1uF")
      (footprint "eagle-import:0603")
      (libsource (lib "eagle-import") (part "CAPACITOR.0603"))
    )
    (comp (ref "C172")
      (value "0.1uF")
      (footprint "eagle-import:0603")
      (libsource (lib "eagle-import") (part "CAPACITOR.0603"))
    )
    (comp (ref "C173")
      (value "1uF")
      (footprint "eagle-import:0603")
      (libsource (lib "eagle-import") (part "CAPACITOR.0603"))
    )
    (comp (ref "C174")
      (value "0.1uF")
      (footprint "eagle-import:0603")
      (libsource (lib "eagle-import") (part "CAPACITOR.0603"))
    )
    (comp (ref "JP1")
      (value "PINHD-1X8")
      (footprint "eagle-import:1X08")
      (libsource (lib "eagle-import") (part "PINHD-1X8"))
    )
    (comp (ref "JP4")
      (value "PINHD-1X8")
      (footprint "eagle-import:1X08")
      (libsource (lib "eagle-import") (part "PINHD-1X8"))
    )
    (comp (ref "JP9")
      (value "PINHD-1X4")
      (footprint "eagle-import:1X04")
      (libsource (lib "eagle-import") (part "PINHD-1X4"))
    )
    (comp (ref "R3")
      (value "56R_10%")
      (footprint "eagle-import:0402")
      (libsource (lib "eagle-import") (part "RESISTOR.0402"))
    )
    (comp (ref "R4")
      (value "4.7k")
      (footprint "eagle-import:0603")
      (libsource (lib "eagle-import") (part "RESISTOR.0603"))
    )
    (comp (ref "R9")
      (value "10k")
      (footprint "eagle-import:0603")
      (libsource (lib "eagle-import") (part "RESISTOR.0603"))
    )
    (comp (ref "R10")
      (value "2.2k")
      (footprint "eagle-import:0603")
      (libsource (lib "eagle-import") (part "RESISTOR.0603"))
    )
    (comp (ref "R12")
      (value "2.2k")
      (footprint "eagle-import:0603")
      (libsource (lib "eagle-import") (part "RESISTOR.0603"))
    )
    (comp (ref "R36")
      (value "4.7k")
      (footprint "eagle-import:0603")
      (libsource (lib "eagle-import") (part "RESISTOR.0603"))
    )
    (comp (ref "R37")
      (value "DNI")
      (footprint "eagle-import:0603")
      (libsource (lib "eagle-import") (part "RESISTOR.0603"))
    )
    (comp (ref "R38")
      (value "4.7k")
      (footprint "eagle-import:0603")
      (libsource (lib "eagle-import") (part "RESISTOR.0603"))
    )
    (comp (ref "R39")
      (value "DNI")
      (footprint "eagle-import:0603")
      (libsource (lib "eagle-import") (part "RESISTOR.0603"))
    )
    (comp (ref "R40")
      (value "10k")
      (footprint "eagle-import:0603")
      (libsource (lib "eagle-import") (part "RESISTOR.0603"))
    )
    (comp (ref "R41")
      (value "120R")
      (footprint "eagle-import:0603")
      (libsource (lib "eagle-import") (part "RESISTOR.0603"))
    )
    (comp (ref "R62")
      (value "10k")
      (footprint "eagle-import:0603")
      (libsource (lib "eagle-import") (part "RESISTOR.0603"))
    )
    (comp (ref "R63")
      (value "10k")
      (footprint "eagle-import:0603")
      (libsource (lib "eagle-import") (part "RESISTOR.0603"))
    )
    (comp (ref "R72")
      (value "100k")
      (footprint "eagle-import:0603")
      (libsource (lib "eagle-import") (part "RESISTOR.0603"))
    )
    (comp (ref "U2")
      (value "Value")
      (footprint "eagle-import:ZWT0337A-IPC_A")
      (fields (field (name "MANUFACTURER") "Texas Instruments") (field (name "PARTNUMBER") "F28386DZWTSR"))
      (libsource (lib "eagle-import") (part "TEXAS_INSTRUMENTS-MICROCONTROLLER-TMS320F28386DZWTQ"))
    )
    (comp (ref "U14")
      (value "Value")
      (footprint "eagle-import:TEXAS_INSTRUMENTS-CAN_TRANSCEIVER-TCAN1042_LED_DRIVER-TLC59731DR")
      (fields (field (name "MANUFACTURER") "Texas Instruments") (field (name "PARTNUMBER") "TCAN1042VDRQ1"))
      (libsource (lib "eagle-import") (part "TEXAS_INSTRUMENTS-CAN_TRANSCEIVER-TCAN1042VDRQ1"))
    )
    (comp (ref "X4")
      (value "2510-")
      (footprint "eagle-import:PAK100_2500-10")
      (fields (field (name "MF") "3M") (field (name "MPN") "2510-6002UB"))
      (libsource (lib "eagle-import") (part "2510-"))
    )
    (comp (ref "Y2")
      (value "20MHz")
      (footprint "eagle-import:ESC-OSCILLATOR-ECS_200_9_33B_CTP_TR")
      (libsource (lib "eagle-import") (part "ESC-OSCILLATOR-ECS_200_9_33B_CTP_TR"))
    )
    (comp (ref "C167")
      (value "2.2uF")
      (footprint "eagle-import:0603")
      (libsource (lib "eagle-import") (part "CAPACITOR.0603"))
    )
    (comp (ref "C168")
      (value "0.1uF")
      (footprint "eagle-import:0603")
      (libsource (lib "eagle-import") (part "CAPACITOR.0603"))
    )
    (comp (ref "C169")
      (value "2.2uF")
      (footprint "eagle-import:0603")
      (libsource (lib "eagle-import") (part "CAPACITOR.0603"))
    )
    (comp (ref "C170")
      (value "0.1uF")
      (footprint "eagle-import:0603")
      (libsource (lib "eagle-import") (part "CAPACITOR.0603"))
    )
    (comp (ref "J1")
      (value "SEAF-10-XX.X-XX-04-X-A")
      (footprint "eagle-import:SEAF-10-XX.X-XX-04-X-A")
      (fields (field (name "MF") "Samtec"))
      (libsource (lib "eagle-import") (part "SEAF-10-XX.X-XX-04-X-A"))
    )
    (comp (ref "C124")
      (value "0.1uF")
      (footprint "eagle-import:0603")
      (libsource (lib "eagle-import") (part "CAPACITOR.0603"))
    )
    (comp (ref "C125")
      (value "0.1uF")
      (footprint "eagle-import:0603")
      (libsource (lib "eagle-import") (part "CAPACITOR.0603"))
    )
    (comp (ref "C126")
      (value "0.1uF")
      (footprint "eagle-import:0603")
      (libsource (lib "eagle-import") (part "CAPACITOR.0603"))
    )
    (comp (ref "C127")
      (value "0.1uF")
      (footprint "eagle-import:0603")
      (libsource (lib "eagle-import") (part "CAPACITOR.0603"))
    )
    (comp (ref "C128")
      (value "0.1uF")
      (footprint "eagle-import:0603")
      (libsource (lib "eagle-import") (part "CAPACITOR.0603"))
    )
    (comp (ref "C129")
      (value "0.1uF")
      (footprint "eagle-import:0603")
      (libsource (lib "eagle-import") (part "CAPACITOR.0603"))
    )
    (comp (ref "C130")
      (value "0.1uF")
      (footprint "eagle-import:0603")
      (libsource (lib "eagle-import") (part "CAPACITOR.0603"))
    )
    (comp (ref "C131")
      (value "1uF")
      (footprint "eagle-import:0603")
      (libsource (lib "eagle-import") (part "CAPACITOR.0603"))
    )
    (comp (ref "C132")
      (value "1uF")
      (footprint "eagle-import:0603")
      (libsource (lib "eagle-import") (part "CAPACITOR.0603"))
    )
    (comp (ref "C133")
      (value "1uF")
      (footprint "eagle-import:0603")
      (libsource (lib "eagle-import") (part "CAPACITOR.0603"))
    )
    (comp (ref "C134")
      (value "2.2uF")
      (footprint "eagle-import:0603")
      (libsource (lib "eagle-import") (part "CAPACITOR.0603"))
    )
    (comp (ref "C135")
      (value "10uF")
      (footprint "eagle-import:0603")
      (libsource (lib "eagle-import") (part "CAPACITOR.0603"))
    )
    (comp (ref "C136")
      (value "10uF")
      (footprint "eagle-import:0603")
      (libsource (lib "eagle-import") (part "CAPACITOR.0603"))
    )
    (comp (ref "C187")
      (value "0.1uF")
      (footprint "eagle-import:0603")
      (libsource (lib "eagle-import") (part "CAPACITOR.0603"))
    )
    (comp (ref "C188")
      (value "1uF")
      (footprint "eagle-import:0603")
      (libsource (lib "eagle-import") (part "CAPACITOR.0603"))
    )
    (comp (ref "R48")
      (value "DNI")
      (footprint "eagle-import:0603")
      (libsource (lib "eagle-import") (part "RESISTOR.0603"))
    )
    (comp (ref "R49")
      (value "DNI")
      (footprint "eagle-import:0603")
      (libsource (lib "eagle-import") (part "RESISTOR.0603"))
    )
    (comp (ref "R50")
      (value "DNI")
      (footprint "eagle-import:0603")
      (libsource (lib "eagle-import") (part "RESISTOR.0603"))
    )
    (comp (ref "R51")
      (value "DNI")
      (footprint "eagle-import:0603")
      (libsource (lib "eagle-import") (part "RESISTOR.0603"))
    )
    (comp (ref "U6")
      (value "ISSI-DRAM-IS42S16320F-7TL")
      (footprint "eagle-import:ISSI-DRAM-IS42S16320F-7TL")
      (libsource (lib "eagle-import") (part "ISSI-DRAM-IS42S16320F-7TL"))
    )
    (comp (ref "U16")
      (value "KIOXIA_AMERICA-NAND_FLASH-TC58CVG0S3HRAIG")
      (footprint "eagle-import:KIOXIA_AMERICA-NAND_FLASH-TC58CVG0S3HRAIG")
      (libsource (lib "eagle-import") (part "KIOXIA_AMERICA-NAND_FLASH-TC58CVG0S3HRAIG"))
    )
  )
  (nets
    (net (code "1") (name "ADCS_ERROR") (class "Default")
      (node (ref "IC1") (pin "8") (pinfunction "I/O_6_8") (pintype "bidirectional"))
      (node (ref "J1") (pin "C10") (pinfunction "10_C10") (pintype "bidirectional"))
    )
    (net (code "2") (name "ADCS_FAILURE") (class "Default")
      (node (ref "J1") (pin "A10") (pinfunction "10_A10") (pintype "bidirectional"))
    )
    (net (code "3") (name "ADCS_ONLINE") (class "Default")
      (node (ref "IC1") (pin "7") (pinfunction "I/O_5_7") (pintype "bidirectional"))
      (node (ref "J1") (pin "C9") (pinfunction "9_C9") (pintype "bidirectional"))
    )
    (net (code "4") (name "ADC_A0") (class "Default")
      (node (ref "C149") (pin "1") (pinfunction "1_1") (pintype "bidirectional"))
      (node (ref "JP1") (pin "2") (pinfunction "2_2") (pintype "passive"))
      (node (ref "U2") (pin "U1") (pinfunction "ADCINA0_DACOUTA_U1") (pintype "passive"))
    )
    (net (code "5") (name "ADC_A1") (class "Default")
      (node (ref "C148") (pin "1") (pinfunction "1_1") (pintype "bidirectional"))
      (node (ref "JP1") (pin "3") (pinfunction "3_3") (pintype "passive"))
      (node (ref "U2") (pin "T1") (pinfunction "ADCINA1_DACOUTB_T1") (pintype "passive"))
    )
    (net (code "6") (name "ADC_A2") (class "Default")
      (node (ref "C147") (pin "1") (pinfunction "1_1") (pintype "bidirectional"))
      (node (ref "JP1") (pin "4") (pinfunction "4_4") (pintype "passive"))
      (node (ref "U2") (pin "U2") (pinfunction "ADCINA2_CMPIN1P_U2") (pintype "passive"))
    )
    (net (code "7") (name "ADC_A3") (class "Default")
      (node (ref "C146") (pin "1") (pinfunction "1_1") (pintype "bidirectional"))
      (node (ref "JP1") (pin "5") (pinfunction "5_5") (pintype "passive"))
      (node (ref "U2") (pin "T2") (pinfunction "ADCINA3_CMPIN1N_T2") (pintype "passive"))
    )
    (net (code "8") (name "ADC_A4") (class "Default")
      (node (ref "C145") (pin "1") (pinfunction "1_1") (pintype "bidirectional"))
      (node (ref "JP1") (pin "6") (pinfunction "6_6") (pintype "passive"))
      (node (ref "U2") (pin "U3") (pinfunction "ADCINA4_CMPIN2P_U3") (pintype "passive"))
    )
    (net (code "9") (name "ADC_A5") (class "Default")
      (node (ref "C144") (pin "1") (pinfunction "1_1") (pintype "bidirectional"))
      (node (ref "JP1") (pin "7") (pinfunction "7_7") (pintype "passive"))
      (node (ref "U2") (pin "T3") (pinfunction "ADCINA5_CMPIN2N_T3") (pintype "passive"))
    )
    (net (code "10") (name "ADC_B0") (class "Default")
      (node (ref "C156") (pin "1") (pinfunction "1_1") (pintype "bidirectional"))
      (node (ref "JP4") (pin "2") (pinfunction "2_2") (pintype "passive"))
      (node (ref "U2") (pin "V2") (pinfunction "ADCINB0_VDAC_V2") (pintype "passive"))
    )
    (net (code "11") (name "ADC_B1") (class "Default")
      (node (ref "C155") (pin "1") (pinfunction "1_1") (pintype "bidirectional"))
      (node (ref "JP4") (pin "3") (pinfunction "3_3") (pintype "passive"))
      (node (ref "U2") (pin "W2") (pinfunction "ADCINB1_DACOUTC_W2") (pintype "passive"))
    )
    (net (code "12") (name "ADC_B2") (class "Default")
      (node (ref "C154") (pin "1") (pinfunction "1_1") (pintype "bidirectional"))
      (node (ref "JP4") (pin "4") (pinfunction "4_4") (pintype "passive"))
      (node (ref "U2") (pin "V3") (pinfunction "ADCINB2_CMPIN3P_V3") (pintype "passive"))
    )
    (net (code "13") (name "ADC_B3") (class "Default")
      (node (ref "C153") (pin "1") (pinfunction "1_1") (pintype "bidirectional"))
      (node (ref "JP4") (pin "5") (pinfunction "5_5") (pintype "passive"))
      (node (ref "U2") (pin "W3") (pinfunction "ADCINB3_CMPIN3N_W3") (pintype "passive"))
    )
    (net (code "14") (name "ADC_B4") (class "Default")
      (node (ref "C152") (pin "1") (pinfunction "1_1") (pintype "bidirectional"))
      (node (ref "JP4") (pin "6") (pinfunction "6_6") (pintype "passive"))
      (node (ref "U2") (pin "V4") (pinfunction "ADCINB4_V4") (pintype "passive"))
    )
    (net (code "15") (name "ADC_B5") (class "Default")
      (node (ref "C151") (pin "1") (pinfunction "1_1") (pintype "bidirectional"))
      (node (ref "JP4") (pin "7") (pinfunction "7_7") (pintype "passive"))
      (node (ref "U2") (pin "W4") (pinfunction "ADCINB5_W4") (pintype "passive"))
    )
    (net (code "16") (name "ANT1_PREMUX_50Z") (class "Default")
      (node (ref "C26") (pin "2") (pinfunction "2_2") (pintype "bidirectional"))
      (node (ref "L10") (pin "1") (pinfunction "1_1") (pintype "passive"))
      (node (ref "L7") (pin "2") (pinfunction "2_2") (pintype "passive"))
    )
    (net (code "17") (name "ANT2_PREMUX_50Z") (class "Default")
      (node (ref "C263") (pin "2") (pinfunction "2_2") (pintype "bidirectional"))
      (node (ref "L11") (pin "1") (pinfunction "1_1") (pintype "passive"))
      (node (ref "L20") (pin "2") (pinfunction "2_2") (pintype "passive"))
    )
    (net (code "18") (name "ANTENNA") (class "Default")
      (node (ref "L8") (pin "2") (pinfunction "2_2") (pintype "passive"))
      (node (ref "X2") (pin "1") (pinfunction "1_1") (pintype "passive"))
    )
    (net (code "19") (name "BMX160_1_INT1") (class "Default")
      (node (ref "R54") (pin "2") (pinfunction "2_2") (pintype "bidirectional"))
      (node (ref "R55") (pin "1") (pinfunction "1_1") (pintype "bidirectional"))
      (node (ref "U2") (pin "C1") (pinfunction "GPIO11_C1") (pintype "bidirectional"))
      (node (ref "U8") (pin "4") (pinfunction "INT1_4") (pintype "bidirectional"))
    )
    (net (code "20") (name "BMX160_1_INT2") (class "Default")
      (node (ref "R53") (pin "2") (pinfunction "2_2") (pintype "bidirectional"))
      (node (ref "R56") (pin "1") (pinfunction "1_1") (pintype "bidirectional"))
      (node (ref "U2") (pin "C2") (pinfunction "GPIO12_C2") (pintype "bidirectional"))
      (node (ref "U8") (pin "9") (pinfunction "INT2_9") (pintype "bidirectional"))
    )
    (net (code "21") (name "BMX160_2_INT1") (class "Default")
      (node (ref "R58") (pin "2") (pinfunction "2_2") (pintype "bidirectional"))
      (node (ref "R59") (pin "1") (pinfunction "1_1") (pintype "bidirectional"))
      (node (ref "U2") (pin "D1") (pinfunction "GPIO13_D1") (pintype "bidirectional"))
      (node (ref "U9") (pin "4") (pinfunction "INT1_4") (pintype "bidirectional"))
    )
    (net (code "22") (name "BMX160_2_INT2") (class "Default")
      (node (ref "R57") (pin "2") (pinfunction "2_2") (pintype "bidirectional"))
      (node (ref "R60") (pin "1") (pinfunction "1_1") (pintype "bidirectional"))
      (node (ref "U2") (pin "D2") (pinfunction "GPIO14_D2") (pintype "bidirectional"))
      (node (ref "U9") (pin "9") (pinfunction "INT2_9") (pintype "bidirectional"))
    )
    (net (code "23") (name "CANH") (class "Default")
      (node (ref "J1") (pin "A7") (pinfunction "7_A7") (pintype "bidirectional"))
      (node (ref "R1") (pin "1") (pinfunction "1_1") (pintype "bidirectional"))
      (node (ref "R41") (pin "1") (pinfunction "1_1") (pintype "bidirectional"))
      (node (ref "R85") (pin "1") (pinfunction "1_1") (pintype "bidirectional"))
      (node (ref "U14") (pin "7") (pinfunction "CANH_7") (pintype "bidirectional"))
      (node (ref "U22") (pin "7") (pinfunction "CANH_7") (pintype "bidirectional"))
      (node (ref "U4") (pin "7") (pinfunction "CANH_7") (pintype "bidirectional"))
    )
    (net (code "24") (name "CANL") (class "Default")
      (node (ref "J1") (pin "A8") (pinfunction "8_A8") (pintype "bidirectional"))
      (node (ref "R1") (pin "2") (pinfunction "2_2") (pintype "bidirectional"))
      (node (ref "R41") (pin "2") (pinfunction "2_2") (pintype "bidirectional"))
      (node (ref "R85") (pin "2") (pinfunction "2_2") (pintype "bidirectional"))
      (node (ref "U14") (pin "6") (pinfunction "CANL_6") (pintype "bidirectional"))
      (node (ref "U22") (pin "6") (pinfunction "CANL_6") (pintype "bidirectional"))
      (node (ref "U4") (pin "6") (pinfunction "CANL_6") (pintype "bidirectional"))
    )
    (net (code "25") (name "CC1200_1_SPI_CLK") (class "Default")
      (node (ref "U1") (pin "8") (pinfunction "SCLK_8") (pintype "input"))
      (node (ref "U3") (pin "19") (pinfunction "PA2_SSI0CLK_19") (pintype "bidirectional"))
    )
    (net (code "26") (name "CC1200_1_SPI_MISO") (class "Default")
      (node (ref "U1") (pin "9") (pinfunction "SO_GPIO1_9") (pintype "bidirectional"))
      (node (ref "U3") (pin "21") (pinfunction "PA4_SSI0RX_21") (pintype "bidirectional"))
    )
    (net (code "27") (name "CC1200_1_SPI_MOSI") (class "Default")
      (node (ref "U1") (pin "7") (pinfunction "SI_7") (pintype "input"))
      (node (ref "U3") (pin "22") (pinfunction "PA5_SSI0TX_22") (pintype "bidirectional"))
    )
    (net (code "28") (name "CC1200_2_SPI_CLK") (class "Default")
      (node (ref "U20") (pin "8") (pinfunction "SCLK_8") (pintype "input"))
      (node (ref "U21") (pin "19") (pinfunction "PA2_SSI0CLK_19") (pintype "bidirectional"))
    )
    (net (code "29") (name "CC1200_2_SPI_MISO") (class "Default")
      (node (ref "U20") (pin "9") (pinfunction "SO_GPIO1_9") (pintype "bidirectional"))
      (node (ref "U21") (pin "21") (pinfunction "PA4_SSI0RX_21") (pintype "bidirectional"))
    )
    (net (code "30") (name "CC1200_2_SPI_MOSI") (class "Default")
      (node (ref "U20") (pin "7") (pinfunction "SI_7") (pintype "input"))
      (node (ref "U21") (pin "22") (pinfunction "PA5_SSI0TX_22") (pintype "bidirectional"))
    )
    (net (code "31") (name "COMMS1_CAN_RX") (class "Default")
      (node (ref "U3") (pin "58") (pinfunction "PB4_58") (pintype "bidirectional"))
      (node (ref "U4") (pin "4") (pinfunction "RXD_4") (pintype "output"))
    )
    (net (code "32") (name "COMMS1_CAN_STB") (class "Default")
      (node (ref "U3") (pin "1") (pinfunction "PB6_1") (pintype "bidirectional"))
      (node (ref "U4") (pin "8") (pinfunction "STB_8") (pintype "input"))
    )
    (net (code "33") (name "COMMS1_CAN_TX") (class "Default")
      (node (ref "U3") (pin "57") (pinfunction "PB5_57") (pintype "bidirectional"))
      (node (ref "U4") (pin "1") (pinfunction "TXD_1") (pintype "input"))
    )
    (net (code "34") (name "COMMS1_I2C0_SCL") (class "Default")
      (node (ref "JP2") (pin "3") (pinfunction "3_3") (pintype "passive"))
      (node (ref "U3") (pin "47") (pinfunction "PB2_I2C0SCL_47") (pintype "bidirectional"))
    )
    (net (code "35") (name "COMMS1_I2C0_SDA") (class "Default")
      (node (ref "JP2") (pin "2") (pinfunction "2_2") (pintype "passive"))
      (node (ref "U3") (pin "48") (pinfunction "PB3_I2C0SDA_48") (pintype "bidirectional"))
    )
    (net (code "36") (name "COMMS1_NAND_MISO") (class "Default")
      (node (ref "U15") (pin "2") (pinfunction "SO/SO1_2") (pintype "bidirectional"))
      (node (ref "U3") (pin "28") (pinfunction "PF0_28") (pintype "bidirectional"))
    )
    (net (code "37") (name "COMMS1_NAND_MOSI") (class "Default")
      (node (ref "U15") (pin "5") (pinfunction "SI/SO0_5") (pintype "bidirectional"))
      (node (ref "U3") (pin "29") (pinfunction "PF1_29") (pintype "bidirectional"))
    )
    (net (code "38") (name "COMMS1_NAND_SCK") (class "Default")
      (node (ref "U15") (pin "6") (pinfunction "SCK_6") (pintype "bidirectional"))
      (node (ref "U3") (pin "30") (pinfunction "PF2_30") (pintype "bidirectional"))
    )
    (net (code "39") (name "COMMS1_NMI") (class "Default")
      (node (ref "C189") (pin "1") (pinfunction "1_1") (pintype "bidirectional"))
      (node (ref "IC1") (pin "12") (pinfunction "I/O_7_12") (pintype "bidirectional"))
      (node (ref "R52") (pin "1") (pinfunction "1_1") (pintype "bidirectional"))
      (node (ref "U3") (pin "10") (pinfunction "PD7_10") (pintype "bidirectional"))
    )
    (net (code "40") (name "COMMS1_UART_RX") (class "Default")
      (node (ref "J1") (pin "C5") (pinfunction "5_C5") (pintype "bidirectional"))
      (node (ref "JP3") (pin "2") (pinfunction "2_2") (pintype "passive"))
      (node (ref "U3") (pin "17") (pinfunction "PA0_U0RX_17") (pintype "bidirectional"))
    )
    (net (code "41") (name "COMMS1_UART_TX") (class "Default")
      (node (ref "J1") (pin "C4") (pinfunction "4_C4") (pintype "bidirectional"))
      (node (ref "JP3") (pin "3") (pinfunction "3_3") (pintype "passive"))
      (node (ref "U3") (pin "18") (pinfunction "PA1_U0TX_18") (pintype "bidirectional"))
    )
    (net (code "42") (name "COMMS2_CAN_RX") (class "Default")
      (node (ref "U21") (pin "58") (pinfunction "PB4_58") (pintype "bidirectional"))
      (node (ref "U22") (pin "4") (pinfunction "RXD_4") (pintype "output"))
    )
    (net (code "43") (name "COMMS2_CAN_STB") (class "Default")
      (node (ref "U21") (pin "1") (pinfunction "PB6_1") (pintype "bidirectional"))
      (node (ref "U22") (pin "8") (pinfunction "STB_8") (pintype "input"))
    )
    (net (code "44") (name "COMMS2_CAN_TX") (class "Default")
      (node (ref "U21") (pin "57") (pinfunction "PB5_57") (pintype "bidirectional"))
      (node (ref "U22") (pin "1") (pinfunction "TXD_1") (pintype "input"))
    )
    (net (code "45") (name "COMMS2_I2C0_SCL") (class "Default")
      (node (ref "JP10") (pin "3") (pinfunction "3_3") (pintype "passive"))
      (node (ref "U21") (pin "47") (pinfunction "PB2_I2C0SCL_47") (pintype "bidirectional"))
    )
    (net (code "46") (name "COMMS2_I2C0_SDA") (class "Default")
      (node (ref "JP10") (pin "2") (pinfunction "2_2") (pintype "passive"))
      (node (ref "U21") (pin "48") (pinfunction "PB3_I2C0SDA_48") (pintype "bidirectional"))
    )
    (net (code "47") (name "COMMS2_NAND_MISO") (class "Default")
      (node (ref "U21") (pin "28") (pinfunction "PF0_28") (pintype "bidirectional"))
      (node (ref "U24") (pin "2") (pinfunction "SO/SO1_2") (pintype "bidirectional"))
    )
    (net (code "48") (name "COMMS2_NAND_MOSI") (class "Default")
      (node (ref "U21") (pin "29") (pinfunction "PF1_29") (pintype "bidirectional"))
      (node (ref "U24") (pin "5") (pinfunction "SI/SO0_5") (pintype "bidirectional"))
    )
    (net (code "49") (name "COMMS2_NAND_SCK") (class "Default")
      (node (ref "U21") (pin "30") (pinfunction "PF2_30") (pintype "bidirectional"))
      (node (ref "U24") (pin "6") (pinfunction "SCK_6") (pintype "bidirectional"))
    )
    (net (code "50") (name "COMMS2_NMI") (class "Default")
      (node (ref "C266") (pin "1") (pinfunction "1_1") (pintype "bidirectional"))
      (node (ref "IC1") (pin "13") (pinfunction "I/O_8_13") (pintype "bidirectional"))
      (node (ref "R91") (pin "1") (pinfunction "1_1") (pintype "bidirectional"))
      (node (ref "U21") (pin "10") (pinfunction "PD7_10") (pintype "bidirectional"))
    )
    (net (code "51") (name "COMMS2_UART_RX") (class "Default")
      (node (ref "J1") (pin "C8") (pinfunction "8_C8") (pintype "bidirectional"))
      (node (ref "JP11") (pin "2") (pinfunction "2_2") (pintype "passive"))
      (node (ref "U21") (pin "17") (pinfunction "PA0_U0RX_17") (pintype "bidirectional"))
    )
    (net (code "52") (name "COMMS2_UART_TX") (class "Default")
      (node (ref "J1") (pin "C7") (pinfunction "7_C7") (pintype "bidirectional"))
      (node (ref "JP11") (pin "3") (pinfunction "3_3") (pintype "passive"))
      (node (ref "U21") (pin "18") (pinfunction "PA1_U0TX_18") (pintype "bidirectional"))
    )
    (net (code "53") (name "CPLD_I1") (class "Default")
      (node (ref "IC1") (pin "36") (pinfunction "I/O/GTS1_36") (pintype "bidirectional"))
      (node (ref "J1") (pin "D3") (pinfunction "3_D3") (pintype "bidirectional"))
    )
    (net (code "54") (name "CPLD_I2") (class "Default")
      (node (ref "IC1") (pin "37") (pinfunction "I/O_23_37") (pintype "bidirectional"))
      (node (ref "J1") (pin "D4") (pinfunction "4_D4") (pintype "bidirectional"))
    )
    (net (code "55") (name "CPLD_I3") (class "Default")
      (node (ref "IC1") (pin "38") (pinfunction "I/O_24_38") (pintype "bidirectional"))
      (node (ref "J1") (pin "D5") (pinfunction "5_D5") (pintype "bidirectional"))
    )
    (net (code "56") (name "CPLD_I4") (class "Default")
      (node (ref "IC1") (pin "39") (pinfunction "I/O_25_39") (pintype "bidirectional"))
      (node (ref "J1") (pin "D6") (pinfunction "6_D6") (pintype "bidirectional"))
    )
    (net (code "57") (name "CPLD_O1") (class "Default")
      (node (ref "IC1") (pin "40") (pinfunction "I/O_26_40") (pintype "bidirectional"))
      (node (ref "J1") (pin "D7") (pinfunction "7_D7") (pintype "bidirectional"))
    )
    (net (code "58") (name "CPLD_O2") (class "Default")
      (node (ref "IC1") (pin "41") (pinfunction "I/O_27_41") (pintype "bidirectional"))
      (node (ref "J1") (pin "D8") (pinfunction "8_D8") (pintype "bidirectional"))
    )
    (net (code "59") (name "CPLD_O3") (class "Default")
      (node (ref "IC1") (pin "42") (pinfunction "I/O_28_42") (pintype "bidirectional"))
      (node (ref "J1") (pin "D9") (pinfunction "9_D9") (pintype "bidirectional"))
    )
    (net (code "60") (name "CPLD_O4") (class "Default")
      (node (ref "IC1") (pin "43") (pinfunction "I/O/GCK1_43") (pintype "bidirectional"))
      (node (ref "J1") (pin "D10") (pinfunction "10_D10") (pintype "bidirectional"))
    )
    (net (code "61") (name "EPWM1A") (class "Default")
      (node (ref "R18") (pin "1") (pinfunction "1_1") (pintype "bidirectional"))
      (node (ref "U10") (pin "16") (pinfunction "AIN1_16") (pintype "input"))
      (node (ref "U2") (pin "C8") (pinfunction "GPIO0_C8") (pintype "bidirectional"))
    )
    (net (code "62") (name "EPWM1B") (class "Default")
      (node (ref "R17") (pin "1") (pinfunction "1_1") (pintype "bidirectional"))
      (node (ref "U10") (pin "15") (pinfunction "AIN2_15") (pintype "input"))
      (node (ref "U2") (pin "D8") (pinfunction "GPIO1_D8") (pintype "bidirectional"))
    )
    (net (code "63") (name "EPWM2A") (class "Default")
      (node (ref "R16") (pin "1") (pinfunction "1_1") (pintype "bidirectional"))
      (node (ref "U10") (pin "9") (pinfunction "BIN1_9") (pintype "input"))
      (node (ref "U2") (pin "A7") (pinfunction "GPIO2_A7") (pintype "bidirectional"))
    )
    (net (code "64") (name "EPWM2B") (class "Default")
      (node (ref "R15") (pin "1") (pinfunction "1_1") (pintype "bidirectional"))
      (node (ref "U10") (pin "10") (pinfunction "BIN2_10") (pintype "input"))
      (node (ref "U2") (pin "B7") (pinfunction "GPIO3_B7") (pintype "bidirectional"))
    )
    (net (code "65") (name "EPWM3A") (class "Default")
      (node (ref "R26") (pin "1") (pinfunction "1_1") (pintype "bidirectional"))
      (node (ref "U11") (pin "16") (pinfunction "AIN1_16") (pintype "input"))
      (node (ref "U2") (pin "C7") (pinfunction "GPIO4_C7") (pintype "bidirectional"))
    )
    (net (code "66") (name "EPWM3B") (class "Default")
      (node (ref "R25") (pin "1") (pinfunction "1_1") (pintype "bidirectional"))
      (node (ref "U11") (pin "15") (pinfunction "AIN2_15") (pintype "input"))
      (node (ref "U2") (pin "D7") (pinfunction "GPIO5_D7") (pintype "bidirectional"))
    )
    (net (code "67") (name "EPWM4A") (class "Default")
      (node (ref "R24") (pin "1") (pinfunction "1_1") (pintype "bidirectional"))
      (node (ref "U11") (pin "9") (pinfunction "BIN1_9") (pintype "input"))
      (node (ref "U2") (pin "A6") (pinfunction "GPIO6_A6") (pintype "bidirectional"))
    )
    (net (code "68") (name "EPWM4B") (class "Default")
      (node (ref "R23") (pin "1") (pinfunction "1_1") (pintype "bidirectional"))
      (node (ref "U11") (pin "10") (pinfunction "BIN2_10") (pintype "input"))
      (node (ref "U2") (pin "B6") (pinfunction "GPIO7_B6") (pintype "bidirectional"))
    )
    (net (code "69") (name "LNA1_N") (class "Default")
      (node (ref "C24") (pin "2") (pinfunction "2_2") (pintype "bidirectional"))
      (node (ref "L4") (pin "1") (pinfunction "1_1") (pintype "passive"))
      (node (ref "L5") (pin "2") (pinfunction "2_2") (pintype "passive"))
      (node (ref "U1") (pin "20") (pinfunction "LNA_N_20") (pintype "input"))
    )
    (net (code "70") (name "LNA1_P") (class "Default")
      (node (ref "C23") (pin "1") (pinfunction "1_1") (pintype "bidirectional"))
      (node (ref "L5") (pin "1") (pinfunction "1_1") (pintype "passive"))
      (node (ref "L6") (pin "2") (pinfunction "2_2") (pintype "passive"))
      (node (ref "U1") (pin "19") (pinfunction "LNA_P_19") (pintype "input"))
    )
    (net (code "71") (name "LNA2_N") (class "Default")
      (node (ref "C261") (pin "2") (pinfunction "2_2") (pintype "bidirectional"))
      (node (ref "L17") (pin "1") (pinfunction "1_1") (pintype "passive"))
      (node (ref "L18") (pin "2") (pinfunction "2_2") (pintype "passive"))
      (node (ref "U20") (pin "20") (pinfunction "LNA_N_20") (pintype "input"))
    )
    (net (code "72") (name "LNA2_P") (class "Default")
      (node (ref "C260") (pin "1") (pinfunction "1_1") (pintype "bidirectional"))
      (node (ref "L18") (pin "1") (pinfunction "1_1") (pintype "passive"))
      (node (ref "L19") (pin "2") (pinfunction "2_2") (pintype "passive"))
      (node (ref "U20") (pin "19") (pinfunction "LNA_P_19") (pintype "input"))
    )
    (net (code "73") (name "MAIN_CURRENT_ALERT") (class "Default")
      (node (ref "R67") (pin "2") (pinfunction "2_2") (pintype "bidirectional"))
      (node (ref "U18") (pin "3") (pinfunction "ALERT_3") (pintype "output"))
      (node (ref "U2") (pin "D3") (pinfunction "GPIO15_D3") (pintype "bidirectional"))
    )
    (net (code "74") (name "MTQ1_OUT1") (class "Default")
      (node (ref "JP5") (pin "1") (pinfunction "1_1") (pintype "passive"))
      (node (ref "U10") (pin "2") (pinfunction "AOUT1_2") (pintype "tri_state"))
    )
    (net (code "75") (name "MTQ1_OUT2") (class "Default")
      (node (ref "JP5") (pin "2") (pinfunction "2_2") (pintype "passive"))
      (node (ref "U10") (pin "4") (pinfunction "AOUT2_4") (pintype "tri_state"))
    )
    (net (code "76") (name "MTQ2_OUT1") (class "Default")
      (node (ref "JP6") (pin "1") (pinfunction "1_1") (pintype "passive"))
      (node (ref "U10") (pin "7") (pinfunction "BOUT1_7") (pintype "tri_state"))
    )
    (net (code "77") (name "MTQ2_OUT2") (class "Default")
      (node (ref "JP6") (pin "2") (pinfunction "2_2") (pintype "passive"))
      (node (ref "U10") (pin "5") (pinfunction "BOUT2_5") (pintype "tri_state"))
    )
    (net (code "78") (name "MTQ3_OUT1") (class "Default")
      (node (ref "JP7") (pin "1") (pinfunction "1_1") (pintype "passive"))
      (node (ref "U11") (pin "2") (pinfunction "AOUT1_2") (pintype "tri_state"))
    )
    (net (code "79") (name "MTQ3_OUT2") (class "Default")
      (node (ref "JP7") (pin "2") (pinfunction "2_2") (pintype "passive"))
      (node (ref "U11") (pin "4") (pinfunction "AOUT2_4") (pintype "tri_state"))
    )
    (net (code "80") (name "MTQ4_OUT1") (class "Default")
      (node (ref "JP8") (pin "1") (pinfunction "1_1") (pintype "passive"))
      (node (ref "U11") (pin "7") (pinfunction "BOUT1_7") (pintype "tri_state"))
    )
    (net (code "81") (name "MTQ4_OUT2") (class "Default")
      (node (ref "JP8") (pin "2") (pinfunction "2_2") (pintype "passive"))
      (node (ref "U11") (pin "5") (pinfunction "BOUT2_5") (pintype "tri_state"))
    )
    (net (code "82") (name "MTQ_12_ALERT") (class "Default")
      (node (ref "R32") (pin "2") (pinfunction "2_2") (pintype "bidirectional"))
      (node (ref "U13") (pin "3") (pinfunction "ALERT_3") (pintype "output"))
      (node (ref "U2") (pin "A11") (pinfunction "GPIO84_A11") (pintype "bidirectional"))
    )
    (net (code "83") (name "MTQ_12_VCC") (class "Default")
      (node (ref "C158") (pin "1") (pinfunction "1_1") (pintype "bidirectional"))
      (node (ref "C159") (pin "1") (pinfunction "1_1") (pintype "bidirectional"))
      (node (ref "C164") (pin "1") (pinfunction "1_1") (pintype "bidirectional"))
      (node (ref "C165") (pin "1") (pinfunction "1_1") (pintype "bidirectional"))
      (node (ref "C269") (pin "2") (pinfunction "2_2") (pintype "bidirectional"))
      (node (ref "R31") (pin "2") (pinfunction "2_2") (pintype "bidirectional"))
      (node (ref "U10") (pin "12") (pinfunction "VM_12") (pintype "power_in"))
      (node (ref "U13") (pin "9") (pinfunction "VIN-_9") (pintype "input"))
    )
    (net (code "84") (name "MTQ_34_ALERT") (class "Default")
      (node (ref "R30") (pin "2") (pinfunction "2_2") (pintype "bidirectional"))
      (node (ref "U12") (pin "3") (pinfunction "ALERT_3") (pintype "output"))
      (node (ref "U2") (pin "D11") (pinfunction "GPIO87_D11") (pintype "bidirectional"))
    )
    (net (code "85") (name "MTQ_34_VCC") (class "Default")
      (node (ref "C161") (pin "1") (pinfunction "1_1") (pintype "bidirectional"))
      (node (ref "C162") (pin "1") (pinfunction "1_1") (pintype "bidirectional"))
      (node (ref "C268") (pin "2") (pinfunction "2_2") (pintype "bidirectional"))
      (node (ref "R29") (pin "2") (pinfunction "2_2") (pintype "bidirectional"))
      (node (ref "U11") (pin "12") (pinfunction "VM_12") (pintype "power_in"))
      (node (ref "U12") (pin "9") (pinfunction "VIN-_9") (pintype "input"))
    )
    (net (code "86") (name "Net-(C20-Pad2)") (class "Default")
      (node (ref "C20") (pin "2") (pinfunction "2_2") (pintype "bidirectional"))
      (node (ref "C21") (pin "1") (pinfunction "1_1") (pintype "bidirectional"))
      (node (ref "L1") (pin "1") (pinfunction "1_1") (pintype "passive"))
    )
    (net (code "87") (name "Net-(C21-Pad2)") (class "Default")
      (node (ref "C21") (pin "2") (pinfunction "2_2") (pintype "bidirectional"))
      (node (ref "C22") (pin "1") (pinfunction "1_1") (pintype "bidirectional"))
      (node (ref "L1") (pin "2") (pinfunction "2_2") (pintype "passive"))
      (node (ref "L2") (pin "1") (pinfunction "1_1") (pintype "passive"))
    )
    (net (code "88") (name "Net-(C23-Pad2)") (class "Default")
      (node (ref "C23") (pin "2") (pinfunction "2_2") (pintype "bidirectional"))
      (node (ref "L3") (pin "1") (pinfunction "1_1") (pintype "passive"))
      (node (ref "L4") (pin "2") (pinfunction "2_2") (pintype "passive"))
    )
    (net (code "89") (name "Net-(C25-Pad1)") (class "Default")
      (node (ref "C25") (pin "1") (pinfunction "1_1") (pintype "bidirectional"))
      (node (ref "C26") (pin "1") (pinfunction "1_1") (pintype "bidirectional"))
      (node (ref "L2") (pin "2") (pinfunction "2_2") (pintype "passive"))
      (node (ref "L7") (pin "1") (pinfunction "1_1") (pintype "passive"))
    )
    (net (code "90") (name "Net-(C77-Pad2)") (class "Default")
      (node (ref "C77") (pin "2") (pinfunction "2_2") (pintype "bidirectional"))
      (node (ref "L9") (pin "2") (pinfunction "2_2") (pintype "passive"))
      (node (ref "R11") (pin "2") (pinfunction "2_2") (pintype "bidirectional"))
    )
    (net (code "91") (name "Net-(C232-Pad2)") (class "Default")
      (node (ref "C232") (pin "2") (pinfunction "2_2") (pintype "bidirectional"))
      (node (ref "L13") (pin "2") (pinfunction "2_2") (pintype "passive"))
      (node (ref "R80") (pin "2") (pinfunction "2_2") (pintype "bidirectional"))
    )
    (net (code "92") (name "Net-(C257-Pad2)") (class "Default")
      (node (ref "C257") (pin "2") (pinfunction "2_2") (pintype "bidirectional"))
      (node (ref "C258") (pin "1") (pinfunction "1_1") (pintype "bidirectional"))
      (node (ref "L14") (pin "1") (pinfunction "1_1") (pintype "passive"))
    )
    (net (code "93") (name "Net-(C258-Pad2)") (class "Default")
      (node (ref "C258") (pin "2") (pinfunction "2_2") (pintype "bidirectional"))
      (node (ref "C259") (pin "1") (pinfunction "1_1") (pintype "bidirectional"))
      (node (ref "L14") (pin "2") (pinfunction "2_2") (pintype "passive"))
      (node (ref "L15") (pin "1") (pinfunction "1_1") (pintype "passive"))
    )
    (net (code "94") (name "Net-(C260-Pad2)") (class "Default")
      (node (ref "C260") (pin "2") (pinfunction "2_2") (pintype "bidirectional"))
      (node (ref "L16") (pin "1") (pinfunction "1_1") (pintype "passive"))
      (node (ref "L17") (pin "2") (pinfunction "2_2") (pintype "passive"))
    )
    (net (code "95") (name "Net-(C262-Pad1)") (class "Default")
      (node (ref "C262") (pin "1") (pinfunction "1_1") (pintype "bidirectional"))
      (node (ref "C263") (pin "1") (pinfunction "1_1") (pintype "bidirectional"))
      (node (ref "L15") (pin "2") (pinfunction "2_2") (pintype "passive"))
      (node (ref "L20") (pin "1") (pinfunction "1_1") (pintype "passive"))
    )
    (net (code "96") (name "Net-(IC1-I{slash}O_14)") (class "Default")
      (node (ref "IC1") (pin "21") (pinfunction "I/O_14_21") (pintype "bidirectional"))
      (node (ref "R71") (pin "1") (pinfunction "1_1") (pintype "bidirectional"))
    )
    (net (code "97") (name "Net-(IC1-TCK)") (class "Default")
      (node (ref "IC1") (pin "11") (pinfunction "TCK_11") (pintype "bidirectional"))
      (node (ref "X5") (pin "4") (pinfunction "KL_4") (pintype "passive"))
    )
    (net (code "98") (name "Net-(IC1-TDI)") (class "Default")
      (node (ref "IC1") (pin "9") (pinfunction "TDI_9") (pintype "input"))
      (node (ref "X5") (pin "8") (pinfunction "KL_8") (pintype "passive"))
    )
    (net (code "99") (name "Net-(IC1-TDO)") (class "Default")
      (node (ref "IC1") (pin "24") (pinfunction "TDO_24") (pintype "output"))
      (node (ref "X5") (pin "6") (pinfunction "KL_6") (pintype "passive"))
    )
    (net (code "100") (name "Net-(IC1-TMS)") (class "Default")
      (node (ref "IC1") (pin "10") (pinfunction "TMS_10") (pintype "bidirectional"))
      (node (ref "X5") (pin "2") (pinfunction "KL_2") (pintype "passive"))
    )
    (net (code "101") (name "Net-(L12-P$1)") (class "Default")
      (node (ref "C207") (pin "2") (pinfunction "2_2") (pintype "bidirectional"))
      (node (ref "L12") (pin "1") (pinfunction "P$1_1") (pintype "bidirectional"))
      (node (ref "U19") (pin "6") (pinfunction "SW_2_6") (pintype "passive"))
      (node (ref "U19") (pin "7") (pinfunction "SW_3_7") (pintype "passive"))
      (node (ref "U19") (pin "8") (pinfunction "SW_4_8") (pintype "passive"))
      (node (ref "U19") (pin "9") (pinfunction "SW_9") (pintype "passive"))
    )
    (net (code "102") (name "Net-(U1-DCPL)") (class "Default")
      (node (ref "C53") (pin "2") (pinfunction "2_2") (pintype "bidirectional"))
      (node (ref "U1") (pin "6") (pinfunction "DCPL_6") (pintype "power_in"))
    )
    (net (code "103") (name "Net-(U1-DCPL_PFD_CHP)") (class "Default")
      (node (ref "C56") (pin "2") (pinfunction "2_2") (pintype "bidirectional"))
      (node (ref "U1") (pin "26") (pinfunction "DCPL_PFD_CHP_26") (pintype "power_in"))
    )
    (net (code "104") (name "Net-(U1-DCPL_VCO)") (class "Default")
      (node (ref "C54") (pin "2") (pinfunction "2_2") (pintype "bidirectional"))
      (node (ref "U1") (pin "21") (pinfunction "DCPL_VCO_21") (pintype "power_in"))
    )
    (net (code "105") (name "Net-(U1-DCPL_XOSC)") (class "Default")
      (node (ref "C55") (pin "2") (pinfunction "2_2") (pintype "bidirectional"))
      (node (ref "R35") (pin "2") (pinfunction "2_2") (pintype "bidirectional"))
      (node (ref "U1") (pin "29") (pinfunction "DCPL_XOSC_29") (pintype "power_in"))
    )
    (net (code "106") (name "Net-(U1-LPF0)") (class "Default")
      (node (ref "C52") (pin "2") (pinfunction "2_2") (pintype "bidirectional"))
      (node (ref "U1") (pin "23") (pinfunction "LPF0_23") (pintype "passive"))
    )
    (net (code "107") (name "Net-(U1-LPF1)") (class "Default")
      (node (ref "C52") (pin "1") (pinfunction "1_1") (pintype "bidirectional"))
      (node (ref "U1") (pin "24") (pinfunction "LPF1_24") (pintype "passive"))
    )
    (net (code "108") (name "Net-(U1-RBIAS)") (class "Default")
      (node (ref "R33") (pin "1") (pinfunction "1_1") (pintype "bidirectional"))
      (node (ref "U1") (pin "14") (pinfunction "RBIAS_14") (pintype "passive"))
    )
    (net (code "109") (name "Net-(U1-XOSC_Q1)") (class "Default")
      (node (ref "C49") (pin "1") (pinfunction "1_1") (pintype "bidirectional"))
      (node (ref "U1") (pin "30") (pinfunction "XOSC_Q1_30") (pintype "passive"))
      (node (ref "X1") (pin "3") (pinfunction "XO_3") (pintype "bidirectional"))
    )
    (net (code "110") (name "Net-(U1-XOSC_Q2)") (class "Default")
      (node (ref "C50") (pin "1") (pinfunction "1_1") (pintype "bidirectional"))
      (node (ref "U1") (pin "31") (pinfunction "XOSC_Q2_31") (pintype "passive"))
      (node (ref "X1") (pin "1") (pinfunction "XI_1") (pintype "bidirectional"))
    )
    (net (code "111") (name "Net-(U2C-X1)") (class "Default")
      (node (ref "U2") (pin "G19") (pinfunction "X1_G19") (pintype "passive"))
      (node (ref "Y2") (pin "3") (pinfunction "XO_3") (pintype "bidirectional"))
    )
    (net (code "112") (name "Net-(U2C-X2)") (class "Default")
      (node (ref "U2") (pin "J19") (pinfunction "X2_J19") (pintype "passive"))
      (node (ref "Y2") (pin "1") (pinfunction "XI_1") (pintype "bidirectional"))
    )
    (net (code "113") (name "Net-(U2E-GPIO83)") (class "Default")
      (node (ref "R72") (pin "1") (pinfunction "1_1") (pintype "bidirectional"))
      (node (ref "U2") (pin "C14") (pinfunction "GPIO83_C14") (pintype "bidirectional"))
    )
    (net (code "114") (name "Net-(U3-OSC0)") (class "Default")
      (node (ref "U3") (pin "40") (pinfunction "OSC0_40") (pintype "input"))
      (node (ref "Y1") (pin "1") (pinfunction "XI_1") (pintype "bidirectional"))
    )
    (net (code "115") (name "Net-(U3-OSC1)") (class "Default")
      (node (ref "U3") (pin "41") (pinfunction "OSC1_41") (pintype "output"))
      (node (ref "Y1") (pin "3") (pinfunction "XO_3") (pintype "bidirectional"))
    )
    (net (code "116") (name "Net-(U3-PC0_TCK_SWCLK)") (class "Default")
      (node (ref "U3") (pin "52") (pinfunction "PC0_TCK_SWCLK_52") (pintype "bidirectional"))
      (node (ref "X3") (pin "4") (pinfunction "KL_4") (pintype "passive"))
    )
    (net (code "117") (name "Net-(U3-PC1_TMS_SWDIO)") (class "Default")
      (node (ref "U3") (pin "51") (pinfunction "PC1_TMS_SWDIO_51") (pintype "bidirectional"))
      (node (ref "X3") (pin "2") (pinfunction "KL_2") (pintype "passive"))
    )
    (net (code "118") (name "Net-(U3-PC2_TDI)") (class "Default")
      (node (ref "U3") (pin "50") (pinfunction "PC2_TDI_50") (pintype "bidirectional"))
      (node (ref "X3") (pin "8") (pinfunction "KL_8") (pintype "passive"))
    )
    (net (code "119") (name "Net-(U3-PC3_TDO_SWO)") (class "Default")
      (node (ref "U3") (pin "49") (pinfunction "PC3_TDO_SWO_49") (pintype "bidirectional"))
      (node (ref "X3") (pin "6") (pinfunction "KL_6") (pintype "passive"))
    )
    (net (code "120") (name "Net-(U3-RST_N)") (class "Default")
      (node (ref "C30") (pin "1") (pinfunction "1_1") (pintype "bidirectional"))
      (node (ref "R8") (pin "2") (pinfunction "2_2") (pintype "bidirectional"))
      (node (ref "U3") (pin "38") (pinfunction "RST_N_38") (pintype "input"))
      (node (ref "U5") (pin "4") (pinfunction "Y_4") (pintype "output"))
    )
    (net (code "121") (name "Net-(U3-VDDC)") (class "Default")
      (node (ref "C5") (pin "1") (pinfunction "1_1") (pintype "bidirectional"))
      (node (ref "C6") (pin "1") (pinfunction "1_1") (pintype "bidirectional"))
      (node (ref "C7") (pin "1") (pinfunction "1_1") (pintype "bidirectional"))
      (node (ref "C8") (pin "1") (pinfunction "1_1") (pintype "bidirectional"))
      (node (ref "U3") (pin "25") (pinfunction "VDDC_2_25") (pintype "power_in"))
      (node (ref "U3") (pin "56") (pinfunction "VDDC_56") (pintype "power_in"))
    )
    (net (code "122") (name "Net-(U10-AISEN)") (class "Default")
      (node (ref "R19") (pin "1") (pinfunction "1_1") (pintype "bidirectional"))
      (node (ref "U10") (pin "3") (pinfunction "AISEN_3") (pintype "input"))
    )
    (net (code "123") (name "Net-(U10-BISEN)") (class "Default")
      (node (ref "R20") (pin "1") (pinfunction "1_1") (pintype "bidirectional"))
      (node (ref "U10") (pin "6") (pinfunction "BISEN_6") (pintype "input"))
    )
    (net (code "124") (name "Net-(U10-VINT)") (class "Default")
      (node (ref "C157") (pin "1") (pinfunction "1_1") (pintype "bidirectional"))
      (node (ref "U10") (pin "14") (pinfunction "VINT_14") (pintype "passive"))
    )
    (net (code "125") (name "Net-(U11-AISEN)") (class "Default")
      (node (ref "R27") (pin "1") (pinfunction "1_1") (pintype "bidirectional"))
      (node (ref "U11") (pin "3") (pinfunction "AISEN_3") (pintype "input"))
    )
    (net (code "126") (name "Net-(U11-BISEN)") (class "Default")
      (node (ref "R28") (pin "1") (pinfunction "1_1") (pintype "bidirectional"))
      (node (ref "U11") (pin "6") (pinfunction "BISEN_6") (pintype "input"))
    )
    (net (code "127") (name "Net-(U11-VINT)") (class "Default")
      (node (ref "C160") (pin "1") (pinfunction "1_1") (pintype "bidirectional"))
      (node (ref "U11") (pin "14") (pinfunction "VINT_14") (pintype "passive"))
    )
    (net (code "128") (name "Net-(U15-~{HOLD}{slash}SO3)") (class "Default")
      (node (ref "R46") (pin "2") (pinfunction "2_2") (pintype "bidirectional"))
      (node (ref "R47") (pin "1") (pinfunction "1_1") (pintype "bidirectional"))
      (node (ref "U15") (pin "7") (pinfunction "~{HOLD}/SO3_7") (pintype "bidirectional"))
    )
    (net (code "129") (name "Net-(U15-~{WP}{slash}SO2)") (class "Default")
      (node (ref "R44") (pin "2") (pinfunction "2_2") (pintype "bidirectional"))
      (node (ref "R45") (pin "1") (pinfunction "1_1") (pintype "bidirectional"))
      (node (ref "U15") (pin "3") (pinfunction "~{WP}/SO2_3") (pintype "bidirectional"))
    )
    (net (code "130") (name "Net-(U16-~{HOLD}{slash}SO3)") (class "Default")
      (node (ref "R50") (pin "2") (pinfunction "2_2") (pintype "bidirectional"))
      (node (ref "R51") (pin "1") (pinfunction "1_1") (pintype "bidirectional"))
      (node (ref "U16") (pin "7") (pinfunction "~{HOLD}/SO3_7") (pintype "bidirectional"))
    )
    (net (code "131") (name "Net-(U16-~{WP}{slash}SO2)") (class "Default")
      (node (ref "R48") (pin "2") (pinfunction "2_2") (pintype "bidirectional"))
      (node (ref "R49") (pin "1") (pinfunction "1_1") (pintype "bidirectional"))
      (node (ref "U16") (pin "3") (pinfunction "~{WP}/SO2_3") (pintype "bidirectional"))
    )
    (net (code "132") (name "Net-(U17-RF1)") (class "Default")
      (node (ref "L10") (pin "2") (pinfunction "2_2") (pintype "passive"))
      (node (ref "U17") (pin "5") (pinfunction "RF1_5") (pintype "bidirectional"))
    )
    (net (code "133") (name "Net-(U17-RF2)") (class "Default")
      (node (ref "L11") (pin "2") (pinfunction "2_2") (pintype "passive"))
      (node (ref "U17") (pin "11") (pinfunction "RF2_11") (pintype "bidirectional"))
    )
    (net (code "134") (name "Net-(U17-RFC)") (class "Default")
      (node (ref "L8") (pin "1") (pinfunction "1_1") (pintype "passive"))
      (node (ref "U17") (pin "2") (pinfunction "RFC_2") (pintype "bidirectional"))
    )
    (net (code "135") (name "Net-(U19-MODE)") (class "Default")
      (node (ref "R76") (pin "2") (pinfunction "2_2") (pintype "bidirectional"))
      (node (ref "U19") (pin "21") (pinfunction "MODE_21") (pintype "passive"))
    )
    (net (code "136") (name "Net-(U19-RF)") (class "Default")
      (node (ref "R69") (pin "2") (pinfunction "2_2") (pintype "bidirectional"))
      (node (ref "R70") (pin "1") (pinfunction "1_1") (pintype "bidirectional"))
      (node (ref "U19") (pin "1") (pinfunction "RF_1") (pintype "passive"))
    )
    (net (code "137") (name "Net-(U19-TRIP)") (class "Default")
      (node (ref "R75") (pin "2") (pinfunction "2_2") (pintype "bidirectional"))
      (node (ref "U19") (pin "25") (pinfunction "TRIP_25") (pintype "passive"))
    )
    (net (code "138") (name "Net-(U19-VBST)") (class "Default")
      (node (ref "C207") (pin "1") (pinfunction "1_1") (pintype "bidirectional"))
      (node (ref "U19") (pin "4") (pinfunction "VBST_4") (pintype "passive"))
    )
    (net (code "139") (name "Net-(U20-DCPL)") (class "Default")
      (node (ref "C217") (pin "2") (pinfunction "2_2") (pintype "bidirectional"))
      (node (ref "U20") (pin "6") (pinfunction "DCPL_6") (pintype "power_in"))
    )
    (net (code "140") (name "Net-(U20-DCPL_PFD_CHP)") (class "Default")
      (node (ref "C220") (pin "2") (pinfunction "2_2") (pintype "bidirectional"))
      (node (ref "U20") (pin "26") (pinfunction "DCPL_PFD_CHP_26") (pintype "power_in"))
    )
    (net (code "141") (name "Net-(U20-DCPL_VCO)") (class "Default")
      (node (ref "C218") (pin "2") (pinfunction "2_2") (pintype "bidirectional"))
      (node (ref "U20") (pin "21") (pinfunction "DCPL_VCO_21") (pintype "power_in"))
    )
    (net (code "142") (name "Net-(U20-DCPL_XOSC)") (class "Default")
      (node (ref "C219") (pin "2") (pinfunction "2_2") (pintype "bidirectional"))
      (node (ref "R79") (pin "2") (pinfunction "2_2") (pintype "bidirectional"))
      (node (ref "U20") (pin "29") (pinfunction "DCPL_XOSC_29") (pintype "power_in"))
    )
    (net (code "143") (name "Net-(U20-LPF0)") (class "Default")
      (node (ref "C216") (pin "2") (pinfunction "2_2") (pintype "bidirectional"))
      (node (ref "U20") (pin "23") (pinfunction "LPF0_23") (pintype "passive"))
    )
    (net (code "144") (name "Net-(U20-LPF1)") (class "Default")
      (node (ref "C216") (pin "1") (pinfunction "1_1") (pintype "bidirectional"))
      (node (ref "U20") (pin "24") (pinfunction "LPF1_24") (pintype "passive"))
    )
    (net (code "145") (name "Net-(U20-RBIAS)") (class "Default")
      (node (ref "R77") (pin "1") (pinfunction "1_1") (pintype "bidirectional"))
      (node (ref "U20") (pin "14") (pinfunction "RBIAS_14") (pintype "passive"))
    )
    (net (code "146") (name "Net-(U20-XOSC_Q1)") (class "Default")
      (node (ref "C213") (pin "1") (pinfunction "1_1") (pintype "bidirectional"))
      (node (ref "U20") (pin "30") (pinfunction "XOSC_Q1_30") (pintype "passive"))
      (node (ref "X7") (pin "3") (pinfunction "XO_3") (pintype "bidirectional"))
    )
    (net (code "147") (name "Net-(U20-XOSC_Q2)") (class "Default")
      (node (ref "C214") (pin "1") (pinfunction "1_1") (pintype "bidirectional"))
      (node (ref "U20") (pin "31") (pinfunction "XOSC_Q2_31") (pintype "passive"))
      (node (ref "X7") (pin "1") (pinfunction "XI_1") (pintype "bidirectional"))
    )
    (net (code "148") (name "Net-(U21-OSC0)") (class "Default")
      (node (ref "U21") (pin "40") (pinfunction "OSC0_40") (pintype "input"))
      (node (ref "Y3") (pin "1") (pinfunction "XI_1") (pintype "bidirectional"))
    )
    (net (code "149") (name "Net-(U21-OSC1)") (class "Default")
      (node (ref "U21") (pin "41") (pinfunction "OSC1_41") (pintype "output"))
      (node (ref "Y3") (pin "3") (pinfunction "XO_3") (pintype "bidirectional"))
    )
    (net (code "150") (name "Net-(U21-PC0_TCK_SWCLK)") (class "Default")
      (node (ref "U21") (pin "52") (pinfunction "PC0_TCK_SWCLK_52") (pintype "bidirectional"))
      (node (ref "X8") (pin "4") (pinfunction "KL_4") (pintype "passive"))
    )
    (net (code "151") (name "Net-(U21-PC1_TMS_SWDIO)") (class "Default")
      (node (ref "U21") (pin "51") (pinfunction "PC1_TMS_SWDIO_51") (pintype "bidirectional"))
      (node (ref "X8") (pin "2") (pinfunction "KL_2") (pintype "passive"))
    )
    (net (code "152") (name "Net-(U21-PC2_TDI)") (class "Default")
      (node (ref "U21") (pin "50") (pinfunction "PC2_TDI_50") (pintype "bidirectional"))
      (node (ref "X8") (pin "8") (pinfunction "KL_8") (pintype "passive"))
    )
    (net (code "153") (name "Net-(U21-PC3_TDO_SWO)") (class "Default")
      (node (ref "U21") (pin "49") (pinfunction "PC3_TDO_SWO_49") (pintype "bidirectional"))
      (node (ref "X8") (pin "6") (pinfunction "KL_6") (pintype "passive"))
    )
    (net (code "154") (name "Net-(U21-RST_N)") (class "Default")
      (node (ref "C235") (pin "1") (pinfunction "1_1") (pintype "bidirectional"))
      (node (ref "R84") (pin "2") (pinfunction "2_2") (pintype "bidirectional"))
      (node (ref "U21") (pin "38") (pinfunction "RST_N_38") (pintype "input"))
      (node (ref "U23") (pin "4") (pinfunction "Y_4") (pintype "output"))
    )
    (net (code "155") (name "Net-(U21-VDDC)") (class "Default")
      (node (ref "C242") (pin "1") (pinfunction "1_1") (pintype "bidirectional"))
      (node (ref "C243") (pin "1") (pinfunction "1_1") (pintype "bidirectional"))
      (node (ref "C244") (pin "1") (pinfunction "1_1") (pintype "bidirectional"))
      (node (ref "C245") (pin "1") (pinfunction "1_1") (pintype "bidirectional"))
      (node (ref "U21") (pin "25") (pinfunction "VDDC_2_25") (pintype "power_in"))
      (node (ref "U21") (pin "56") (pinfunction "VDDC_56") (pintype "power_in"))
    )
    (net (code "156") (name "Net-(U24-~{HOLD}{slash}SO3)") (class "Default")
      (node (ref "R89") (pin "2") (pinfunction "2_2") (pintype "bidirectional"))
      (node (ref "R90") (pin "1") (pinfunction "1_1") (pintype "bidirectional"))
      (node (ref "U24") (pin "7") (pinfunction "~{HOLD}/SO3_7") (pintype "bidirectional"))
    )
    (net (code "157") (name "Net-(U24-~{WP}{slash}SO2)") (class "Default")
      (node (ref "R87") (pin "2") (pinfunction "2_2") (pintype "bidirectional"))
      (node (ref "R88") (pin "1") (pinfunction "1_1") (pintype "bidirectional"))
      (node (ref "U24") (pin "3") (pinfunction "~{WP}/SO2_3") (pintype "bidirectional"))
    )
    (net (code "158") (name "Net-(X3B-KL)") (class "Default")
      (node (ref "R5") (pin "1") (pinfunction "1_1") (pintype "bidirectional"))
      (node (ref "X3") (pin "10") (pinfunction "KL_10") (pintype "passive"))
    )
    (net (code "159") (name "Net-(X8B-KL)") (class "Default")
      (node (ref "R81") (pin "1") (pinfunction "1_1") (pintype "bidirectional"))
      (node (ref "X8") (pin "10") (pinfunction "KL_10") (pintype "passive"))
    )
    (net (code "160") (name "PA") (class "Default")
      (node (ref "C20") (pin "1") (pinfunction "1_1") (pintype "bidirectional"))
      (node (ref "C257") (pin "1") (pinfunction "1_1") (pintype "bidirectional"))
      (node (ref "L13") (pin "1") (pinfunction "1_1") (pintype "passive"))
      (node (ref "L9") (pin "1") (pinfunction "1_1") (pintype "passive"))
      (node (ref "U1") (pin "17") (pinfunction "PA_17") (pintype "input"))
      (node (ref "U20") (pin "17") (pinfunction "PA_17") (pintype "input"))
    )
    (net (code "161") (name "RF_MUX_CTRL") (class "Default")
      (node (ref "C193") (pin "1") (pinfunction "1_1") (pintype "bidirectional"))
      (node (ref "C194") (pin "1") (pinfunction "1_1") (pintype "bidirectional"))
      (node (ref "IC1") (pin "20") (pinfunction "I/O_13_20") (pintype "bidirectional"))
      (node (ref "R65") (pin "1") (pinfunction "1_1") (pintype "bidirectional"))
      (node (ref "U17") (pin "7") (pinfunction "CTRL_7") (pintype "bidirectional"))
    )
    (net (code "162") (name "RF_MUX_EN") (class "Default")
      (node (ref "C192") (pin "1") (pinfunction "1_1") (pintype "bidirectional"))
      (node (ref "R64") (pin "2") (pinfunction "2_2") (pintype "bidirectional"))
      (node (ref "U17") (pin "8") (pinfunction "EN_8") (pintype "bidirectional"))
    )
    (net (code "163") (name "SDRAM_A0") (class "Default")
      (node (ref "U2") (pin "T14") (pinfunction "GPIO35_T14") (pintype "bidirectional"))
      (node (ref "U6") (pin "H7") (pinfunction "A0_H7") (pintype "bidirectional"))
    )
    (net (code "164") (name "SDRAM_A1") (class "Default")
      (node (ref "U2") (pin "V16") (pinfunction "GPIO36_V16") (pintype "bidirectional"))
      (node (ref "U6") (pin "H8") (pinfunction "A1_H8") (pintype "bidirectional"))
    )
    (net (code "165") (name "SDRAM_A2") (class "Default")
      (node (ref "U2") (pin "U16") (pinfunction "GPIO37_U16") (pintype "bidirectional"))
      (node (ref "U6") (pin "J8") (pinfunction "A2_J8") (pintype "bidirectional"))
    )
    (net (code "166") (name "SDRAM_A3") (class "Default")
      (node (ref "U2") (pin "T16") (pinfunction "GPIO38_T16") (pintype "bidirectional"))
      (node (ref "U6") (pin "J7") (pinfunction "A3_J7") (pintype "bidirectional"))
    )
    (net (code "167") (name "SDRAM_A4") (class "Default")
      (node (ref "U2") (pin "W17") (pinfunction "GPIO39_W17") (pintype "bidirectional"))
      (node (ref "U6") (pin "J3") (pinfunction "A4_J3") (pintype "bidirectional"))
    )
    (net (code "168") (name "SDRAM_A5") (class "Default")
      (node (ref "U2") (pin "K19") (pinfunction "GPIO45_K19") (pintype "bidirectional"))
      (node (ref "U6") (pin "J2") (pinfunction "A5_J2") (pintype "bidirectional"))
    )
    (net (code "169") (name "SDRAM_A6") (class "Default")
      (node (ref "U2") (pin "E19") (pinfunction "GPIO46_E19") (pintype "bidirectional"))
      (node (ref "U6") (pin "H3") (pinfunction "A6_H3") (pintype "bidirectional"))
    )
    (net (code "170") (name "SDRAM_A7") (class "Default")
      (node (ref "U2") (pin "E18") (pinfunction "GPIO47_E18") (pintype "bidirectional"))
      (node (ref "U6") (pin "H2") (pinfunction "A7_H2") (pintype "bidirectional"))
    )
    (net (code "171") (name "SDRAM_A8") (class "Default")
      (node (ref "U2") (pin "R16") (pinfunction "GPIO48_R16") (pintype "bidirectional"))
      (node (ref "U6") (pin "H1") (pinfunction "A8_H1") (pintype "bidirectional"))
    )
    (net (code "172") (name "SDRAM_A9") (class "Default")
      (node (ref "U2") (pin "R17") (pinfunction "GPIO49_R17") (pintype "bidirectional"))
      (node (ref "U6") (pin "G3") (pinfunction "A9_G3") (pintype "bidirectional"))
    )
    (net (code "173") (name "SDRAM_A10") (class "Default")
      (node (ref "U2") (pin "R18") (pinfunction "GPIO50_R18") (pintype "bidirectional"))
      (node (ref "U6") (pin "H9") (pinfunction "A10_H9") (pintype "bidirectional"))
    )
    (net (code "174") (name "SDRAM_A11") (class "Default")
      (node (ref "U2") (pin "R19") (pinfunction "GPIO51_R19") (pintype "bidirectional"))
      (node (ref "U6") (pin "G2") (pinfunction "A11_G2") (pintype "bidirectional"))
    )
    (net (code "175") (name "SDRAM_A12") (class "Default")
      (node (ref "U2") (pin "P16") (pinfunction "GPIO52_P16") (pintype "bidirectional"))
      (node (ref "U6") (pin "G1") (pinfunction "A12_G1") (pintype "bidirectional"))
    )
    (net (code "176") (name "SDRAM_BA0") (class "Default")
      (node (ref "U2") (pin "T13") (pinfunction "GPIO33_T13") (pintype "bidirectional"))
      (node (ref "U6") (pin "G7") (pinfunction "BA0_G7") (pintype "bidirectional"))
    )
    (net (code "177") (name "SDRAM_BA1") (class "Default")
      (node (ref "U2") (pin "U14") (pinfunction "GPIO34_U14") (pintype "bidirectional"))
      (node (ref "U6") (pin "G8") (pinfunction "BA1_G8") (pintype "bidirectional"))
    )
    (net (code "178") (name "SDRAM_CKE") (class "Default")
      (node (ref "U2") (pin "W11") (pinfunction "GPIO29_W11") (pintype "bidirectional"))
      (node (ref "U6") (pin "F3") (pinfunction "CKE_F3") (pintype "bidirectional"))
    )
    (net (code "179") (name "SDRAM_CLK") (class "Default")
      (node (ref "U2") (pin "T11") (pinfunction "GPIO30_T11") (pintype "bidirectional"))
      (node (ref "U6") (pin "F2") (pinfunction "CLK_F2") (pintype "bidirectional"))
    )
    (net (code "180") (name "SDRAM_D0") (class "Default")
      (node (ref "U2") (pin "P19") (pinfunction "GPIO55_P19") (pintype "bidirectional"))
      (node (ref "U6") (pin "A8") (pinfunction "DQ0_A8") (pintype "bidirectional"))
    )
    (net (code "181") (name "SDRAM_D1") (class "Default")
      (node (ref "U2") (pin "N16") (pinfunction "GPIO56_N16") (pintype "bidirectional"))
      (node (ref "U6") (pin "B9") (pinfunction "DQ1_B9") (pintype "bidirectional"))
    )
    (net (code "182") (name "SDRAM_D2") (class "Default")
      (node (ref "U2") (pin "N18") (pinfunction "GPIO57_N18") (pintype "bidirectional"))
      (node (ref "U6") (pin "B8") (pinfunction "DQ2_B8") (pintype "bidirectional"))
    )
    (net (code "183") (name "SDRAM_D3") (class "Default")
      (node (ref "U2") (pin "N17") (pinfunction "GPIO58_N17") (pintype "bidirectional"))
      (node (ref "U6") (pin "C9") (pinfunction "DQ3_C9") (pintype "bidirectional"))
    )
    (net (code "184") (name "SDRAM_D4") (class "Default")
      (node (ref "U2") (pin "M16") (pinfunction "GPIO59_M16") (pintype "bidirectional"))
      (node (ref "U6") (pin "C8") (pinfunction "DQ4_C8") (pintype "bidirectional"))
    )
    (net (code "185") (name "SDRAM_D5") (class "Default")
      (node (ref "U2") (pin "M17") (pinfunction "GPIO60_M17") (pintype "bidirectional"))
      (node (ref "U6") (pin "D9") (pinfunction "DQ5_D9") (pintype "bidirectional"))
    )
    (net (code "186") (name "SDRAM_D6") (class "Default")
      (node (ref "U2") (pin "L16") (pinfunction "GPIO61_L16") (pintype "bidirectional"))
      (node (ref "U6") (pin "D8") (pinfunction "DQ6_D8") (pintype "bidirectional"))
    )
    (net (code "187") (name "SDRAM_D7") (class "Default")
      (node (ref "U2") (pin "J17") (pinfunction "GPIO62_J17") (pintype "bidirectional"))
      (node (ref "U6") (pin "E9") (pinfunction "DQ7_E9") (pintype "bidirectional"))
    )
    (net (code "188") (name "SDRAM_D8") (class "Default")
      (node (ref "U2") (pin "C16") (pinfunction "GPIO76_C16") (pintype "bidirectional"))
      (node (ref "U6") (pin "E1") (pinfunction "DQ8_E1") (pintype "bidirectional"))
    )
    (net (code "189") (name "SDRAM_D9") (class "Default")
      (node (ref "U2") (pin "D16") (pinfunction "GPIO75_D16") (pintype "bidirectional"))
      (node (ref "U6") (pin "D2") (pinfunction "DQ9_D2") (pintype "bidirectional"))
    )
    (net (code "190") (name "SDRAM_D10") (class "Default")
      (node (ref "U2") (pin "C17") (pinfunction "GPIO74_C17") (pintype "bidirectional"))
      (node (ref "U6") (pin "D1") (pinfunction "DQ10_D1") (pintype "bidirectional"))
    )
    (net (code "191") (name "SDRAM_D11") (class "Default")
      (node (ref "U2") (pin "A16") (pinfunction "GPIO73_A16") (pintype "bidirectional"))
      (node (ref "U6") (pin "C2") (pinfunction "DQ11_C2") (pintype "bidirectional"))
    )
    (net (code "192") (name "SDRAM_D12") (class "Default")
      (node (ref "U2") (pin "B16") (pinfunction "GPIO72_B16") (pintype "bidirectional"))
      (node (ref "U6") (pin "C1") (pinfunction "DQ12_C1") (pintype "bidirectional"))
    )
    (net (code "193") (name "SDRAM_D13") (class "Default")
      (node (ref "U2") (pin "B17") (pinfunction "GPIO71_B17") (pintype "bidirectional"))
      (node (ref "U6") (pin "B2") (pinfunction "DQ13_B2") (pintype "bidirectional"))
    )
    (net (code "194") (name "SDRAM_D14") (class "Default")
      (node (ref "U2") (pin "A17") (pinfunction "GPIO70_A17") (pintype "bidirectional"))
      (node (ref "U6") (pin "B1") (pinfunction "DQ14_B1") (pintype "bidirectional"))
    )
    (net (code "195") (name "SDRAM_D15") (class "Default")
      (node (ref "U2") (pin "B18") (pinfunction "GPIO69_B18") (pintype "bidirectional"))
      (node (ref "U6") (pin "A2") (pinfunction "DQ15_A2") (pintype "bidirectional"))
    )
    (net (code "196") (name "SDRAM_DQM0") (class "Default")
      (node (ref "U2") (pin "K3") (pinfunction "GPIO24_K3") (pintype "bidirectional"))
      (node (ref "U6") (pin "E8") (pinfunction "DQML_E8") (pintype "bidirectional"))
    )
    (net (code "197") (name "SDRAM_DQM1") (class "Default")
      (node (ref "U2") (pin "K2") (pinfunction "GPIO25_K2") (pintype "bidirectional"))
      (node (ref "U6") (pin "F1") (pinfunction "DQMH_F1") (pintype "bidirectional"))
    )
    (net (code "198") (name "SMC_ERR_CPLD_IN") (class "Default")
      (node (ref "IC1") (pin "3") (pinfunction "I/O_2_3") (pintype "bidirectional"))
      (node (ref "R43") (pin "2") (pinfunction "2_2") (pintype "bidirectional"))
    )
    (net (code "199") (name "SMC_ERR_OUT") (class "Default")
      (node (ref "R43") (pin "1") (pinfunction "1_1") (pintype "bidirectional"))
      (node (ref "R9") (pin "1") (pinfunction "1_1") (pintype "bidirectional"))
      (node (ref "U2") (pin "U19") (pinfunction "ERRORSTS_U19") (pintype "passive"))
    )
    (net (code "200") (name "SMC_I2C0_SCL") (class "Default")
      (node (ref "J1") (pin "A2") (pinfunction "2_A2") (pintype "bidirectional"))
      (node (ref "R37") (pin "2") (pinfunction "2_2") (pintype "bidirectional"))
      (node (ref "U12") (pin "5") (pinfunction "SCL_5") (pintype "input"))
      (node (ref "U13") (pin "5") (pinfunction "SCL_5") (pintype "input"))
      (node (ref "U18") (pin "5") (pinfunction "SCL_5") (pintype "input"))
      (node (ref "U2") (pin "J3") (pinfunction "GPIO105_J3") (pintype "bidirectional"))
      (node (ref "U34") (pin "P$1") (pinfunction "SCL_P$1") (pintype "bidirectional"))
      (node (ref "U7") (pin "P$1") (pinfunction "SCL_P$1") (pintype "bidirectional"))
      (node (ref "U8") (pin "13") (pinfunction "SCX_13") (pintype "input"))
      (node (ref "U9") (pin "13") (pinfunction "SCX_13") (pintype "input"))
    )
    (net (code "201") (name "SMC_I2C0_SDA") (class "Default")
      (node (ref "J1") (pin "A1") (pinfunction "1_A1") (pintype "bidirectional"))
      (node (ref "R36") (pin "2") (pinfunction "2_2") (pintype "bidirectional"))
      (node (ref "U12") (pin "4") (pinfunction "SDA_4") (pintype "bidirectional"))
      (node (ref "U13") (pin "4") (pinfunction "SDA_4") (pintype "bidirectional"))
      (node (ref "U18") (pin "2") (pinfunction "A0_2") (pintype "passive"))
      (node (ref "U18") (pin "4") (pinfunction "SDA_4") (pintype "bidirectional"))
      (node (ref "U2") (pin "J2") (pinfunction "GPIO104_J2") (pintype "bidirectional"))
      (node (ref "U34") (pin "P$6") (pinfunction "SDA_P$6") (pintype "bidirectional"))
      (node (ref "U7") (pin "P$6") (pinfunction "SDA_P$6") (pintype "bidirectional"))
      (node (ref "U8") (pin "14") (pinfunction "SDX_14") (pintype "bidirectional"))
      (node (ref "U9") (pin "14") (pinfunction "SDX_14") (pintype "bidirectional"))
    )
    (net (code "202") (name "SMC_I2C1_SCL") (class "Default")
      (node (ref "J1") (pin "A5") (pinfunction "5_A5") (pintype "bidirectional"))
      (node (ref "R39") (pin "2") (pinfunction "2_2") (pintype "bidirectional"))
      (node (ref "U2") (pin "U17") (pinfunction "GPIO41_U17") (pintype "bidirectional"))
    )
    (net (code "203") (name "SMC_I2C1_SDA") (class "Default")
      (node (ref "J1") (pin "A4") (pinfunction "4_A4") (pintype "bidirectional"))
      (node (ref "R38") (pin "2") (pinfunction "2_2") (pintype "bidirectional"))
      (node (ref "U2") (pin "V17") (pinfunction "GPIO40_V17") (pintype "bidirectional"))
    )
    (net (code "204") (name "SMC_MCAN_RX") (class "Default")
      (node (ref "U14") (pin "4") (pinfunction "RXD_4") (pintype "output"))
      (node (ref "U2") (pin "B2") (pinfunction "GPIO10_B2") (pintype "bidirectional"))
    )
    (net (code "205") (name "SMC_MCAN_STB") (class "Default")
      (node (ref "R40") (pin "1") (pinfunction "1_1") (pintype "bidirectional"))
      (node (ref "U14") (pin "8") (pinfunction "STB_8") (pintype "input"))
      (node (ref "U2") (pin "G3") (pinfunction "GPIO9_G3") (pintype "bidirectional"))
    )
    (net (code "206") (name "SMC_MCAN_TX") (class "Default")
      (node (ref "U14") (pin "1") (pinfunction "TXD_1") (pintype "input"))
      (node (ref "U2") (pin "G2") (pinfunction "GPIO8_G2") (pintype "bidirectional"))
    )
    (net (code "207") (name "SMC_NAND_MISO") (class "Default")
      (node (ref "U16") (pin "2") (pinfunction "SO/SO1_2") (pintype "bidirectional"))
      (node (ref "U2") (pin "E2") (pinfunction "GPIO17_E2") (pintype "bidirectional"))
    )
    (net (code "208") (name "SMC_NAND_MOSI") (class "Default")
      (node (ref "U16") (pin "5") (pinfunction "SI/SO0_5") (pintype "bidirectional"))
      (node (ref "U2") (pin "E1") (pinfunction "GPIO16_E1") (pintype "bidirectional"))
    )
    (net (code "209") (name "SMC_NAND_SCK") (class "Default")
      (node (ref "U16") (pin "6") (pinfunction "SCK_6") (pintype "bidirectional"))
      (node (ref "U2") (pin "E3") (pinfunction "GPIO18_E3") (pintype "bidirectional"))
    )
    (net (code "210") (name "SMC_TCK") (class "Default")
      (node (ref "U2") (pin "V15") (pinfunction "TCK_V15") (pintype "input"))
      (node (ref "X4") (pin "4") (pinfunction "KL_4") (pintype "passive"))
    )
    (net (code "211") (name "SMC_TDI") (class "Default")
      (node (ref "U2") (pin "W13") (pinfunction "TDI_W13") (pintype "input"))
      (node (ref "X4") (pin "8") (pinfunction "KL_8") (pintype "passive"))
    )
    (net (code "212") (name "SMC_TDO") (class "Default")
      (node (ref "U2") (pin "W15") (pinfunction "TDO_W15") (pintype "output"))
      (node (ref "X4") (pin "6") (pinfunction "KL_6") (pintype "passive"))
    )
    (net (code "213") (name "SMC_TMS") (class "Default")
      (node (ref "R12") (pin "2") (pinfunction "2_2") (pintype "bidirectional"))
      (node (ref "U2") (pin "W14") (pinfunction "TMS_W14") (pintype "input"))
      (node (ref "X4") (pin "2") (pinfunction "KL_2") (pintype "passive"))
    )
    (net (code "214") (name "SMC_UART0_RX") (class "Default")
      (node (ref "J1") (pin "C2") (pinfunction "2_C2") (pintype "bidirectional"))
      (node (ref "JP9") (pin "3") (pinfunction "3_3") (pintype "passive"))
      (node (ref "U2") (pin "C19") (pinfunction "GPIO43_C19") (pintype "bidirectional"))
    )
    (net (code "215") (name "SMC_UART0_TX") (class "Default")
      (node (ref "J1") (pin "C1") (pinfunction "1_C1") (pintype "bidirectional"))
      (node (ref "JP9") (pin "2") (pinfunction "2_2") (pintype "passive"))
      (node (ref "U2") (pin "D19") (pinfunction "GPIO42_D19") (pintype "bidirectional"))
    )
    (net (code "216") (name "TPS53513_FB") (class "Default")
      (node (ref "R73") (pin "2") (pinfunction "2_2") (pintype "bidirectional"))
      (node (ref "R74") (pin "1") (pinfunction "1_1") (pintype "bidirectional"))
      (node (ref "U19") (pin "23") (pinfunction "FB_23") (pintype "passive"))
    )
    (net (code "217") (name "TPS53513_VREG") (class "Default")
      (node (ref "C206") (pin "1") (pinfunction "1_1") (pintype "bidirectional"))
      (node (ref "R69") (pin "1") (pinfunction "1_1") (pintype "bidirectional"))
      (node (ref "R76") (pin "1") (pinfunction "1_1") (pintype "bidirectional"))
      (node (ref "U19") (pin "20") (pinfunction "VREG_20") (pintype "passive"))
    )
    (net (code "218") (name "TRX1_SW") (class "Default")
      (node (ref "C22") (pin "2") (pinfunction "2_2") (pintype "bidirectional"))
      (node (ref "L3") (pin "2") (pinfunction "2_2") (pintype "passive"))
      (node (ref "U1") (pin "18") (pinfunction "TRX_SW_18") (pintype "passive"))
    )
    (net (code "219") (name "TRX2_SW") (class "Default")
      (node (ref "C259") (pin "2") (pinfunction "2_2") (pintype "bidirectional"))
      (node (ref "L16") (pin "2") (pinfunction "2_2") (pintype "passive"))
      (node (ref "U20") (pin "18") (pinfunction "TRX_SW_18") (pintype "passive"))
    )
    (net (code "220") (name "VCC_3V3_IO") (class "Default")
      (node (ref "C1") (pin "1") (pinfunction "1_1") (pintype "bidirectional"))
      (node (ref "C10") (pin "1") (pinfunction "1_1") (pintype "bidirectional"))
      (node (ref "C11") (pin "1") (pinfunction "1_1") (pintype "bidirectional"))
      (node (ref "C12") (pin "1") (pinfunction "1_1") (pintype "bidirectional"))
      (node (ref "C120") (pin "1") (pinfunction "1_1") (pintype "bidirectional"))
      (node (ref "C121") (pin "1") (pinfunction "1_1") (pintype "bidirectional"))
      (node (ref "C122") (pin "1") (pinfunction "1_1") (pintype "bidirectional"))
      (node (ref "C123") (pin "1") (pinfunction "1_1") (pintype "bidirectional"))
      (node (ref "C124") (pin "1") (pinfunction "1_1") (pintype "bidirectional"))
      (node (ref "C125") (pin "1") (pinfunction "1_1") (pintype "bidirectional"))
      (node (ref "C126") (pin "1") (pinfunction "1_1") (pintype "bidirectional"))
      (node (ref "C127") (pin "1") (pinfunction "1_1") (pintype "bidirectional"))
      (node (ref "C128") (pin "1") (pinfunction "1_1") (pintype "bidirectional"))
      (node (ref "C129") (pin "1") (pinfunction "1_1") (pintype "bidirectional"))
      (node (ref "C13") (pin "1") (pinfunction "1_1") (pintype "bidirectional"))
      (node (ref "C130") (pin "1") (pinfunction "1_1") (pintype "bidirectional"))
      (node (ref "C131") (pin "1") (pinfunction "1_1") (pintype "bidirectional"))
      (node (ref "C132") (pin "1") (pinfunction "1_1") (pintype "bidirectional"))
      (node (ref "C133") (pin "1") (pinfunction "1_1") (pintype "bidirectional"))
      (node (ref "C134") (pin "1") (pinfunction "1_1") (pintype "bidirectional"))
      (node (ref "C135") (pin "1") (pinfunction "1_1") (pintype "bidirectional"))
      (node (ref "C136") (pin "1") (pinfunction "1_1") (pintype "bidirectional"))
      (node (ref "C137") (pin "1") (pinfunction "1_1") (pintype "bidirectional"))
      (node (ref "C138") (pin "1") (pinfunction "1_1") (pintype "bidirectional"))
      (node (ref "C139") (pin "1") (pinfunction "1_1") (pintype "bidirectional"))
      (node (ref "C14") (pin "1") (pinfunction "1_1") (pintype "bidirectional"))
      (node (ref "C140") (pin "1") (pinfunction "1_1") (pintype "bidirectional"))
      (node (ref "C141") (pin "1") (pinfunction "1_1") (pintype "bidirectional"))
      (node (ref "C142") (pin "1") (pinfunction "1_1") (pintype "bidirectional"))
      (node (ref "C143") (pin "1") (pinfunction "1_1") (pintype "bidirectional"))
      (node (ref "C15") (pin "1") (pinfunction "1_1") (pintype "bidirectional"))
      (node (ref "C150") (pin "1") (pinfunction "1_1") (pintype "bidirectional"))
      (node (ref "C16") (pin "1") (pinfunction "1_1") (pintype "bidirectional"))
      (node (ref "C163") (pin "1") (pinfunction "1_1") (pintype "bidirectional"))
      (node (ref "C166") (pin "1") (pinfunction "1_1") (pintype "bidirectional"))
      (node (ref "C167") (pin "1") (pinfunction "1_1") (pintype "bidirectional"))
      (node (ref "C17") (pin "1") (pinfunction "1_1") (pintype "bidirectional"))
      (node (ref "C170") (pin "1") (pinfunction "1_1") (pintype "bidirectional"))
      (node (ref "C171") (pin "1") (pinfunction "1_1") (pintype "bidirectional"))
      (node (ref "C172") (pin "1") (pinfunction "1_1") (pintype "bidirectional"))
      (node (ref "C175") (pin "1") (pinfunction "1_1") (pintype "bidirectional"))
      (node (ref "C176") (pin "1") (pinfunction "1_1") (pintype "bidirectional"))
      (node (ref "C177") (pin "1") (pinfunction "1_1") (pintype "bidirectional"))
      (node (ref "C178") (pin "1") (pinfunction "1_1") (pintype "bidirectional"))
      (node (ref "C179") (pin "1") (pinfunction "1_1") (pintype "bidirectional"))
      (node (ref "C18") (pin "1") (pinfunction "1_1") (pintype "bidirectional"))
      (node (ref "C180") (pin "1") (pinfunction "1_1") (pintype "bidirectional"))
      (node (ref "C181") (pin "1") (pinfunction "1_1") (pintype "bidirectional"))
      (node (ref "C182") (pin "1") (pinfunction "1_1") (pintype "bidirectional"))
      (node (ref "C183") (pin "1") (pinfunction "1_1") (pintype "bidirectional"))
      (node (ref "C185") (pin "1") (pinfunction "1_1") (pintype "bidirectional"))
      (node (ref "C186") (pin "1") (pinfunction "1_1") (pintype "bidirectional"))
      (node (ref "C187") (pin "1") (pinfunction "1_1") (pintype "bidirectional"))
      (node (ref "C188") (pin "1") (pinfunction "1_1") (pintype "bidirectional"))
      (node (ref "C19") (pin "1") (pinfunction "1_1") (pintype "bidirectional"))
      (node (ref "C190") (pin "1") (pinfunction "1_1") (pintype "bidirectional"))
      (node (ref "C191") (pin "1") (pinfunction "1_1") (pintype "bidirectional"))
      (node (ref "C195") (pin "1") (pinfunction "1_1") (pintype "bidirectional"))
      (node (ref "C208") (pin "1") (pinfunction "1_1") (pintype "bidirectional"))
      (node (ref "C209") (pin "1") (pinfunction "1_1") (pintype "bidirectional"))
      (node (ref "C210") (pin "1") (pinfunction "1_1") (pintype "bidirectional"))
      (node (ref "C211") (pin "1") (pinfunction "1_1") (pintype "bidirectional"))
      (node (ref "C212") (pin "1") (pinfunction "1_1") (pintype "bidirectional"))
      (node (ref "C221") (pin "1") (pinfunction "1_1") (pintype "bidirectional"))
      (node (ref "C222") (pin "1") (pinfunction "1_1") (pintype "bidirectional"))
      (node (ref "C223") (pin "1") (pinfunction "1_1") (pintype "bidirectional"))
      (node (ref "C224") (pin "1") (pinfunction "1_1") (pintype "bidirectional"))
      (node (ref "C225") (pin "1") (pinfunction "1_1") (pintype "bidirectional"))
      (node (ref "C226") (pin "1") (pinfunction "1_1") (pintype "bidirectional"))
      (node (ref "C227") (pin "1") (pinfunction "1_1") (pintype "bidirectional"))
      (node (ref "C228") (pin "1") (pinfunction "1_1") (pintype "bidirectional"))
      (node (ref "C229") (pin "1") (pinfunction "1_1") (pintype "bidirectional"))
      (node (ref "C230") (pin "1") (pinfunction "1_1") (pintype "bidirectional"))
      (node (ref "C231") (pin "1") (pinfunction "1_1") (pintype "bidirectional"))
      (node (ref "C232") (pin "1") (pinfunction "1_1") (pintype "bidirectional"))
      (node (ref "C233") (pin "1") (pinfunction "1_1") (pintype "bidirectional"))
      (node (ref "C234") (pin "1") (pinfunction "1_1") (pintype "bidirectional"))
      (node (ref "C236") (pin "1") (pinfunction "1_1") (pintype "bidirectional"))
      (node (ref "C238") (pin "1") (pinfunction "1_1") (pintype "bidirectional"))
      (node (ref "C246") (pin "1") (pinfunction "1_1") (pintype "bidirectional"))
      (node (ref "C247") (pin "1") (pinfunction "1_1") (pintype "bidirectional"))
      (node (ref "C248") (pin "1") (pinfunction "1_1") (pintype "bidirectional"))
      (node (ref "C249") (pin "1") (pinfunction "1_1") (pintype "bidirectional"))
      (node (ref "C250") (pin "1") (pinfunction "1_1") (pintype "bidirectional"))
      (node (ref "C251") (pin "1") (pinfunction "1_1") (pintype "bidirectional"))
      (node (ref "C252") (pin "1") (pinfunction "1_1") (pintype "bidirectional"))
      (node (ref "C253") (pin "1") (pinfunction "1_1") (pintype "bidirectional"))
      (node (ref "C254") (pin "1") (pinfunction "1_1") (pintype "bidirectional"))
      (node (ref "C255") (pin "1") (pinfunction "1_1") (pintype "bidirectional"))
      (node (ref "C256") (pin "1") (pinfunction "1_1") (pintype "bidirectional"))
      (node (ref "C264") (pin "1") (pinfunction "1_1") (pintype "bidirectional"))
      (node (ref "C265") (pin "1") (pinfunction "1_1") (pintype "bidirectional"))
      (node (ref "C27") (pin "1") (pinfunction "1_1") (pintype "bidirectional"))
      (node (ref "C28") (pin "1") (pinfunction "1_1") (pintype "bidirectional"))
      (node (ref "C29") (pin "1") (pinfunction "1_1") (pintype "bidirectional"))
      (node (ref "C31") (pin "1") (pinfunction "1_1") (pintype "bidirectional"))
      (node (ref "C33") (pin "1") (pinfunction "1_1") (pintype "bidirectional"))
      (node (ref "C34") (pin "1") (pinfunction "1_1") (pintype "bidirectional"))
      (node (ref "C35") (pin "1") (pinfunction "1_1") (pintype "bidirectional"))
      (node (ref "C36") (pin "1") (pinfunction "1_1") (pintype "bidirectional"))
      (node (ref "C37") (pin "1") (pinfunction "1_1") (pintype "bidirectional"))
      (node (ref "C38") (pin "1") (pinfunction "1_1") (pintype "bidirectional"))
      (node (ref "C39") (pin "1") (pinfunction "1_1") (pintype "bidirectional"))
      (node (ref "C40") (pin "1") (pinfunction "1_1") (pintype "bidirectional"))
      (node (ref "C41") (pin "1") (pinfunction "1_1") (pintype "bidirectional"))
      (node (ref "C42") (pin "1") (pinfunction "1_1") (pintype "bidirectional"))
      (node (ref "C43") (pin "1") (pinfunction "1_1") (pintype "bidirectional"))
      (node (ref "C44") (pin "1") (pinfunction "1_1") (pintype "bidirectional"))
      (node (ref "C45") (pin "1") (pinfunction "1_1") (pintype "bidirectional"))
      (node (ref "C46") (pin "1") (pinfunction "1_1") (pintype "bidirectional"))
      (node (ref "C47") (pin "1") (pinfunction "1_1") (pintype "bidirectional"))
      (node (ref "C48") (pin "1") (pinfunction "1_1") (pintype "bidirectional"))
      (node (ref "C57") (pin "1") (pinfunction "1_1") (pintype "bidirectional"))
      (node (ref "C58") (pin "1") (pinfunction "1_1") (pintype "bidirectional"))
      (node (ref "C59") (pin "1") (pinfunction "1_1") (pintype "bidirectional"))
      (node (ref "C60") (pin "1") (pinfunction "1_1") (pintype "bidirectional"))
      (node (ref "C61") (pin "1") (pinfunction "1_1") (pintype "bidirectional"))
      (node (ref "C62") (pin "1") (pinfunction "1_1") (pintype "bidirectional"))
      (node (ref "C63") (pin "1") (pinfunction "1_1") (pintype "bidirectional"))
      (node (ref "C64") (pin "1") (pinfunction "1_1") (pintype "bidirectional"))
      (node (ref "C65") (pin "1") (pinfunction "1_1") (pintype "bidirectional"))
      (node (ref "C66") (pin "1") (pinfunction "1_1") (pintype "bidirectional"))
      (node (ref "C67") (pin "1") (pinfunction "1_1") (pintype "bidirectional"))
      (node (ref "C68") (pin "1") (pinfunction "1_1") (pintype "bidirectional"))
      (node (ref "C69") (pin "1") (pinfunction "1_1") (pintype "bidirectional"))
      (node (ref "C70") (pin "1") (pinfunction "1_1") (pintype "bidirectional"))
      (node (ref "C71") (pin "1") (pinfunction "1_1") (pintype "bidirectional"))
      (node (ref "C72") (pin "1") (pinfunction "1_1") (pintype "bidirectional"))
      (node (ref "C73") (pin "1") (pinfunction "1_1") (pintype "bidirectional"))
      (node (ref "C74") (pin "1") (pinfunction "1_1") (pintype "bidirectional"))
      (node (ref "C75") (pin "1") (pinfunction "1_1") (pintype "bidirectional"))
      (node (ref "C76") (pin "1") (pinfunction "1_1") (pintype "bidirectional"))
      (node (ref "C77") (pin "1") (pinfunction "1_1") (pintype "bidirectional"))
      (node (ref "C78") (pin "1") (pinfunction "1_1") (pintype "bidirectional"))
      (node (ref "C79") (pin "1") (pinfunction "1_1") (pintype "bidirectional"))
      (node (ref "C80") (pin "1") (pinfunction "1_1") (pintype "bidirectional"))
      (node (ref "C81") (pin "1") (pinfunction "1_1") (pintype "bidirectional"))
      (node (ref "C82") (pin "1") (pinfunction "1_1") (pintype "bidirectional"))
      (node (ref "C83") (pin "1") (pinfunction "1_1") (pintype "bidirectional"))
      (node (ref "C84") (pin "1") (pinfunction "1_1") (pintype "bidirectional"))
      (node (ref "C85") (pin "1") (pinfunction "1_1") (pintype "bidirectional"))
      (node (ref "C86") (pin "1") (pinfunction "1_1") (pintype "bidirectional"))
      (node (ref "C87") (pin "1") (pinfunction "1_1") (pintype "bidirectional"))
      (node (ref "C88") (pin "1") (pinfunction "1_1") (pintype "bidirectional"))
      (node (ref "C89") (pin "1") (pinfunction "1_1") (pintype "bidirectional"))
      (node (ref "C9") (pin "1") (pinfunction "1_1") (pintype "bidirectional"))
      (node (ref "C90") (pin "1") (pinfunction "1_1") (pintype "bidirectional"))
      (node (ref "C91") (pin "1") (pinfunction "1_1") (pintype "bidirectional"))
      (node (ref "C92") (pin "1") (pinfunction "1_1") (pintype "bidirectional"))
      (node (ref "C93") (pin "1") (pinfunction "1_1") (pintype "bidirectional"))
      (node (ref "C94") (pin "1") (pinfunction "1_1") (pintype "bidirectional"))
      (node (ref "C95") (pin "1") (pinfunction "1_1") (pintype "bidirectional"))
      (node (ref "C96") (pin "1") (pinfunction "1_1") (pintype "bidirectional"))
      (node (ref "C97") (pin "1") (pinfunction "1_1") (pintype "bidirectional"))
      (node (ref "IC1") (pin "15") (pinfunction "VCCINT_3.3V_1_15") (pintype "power_in"))
      (node (ref "IC1") (pin "26") (pinfunction "VCCIO_2.5V/3.3V_26") (pintype "power_in"))
      (node (ref "IC1") (pin "35") (pinfunction "VCCINT_3.3V_2_35") (pintype "power_in"))
      (node (ref "J1") (pin "B3") (pinfunction "3_B3") (pintype "bidirectional"))
      (node (ref "J1") (pin "B4") (pinfunction "4_B4") (pintype "bidirectional"))
      (node (ref "JP1") (pin "1") (pinfunction "1_1") (pintype "passive"))
      (node (ref "JP10") (pin "1") (pinfunction "1_1") (pintype "passive"))
      (node (ref "JP11") (pin "1") (pinfunction "1_1") (pintype "passive"))
      (node (ref "JP2") (pin "1") (pinfunction "1_1") (pintype "passive"))
      (node (ref "JP3") (pin "1") (pinfunction "1_1") (pintype "passive"))
      (node (ref "JP4") (pin "1") (pinfunction "1_1") (pintype "passive"))
      (node (ref "JP9") (pin "1") (pinfunction "1_1") (pintype "passive"))
      (node (ref "L12") (pin "2") (pinfunction "P$2_2") (pintype "bidirectional"))
      (node (ref "R11") (pin "1") (pinfunction "1_1") (pintype "bidirectional"))
      (node (ref "R12") (pin "1") (pinfunction "1_1") (pintype "bidirectional"))
      (node (ref "R13") (pin "1") (pinfunction "1_1") (pintype "bidirectional"))
      (node (ref "R14") (pin "1") (pinfunction "1_1") (pintype "bidirectional"))
      (node (ref "R2") (pin "1") (pinfunction "1_1") (pintype "bidirectional"))
      (node (ref "R21") (pin "1") (pinfunction "1_1") (pintype "bidirectional"))
      (node (ref "R22") (pin "1") (pinfunction "1_1") (pintype "bidirectional"))
      (node (ref "R30") (pin "1") (pinfunction "1_1") (pintype "bidirectional"))
      (node (ref "R32") (pin "1") (pinfunction "1_1") (pintype "bidirectional"))
      (node (ref "R34") (pin "1") (pinfunction "1_1") (pintype "bidirectional"))
      (node (ref "R35") (pin "1") (pinfunction "1_1") (pintype "bidirectional"))
      (node (ref "R36") (pin "1") (pinfunction "1_1") (pintype "bidirectional"))
      (node (ref "R37") (pin "1") (pinfunction "1_1") (pintype "bidirectional"))
      (node (ref "R38") (pin "1") (pinfunction "1_1") (pintype "bidirectional"))
      (node (ref "R39") (pin "1") (pinfunction "1_1") (pintype "bidirectional"))
      (node (ref "R4") (pin "1") (pinfunction "1_1") (pintype "bidirectional"))
      (node (ref "R42") (pin "1") (pinfunction "1_1") (pintype "bidirectional"))
      (node (ref "R44") (pin "1") (pinfunction "1_1") (pintype "bidirectional"))
      (node (ref "R46") (pin "1") (pinfunction "1_1") (pintype "bidirectional"))
      (node (ref "R48") (pin "1") (pinfunction "1_1") (pintype "bidirectional"))
      (node (ref "R50") (pin "1") (pinfunction "1_1") (pintype "bidirectional"))
      (node (ref "R53") (pin "1") (pinfunction "1_1") (pintype "bidirectional"))
      (node (ref "R54") (pin "1") (pinfunction "1_1") (pintype "bidirectional"))
      (node (ref "R57") (pin "1") (pinfunction "1_1") (pintype "bidirectional"))
      (node (ref "R58") (pin "1") (pinfunction "1_1") (pintype "bidirectional"))
      (node (ref "R6") (pin "1") (pinfunction "1_1") (pintype "bidirectional"))
      (node (ref "R61") (pin "1") (pinfunction "1_1") (pintype "bidirectional"))
      (node (ref "R62") (pin "1") (pinfunction "1_1") (pintype "bidirectional"))
      (node (ref "R63") (pin "1") (pinfunction "1_1") (pintype "bidirectional"))
      (node (ref "R64") (pin "1") (pinfunction "1_1") (pintype "bidirectional"))
      (node (ref "R67") (pin "1") (pinfunction "1_1") (pintype "bidirectional"))
      (node (ref "R68") (pin "1") (pinfunction "1_1") (pintype "bidirectional"))
      (node (ref "R7") (pin "1") (pinfunction "1_1") (pintype "bidirectional"))
      (node (ref "R73") (pin "1") (pinfunction "1_1") (pintype "bidirectional"))
      (node (ref "R78") (pin "1") (pinfunction "1_1") (pintype "bidirectional"))
      (node (ref "R79") (pin "1") (pinfunction "1_1") (pintype "bidirectional"))
      (node (ref "R8") (pin "1") (pinfunction "1_1") (pintype "bidirectional"))
      (node (ref "R80") (pin "1") (pinfunction "1_1") (pintype "bidirectional"))
      (node (ref "R82") (pin "1") (pinfunction "1_1") (pintype "bidirectional"))
      (node (ref "R83") (pin "1") (pinfunction "1_1") (pintype "bidirectional"))
      (node (ref "R84") (pin "1") (pinfunction "1_1") (pintype "bidirectional"))
      (node (ref "R86") (pin "1") (pinfunction "1_1") (pintype "bidirectional"))
      (node (ref "R87") (pin "1") (pinfunction "1_1") (pintype "bidirectional"))
      (node (ref "R89") (pin "1") (pinfunction "1_1") (pintype "bidirectional"))
      (node (ref "R92") (pin "1") (pinfunction "1_1") (pintype "bidirectional"))
      (node (ref "R95") (pin "1") (pinfunction "1_1") (pintype "bidirectional"))
      (node (ref "R96") (pin "1") (pinfunction "1_1") (pintype "bidirectional"))
      (node (ref "U1") (pin "1") (pinfunction "VDD_GUARD_1") (pintype "power_in"))
      (node (ref "U1") (pin "12") (pinfunction "DVDD_12") (pintype "power_in"))
      (node (ref "U1") (pin "13") (pinfunction "AVDD_IF_13") (pintype "power_in"))
      (node (ref "U1") (pin "15") (pinfunction "AVDD_RF_15") (pintype "power_in"))
      (node (ref "U1") (pin "22") (pinfunction "AVDD_SYNTH1_22") (pintype "power_in"))
      (node (ref "U1") (pin "25") (pinfunction "AVDD_PFD_CHP_25") (pintype "power_in"))
      (node (ref "U1") (pin "27") (pinfunction "AVDD_SYNTH2_27") (pintype "power_in"))
      (node (ref "U1") (pin "28") (pinfunction "AVDD_XOSC_28") (pintype "power_in"))
      (node (ref "U1") (pin "5") (pinfunction "DVDD_2_5") (pintype "power_in"))
      (node (ref "U12") (pin "6") (pinfunction "VS_6") (pintype "power_in"))
      (node (ref "U13") (pin "2") (pinfunction "A0_2") (pintype "passive"))
      (node (ref "U13") (pin "6") (pinfunction "VS_6") (pintype "power_in"))
      (node (ref "U14") (pin "5") (pinfunction "VIO_5") (pintype "power_in"))
      (node (ref "U15") (pin "8") (pinfunction "VCC_8") (pintype "bidirectional"))
      (node (ref "U16") (pin "8") (pinfunction "VCC_8") (pintype "bidirectional"))
      (node (ref "U17") (pin "9") (pinfunction "VCC_9") (pintype "bidirectional"))
      (node (ref "U18") (pin "6") (pinfunction "VS_6") (pintype "power_in"))
      (node (ref "U19") (pin "24") (pinfunction "VO_24") (pintype "passive"))
      (node (ref "U2") (pin "A18") (pinfunction "VDDIO_3_A18") (pintype "power_in"))
      (node (ref "U2") (pin "A9") (pinfunction "VDDIO_2_A9") (pintype "power_in"))
      (node (ref "U2") (pin "B1") (pinfunction "VDDIO_4_B1") (pintype "power_in"))
      (node (ref "U2") (pin "E10") (pinfunction "VDDIO_6_E10") (pintype "power_in"))
      (node (ref "U2") (pin "E13") (pinfunction "VDDIO_7_E13") (pintype "power_in"))
      (node (ref "U2") (pin "E16") (pinfunction "VDDIO_8_E16") (pintype "power_in"))
      (node (ref "U2") (pin "E7") (pinfunction "VDDIO_5_E7") (pintype "power_in"))
      (node (ref "U2") (pin "F10") (pinfunction "VDDIO_11_F10") (pintype "power_in"))
      (node (ref "U2") (pin "F13") (pinfunction "VDDIO_12_F13") (pintype "power_in"))
      (node (ref "U2") (pin "F16") (pinfunction "VDDIO_13_F16") (pintype "power_in"))
      (node (ref "U2") (pin "F4") (pinfunction "VDDIO_9_F4") (pintype "power_in"))
      (node (ref "U2") (pin "F7") (pinfunction "VDDIO_10_F7") (pintype "power_in"))
      (node (ref "U2") (pin "G4") (pinfunction "VDDIO_14_G4") (pintype "power_in"))
      (node (ref "U2") (pin "G5") (pinfunction "VDDIO_15_G5") (pintype "power_in"))
      (node (ref "U2") (pin "G6") (pinfunction "VDDIO_16_G6") (pintype "power_in"))
      (node (ref "U2") (pin "H16") (pinfunction "VDDOSC_2_H16") (pintype "power_in"))
      (node (ref "U2") (pin "H17") (pinfunction "VDDOSC_H17") (pintype "power_in"))
      (node (ref "U2") (pin "H5") (pinfunction "VDDIO_17_H5") (pintype "power_in"))
      (node (ref "U2") (pin "H6") (pinfunction "VDDIO_18_H6") (pintype "power_in"))
      (node (ref "U2") (pin "L14") (pinfunction "VDDIO_19_L14") (pintype "power_in"))
      (node (ref "U2") (pin "L15") (pinfunction "VDDIO_20_L15") (pintype "power_in"))
      (node (ref "U2") (pin "M1") (pinfunction "VDDIO_21_M1") (pintype "power_in"))
      (node (ref "U2") (pin "M5") (pinfunction "VDDIO_22_M5") (pintype "power_in"))
      (node (ref "U2") (pin "M6") (pinfunction "VDDIO_23_M6") (pintype "power_in"))
      (node (ref "U2") (pin "N14") (pinfunction "VDDIO_24_N14") (pintype "power_in"))
      (node (ref "U2") (pin "N15") (pinfunction "VDDIO_25_N15") (pintype "power_in"))
      (node (ref "U2") (pin "P6") (pinfunction "VDDA_2_P6") (pintype "power_in"))
      (node (ref "U2") (pin "P9") (pinfunction "VDDIO_26_P9") (pintype "power_in"))
      (node (ref "U2") (pin "R1") (pinfunction "VREFHIC_R1") (pintype "passive"))
      (node (ref "U2") (pin "R11") (pinfunction "VDD3VFL_2_R11") (pintype "power_in"))
      (node (ref "U2") (pin "R12") (pinfunction "VDD3VFL_R12") (pintype "power_in"))
      (node (ref "U2") (pin "R6") (pinfunction "VDDA_R6") (pintype "power_in"))
      (node (ref "U2") (pin "R9") (pinfunction "VDDIO_27_R9") (pintype "power_in"))
      (node (ref "U2") (pin "V1") (pinfunction "VREFHIA_V1") (pintype "passive"))
      (node (ref "U2") (pin "V19") (pinfunction "VDDIO_28_V19") (pintype "power_in"))
      (node (ref "U2") (pin "V5") (pinfunction "VREFHID_V5") (pintype "passive"))
      (node (ref "U2") (pin "W5") (pinfunction "VREFHIB_W5") (pintype "passive"))
      (node (ref "U2") (pin "W8") (pinfunction "VDDIO_W8") (pintype "power_in"))
      (node (ref "U20") (pin "1") (pinfunction "VDD_GUARD_1") (pintype "power_in"))
      (node (ref "U20") (pin "12") (pinfunction "DVDD_12") (pintype "power_in"))
      (node (ref "U20") (pin "13") (pinfunction "AVDD_IF_13") (pintype "power_in"))
      (node (ref "U20") (pin "15") (pinfunction "AVDD_RF_15") (pintype "power_in"))
      (node (ref "U20") (pin "22") (pinfunction "AVDD_SYNTH1_22") (pintype "power_in"))
      (node (ref "U20") (pin "25") (pinfunction "AVDD_PFD_CHP_25") (pintype "power_in"))
      (node (ref "U20") (pin "27") (pinfunction "AVDD_SYNTH2_27") (pintype "power_in"))
      (node (ref "U20") (pin "28") (pinfunction "AVDD_XOSC_28") (pintype "power_in"))
      (node (ref "U20") (pin "5") (pinfunction "DVDD_2_5") (pintype "power_in"))
      (node (ref "U21") (pin "11") (pinfunction "VDD_2_11") (pintype "power_in"))
      (node (ref "U21") (pin "2") (pinfunction "VDDA_2") (pintype "power_in"))
      (node (ref "U21") (pin "26") (pinfunction "VDD_3_26") (pintype "power_in"))
      (node (ref "U21") (pin "42") (pinfunction "VDD_4_42") (pintype "power_in"))
      (node (ref "U21") (pin "54") (pinfunction "VDD_54") (pintype "power_in"))
      (node (ref "U22") (pin "5") (pinfunction "VIO_5") (pintype "power_in"))
      (node (ref "U23") (pin "5") (pinfunction "VCC_5") (pintype "power_in"))
      (node (ref "U24") (pin "8") (pinfunction "VCC_8") (pintype "bidirectional"))
      (node (ref "U3") (pin "11") (pinfunction "VDD_2_11") (pintype "power_in"))
      (node (ref "U3") (pin "2") (pinfunction "VDDA_2") (pintype "power_in"))
      (node (ref "U3") (pin "26") (pinfunction "VDD_3_26") (pintype "power_in"))
      (node (ref "U3") (pin "42") (pinfunction "VDD_4_42") (pintype "power_in"))
      (node (ref "U3") (pin "54") (pinfunction "VDD_54") (pintype "power_in"))
      (node (ref "U34") (pin "P$4") (pinfunction "VCC_P$4") (pintype "power_in"))
      (node (ref "U4") (pin "5") (pinfunction "VIO_5") (pintype "power_in"))
      (node (ref "U5") (pin "5") (pinfunction "VCC_5") (pintype "power_in"))
      (node (ref "U6") (pin "A7") (pinfunction "VDDQ_A7") (pintype "bidirectional"))
      (node (ref "U6") (pin "A9") (pinfunction "VDD_A9") (pintype "bidirectional"))
      (node (ref "U6") (pin "B3") (pinfunction "VDDQ_B3") (pintype "bidirectional"))
      (node (ref "U6") (pin "C7") (pinfunction "VDDQ_C7") (pintype "bidirectional"))
      (node (ref "U6") (pin "D3") (pinfunction "VDDQ_D3") (pintype "bidirectional"))
      (node (ref "U6") (pin "E7") (pinfunction "VDD_E7") (pintype "bidirectional"))
      (node (ref "U6") (pin "J9") (pinfunction "VDD_J9") (pintype "bidirectional"))
      (node (ref "U7") (pin "P$4") (pinfunction "VCC_P$4") (pintype "power_in"))
      (node (ref "U8") (pin "12") (pinfunction "CSB_12") (pintype "input"))
      (node (ref "U8") (pin "5") (pinfunction "VDDIO_5") (pintype "power_in"))
      (node (ref "U8") (pin "8") (pinfunction "VDD_8") (pintype "power_in"))
      (node (ref "U9") (pin "1") (pinfunction "SDO_1") (pintype "bidirectional"))
      (node (ref "U9") (pin "12") (pinfunction "CSB_12") (pintype "input"))
      (node (ref "U9") (pin "5") (pinfunction "VDDIO_5") (pintype "power_in"))
      (node (ref "U9") (pin "8") (pinfunction "VDD_8") (pintype "power_in"))
      (node (ref "X3") (pin "1") (pinfunction "KL_1") (pintype "passive"))
      (node (ref "X4") (pin "1") (pinfunction "KL_1") (pintype "passive"))
      (node (ref "X5") (pin "1") (pinfunction "KL_1") (pintype "passive"))
      (node (ref "X8") (pin "1") (pinfunction "KL_1") (pintype "passive"))
    )
    (net (code "221") (name "VCC_5V0") (class "Default")
      (node (ref "C168") (pin "1") (pinfunction "1_1") (pintype "bidirectional"))
      (node (ref "C169") (pin "1") (pinfunction "1_1") (pintype "bidirectional"))
      (node (ref "C173") (pin "1") (pinfunction "1_1") (pintype "bidirectional"))
      (node (ref "C174") (pin "1") (pinfunction "1_1") (pintype "bidirectional"))
      (node (ref "C196") (pin "1") (pinfunction "1_1") (pintype "bidirectional"))
      (node (ref "C197") (pin "1") (pinfunction "1_1") (pintype "bidirectional"))
      (node (ref "C199") (pin "1") (pinfunction "1_1") (pintype "bidirectional"))
      (node (ref "C2") (pin "1") (pinfunction "1_1") (pintype "bidirectional"))
      (node (ref "C200") (pin "1") (pinfunction "1_1") (pintype "bidirectional"))
      (node (ref "C201") (pin "1") (pinfunction "1_1") (pintype "bidirectional"))
      (node (ref "C202") (pin "1") (pinfunction "1_1") (pintype "bidirectional"))
      (node (ref "C203") (pin "1") (pinfunction "1_1") (pintype "bidirectional"))
      (node (ref "C204") (pin "1") (pinfunction "1_1") (pintype "bidirectional"))
      (node (ref "C205") (pin "1") (pinfunction "1_1") (pintype "bidirectional"))
      (node (ref "C239") (pin "1") (pinfunction "1_1") (pintype "bidirectional"))
      (node (ref "C267") (pin "2") (pinfunction "2_2") (pintype "bidirectional"))
      (node (ref "C268") (pin "1") (pinfunction "1_1") (pintype "bidirectional"))
      (node (ref "C269") (pin "1") (pinfunction "1_1") (pintype "bidirectional"))
      (node (ref "J1") (pin "B1") (pinfunction "1_B1") (pintype "bidirectional"))
      (node (ref "J1") (pin "B2") (pinfunction "2_B2") (pintype "bidirectional"))
      (node (ref "R29") (pin "1") (pinfunction "1_1") (pintype "bidirectional"))
      (node (ref "R31") (pin "1") (pinfunction "1_1") (pintype "bidirectional"))
      (node (ref "R66") (pin "2") (pinfunction "2_2") (pintype "bidirectional"))
      (node (ref "U12") (pin "10") (pinfunction "VIN+_10") (pintype "input"))
      (node (ref "U12") (pin "8") (pinfunction "VBUS_8") (pintype "input"))
      (node (ref "U13") (pin "10") (pinfunction "VIN+_10") (pintype "input"))
      (node (ref "U13") (pin "8") (pinfunction "VBUS_8") (pintype "input"))
      (node (ref "U14") (pin "3") (pinfunction "VCC_3") (pintype "power_in"))
      (node (ref "U18") (pin "9") (pinfunction "VIN-_9") (pintype "input"))
      (node (ref "U19") (pin "15") (pinfunction "VIN_2_15") (pintype "passive"))
      (node (ref "U19") (pin "16") (pinfunction "VIN_3_16") (pintype "passive"))
      (node (ref "U19") (pin "17") (pinfunction "VIN_17") (pintype "passive"))
      (node (ref "U19") (pin "19") (pinfunction "VDD_19") (pintype "power_in"))
      (node (ref "U19") (pin "3") (pinfunction "EN_3") (pintype "passive"))
      (node (ref "U22") (pin "3") (pinfunction "VCC_3") (pintype "power_in"))
      (node (ref "U4") (pin "3") (pinfunction "VCC_3") (pintype "power_in"))
    )
    (net (code "222") (name "VDD_CORE") (class "Default")
      (node (ref "C100") (pin "1") (pinfunction "1_1") (pintype "bidirectional"))
      (node (ref "C101") (pin "1") (pinfunction "1_1") (pintype "bidirectional"))
      (node (ref "C102") (pin "1") (pinfunction "1_1") (pintype "bidirectional"))
      (node (ref "C103") (pin "1") (pinfunction "1_1") (pintype "bidirectional"))
      (node (ref "C104") (pin "1") (pinfunction "1_1") (pintype "bidirectional"))
      (node (ref "C105") (pin "1") (pinfunction "1_1") (pintype "bidirectional"))
      (node (ref "C106") (pin "1") (pinfunction "1_1") (pintype "bidirectional"))
      (node (ref "C107") (pin "1") (pinfunction "1_1") (pintype "bidirectional"))
      (node (ref "C108") (pin "1") (pinfunction "1_1") (pintype "bidirectional"))
      (node (ref "C109") (pin "1") (pinfunction "1_1") (pintype "bidirectional"))
      (node (ref "C110") (pin "1") (pinfunction "1_1") (pintype "bidirectional"))
      (node (ref "C111") (pin "1") (pinfunction "1_1") (pintype "bidirectional"))
      (node (ref "C112") (pin "1") (pinfunction "1_1") (pintype "bidirectional"))
      (node (ref "C113") (pin "1") (pinfunction "1_1") (pintype "bidirectional"))
      (node (ref "C114") (pin "1") (pinfunction "1_1") (pintype "bidirectional"))
      (node (ref "C115") (pin "1") (pinfunction "1_1") (pintype "bidirectional"))
      (node (ref "C116") (pin "1") (pinfunction "1_1") (pintype "bidirectional"))
      (node (ref "C117") (pin "1") (pinfunction "1_1") (pintype "bidirectional"))
      (node (ref "C98") (pin "1") (pinfunction "1_1") (pintype "bidirectional"))
      (node (ref "C99") (pin "1") (pinfunction "1_1") (pintype "bidirectional"))
      (node (ref "R3") (pin "1") (pinfunction "1_1") (pintype "bidirectional"))
      (node (ref "U2") (pin "E11") (pinfunction "VDD_3_E11") (pintype "power_in"))
      (node (ref "U2") (pin "E9") (pinfunction "VDD_2_E9") (pintype "power_in"))
      (node (ref "U2") (pin "F11") (pinfunction "VDD_5_F11") (pintype "power_in"))
      (node (ref "U2") (pin "F9") (pinfunction "VDD_4_F9") (pintype "power_in"))
      (node (ref "U2") (pin "G14") (pinfunction "VDD_6_G14") (pintype "power_in"))
      (node (ref "U2") (pin "G15") (pinfunction "VDD_7_G15") (pintype "power_in"))
      (node (ref "U2") (pin "J14") (pinfunction "VDD_8_J14") (pintype "power_in"))
      (node (ref "U2") (pin "J15") (pinfunction "VDD_9_J15") (pintype "power_in"))
      (node (ref "U2") (pin "K5") (pinfunction "VDD_10_K5") (pintype "power_in"))
      (node (ref "U2") (pin "K6") (pinfunction "VDD_11_K6") (pintype "power_in"))
      (node (ref "U2") (pin "P10") (pinfunction "VDD_12_P10") (pintype "power_in"))
      (node (ref "U2") (pin "P13") (pinfunction "VDD_13_P13") (pintype "power_in"))
      (node (ref "U2") (pin "R10") (pinfunction "VDD_14_R10") (pintype "power_in"))
      (node (ref "U2") (pin "R13") (pinfunction "VDD_R13") (pintype "power_in"))
    )
    (net (code "223") (name "VINPUT") (class "Default")
      (node (ref "C198") (pin "1") (pinfunction "1_1") (pintype "bidirectional"))
      (node (ref "C267") (pin "1") (pinfunction "1_1") (pintype "bidirectional"))
      (node (ref "R66") (pin "1") (pinfunction "1_1") (pintype "bidirectional"))
      (node (ref "U18") (pin "10") (pinfunction "VIN+_10") (pintype "input"))
      (node (ref "U18") (pin "8") (pinfunction "VBUS_8") (pintype "input"))
      (node (ref "X6") (pin "2") (pinfunction "S_2") (pintype "passive"))
      (node (ref "X6") (pin "4") (pinfunction "S_4") (pintype "passive"))
    )
    (net (code "224") (name "VSS") (class "Default")
      (node (ref "C1") (pin "2") (pinfunction "2_2") (pintype "bidirectional"))
      (node (ref "C10") (pin "2") (pinfunction "2_2") (pintype "bidirectional"))
      (node (ref "C100") (pin "2") (pinfunction "2_2") (pintype "bidirectional"))
      (node (ref "C101") (pin "2") (pinfunction "2_2") (pintype "bidirectional"))
      (node (ref "C102") (pin "2") (pinfunction "2_2") (pintype "bidirectional"))
      (node (ref "C103") (pin "2") (pinfunction "2_2") (pintype "bidirectional"))
      (node (ref "C104") (pin "2") (pinfunction "2_2") (pintype "bidirectional"))
      (node (ref "C105") (pin "2") (pinfunction "2_2") (pintype "bidirectional"))
      (node (ref "C106") (pin "2") (pinfunction "2_2") (pintype "bidirectional"))
      (node (ref "C107") (pin "2") (pinfunction "2_2") (pintype "bidirectional"))
      (node (ref "C108") (pin "2") (pinfunction "2_2") (pintype "bidirectional"))
      (node (ref "C109") (pin "2") (pinfunction "2_2") (pintype "bidirectional"))
      (node (ref "C11") (pin "2") (pinfunction "2_2") (pintype "bidirectional"))
      (node (ref "C110") (pin "2") (pinfunction "2_2") (pintype "bidirectional"))
      (node (ref "C111") (pin "2") (pinfunction "2_2") (pintype "bidirectional"))
      (node (ref "C112") (pin "2") (pinfunction "2_2") (pintype "bidirectional"))
      (node (ref "C113") (pin "2") (pinfunction "2_2") (pintype "bidirectional"))
      (node (ref "C114") (pin "2") (pinfunction "2_2") (pintype "bidirectional"))
      (node (ref "C115") (pin "2") (pinfunction "2_2") (pintype "bidirectional"))
      (node (ref "C116") (pin "2") (pinfunction "2_2") (pintype "bidirectional"))
      (node (ref "C117") (pin "2") (pinfunction "2_2") (pintype "bidirectional"))
      (node (ref "C118") (pin "2") (pinfunction "2_2") (pintype "bidirectional"))
      (node (ref "C119") (pin "2") (pinfunction "2_2") (pintype "bidirectional"))
      (node (ref "C12") (pin "2") (pinfunction "2_2") (pintype "bidirectional"))
      (node (ref "C120") (pin "2") (pinfunction "2_2") (pintype "bidirectional"))
      (node (ref "C121") (pin "2") (pinfunction "2_2") (pintype "bidirectional"))
      (node (ref "C122") (pin "2") (pinfunction "2_2") (pintype "bidirectional"))
      (node (ref "C123") (pin "2") (pinfunction "2_2") (pintype "bidirectional"))
      (node (ref "C124") (pin "2") (pinfunction "2_2") (pintype "bidirectional"))
      (node (ref "C125") (pin "2") (pinfunction "2_2") (pintype "bidirectional"))
      (node (ref "C126") (pin "2") (pinfunction "2_2") (pintype "bidirectional"))
      (node (ref "C127") (pin "2") (pinfunction "2_2") (pintype "bidirectional"))
      (node (ref "C128") (pin "2") (pinfunction "2_2") (pintype "bidirectional"))
      (node (ref "C129") (pin "2") (pinfunction "2_2") (pintype "bidirectional"))
      (node (ref "C13") (pin "2") (pinfunction "2_2") (pintype "bidirectional"))
      (node (ref "C130") (pin "2") (pinfunction "2_2") (pintype "bidirectional"))
      (node (ref "C131") (pin "2") (pinfunction "2_2") (pintype "bidirectional"))
      (node (ref "C132") (pin "2") (pinfunction "2_2") (pintype "bidirectional"))
      (node (ref "C133") (pin "2") (pinfunction "2_2") (pintype "bidirectional"))
      (node (ref "C134") (pin "2") (pinfunction "2_2") (pintype "bidirectional"))
      (node (ref "C135") (pin "2") (pinfunction "2_2") (pintype "bidirectional"))
      (node (ref "C136") (pin "2") (pinfunction "2_2") (pintype "bidirectional"))
      (node (ref "C137") (pin "2") (pinfunction "2_2") (pintype "bidirectional"))
      (node (ref "C138") (pin "2") (pinfunction "2_2") (pintype "bidirectional"))
      (node (ref "C139") (pin "2") (pinfunction "2_2") (pintype "bidirectional"))
      (node (ref "C14") (pin "2") (pinfunction "2_2") (pintype "bidirectional"))
      (node (ref "C140") (pin "2") (pinfunction "2_2") (pintype "bidirectional"))
      (node (ref "C141") (pin "2") (pinfunction "2_2") (pintype "bidirectional"))
      (node (ref "C142") (pin "2") (pinfunction "2_2") (pintype "bidirectional"))
      (node (ref "C143") (pin "2") (pinfunction "2_2") (pintype "bidirectional"))
      (node (ref "C144") (pin "2") (pinfunction "2_2") (pintype "bidirectional"))
      (node (ref "C145") (pin "2") (pinfunction "2_2") (pintype "bidirectional"))
      (node (ref "C146") (pin "2") (pinfunction "2_2") (pintype "bidirectional"))
      (node (ref "C147") (pin "2") (pinfunction "2_2") (pintype "bidirectional"))
      (node (ref "C148") (pin "2") (pinfunction "2_2") (pintype "bidirectional"))
      (node (ref "C149") (pin "2") (pinfunction "2_2") (pintype "bidirectional"))
      (node (ref "C15") (pin "2") (pinfunction "2_2") (pintype "bidirectional"))
      (node (ref "C150") (pin "2") (pinfunction "2_2") (pintype "bidirectional"))
      (node (ref "C151") (pin "2") (pinfunction "2_2") (pintype "bidirectional"))
      (node (ref "C152") (pin "2") (pinfunction "2_2") (pintype "bidirectional"))
      (node (ref "C153") (pin "2") (pinfunction "2_2") (pintype "bidirectional"))
      (node (ref "C154") (pin "2") (pinfunction "2_2") (pintype "bidirectional"))
      (node (ref "C155") (pin "2") (pinfunction "2_2") (pintype "bidirectional"))
      (node (ref "C156") (pin "2") (pinfunction "2_2") (pintype "bidirectional"))
      (node (ref "C157") (pin "2") (pinfunction "2_2") (pintype "bidirectional"))
      (node (ref "C158") (pin "2") (pinfunction "2_2") (pintype "bidirectional"))
      (node (ref "C159") (pin "2") (pinfunction "2_2") (pintype "bidirectional"))
      (node (ref "C16") (pin "2") (pinfunction "2_2") (pintype "bidirectional"))
      (node (ref "C160") (pin "2") (pinfunction "2_2") (pintype "bidirectional"))
      (node (ref "C161") (pin "2") (pinfunction "2_2") (pintype "bidirectional"))
      (node (ref "C162") (pin "2") (pinfunction "2_2") (pintype "bidirectional"))
      (node (ref "C163") (pin "2") (pinfunction "2_2") (pintype "bidirectional"))
      (node (ref "C164") (pin "2") (pinfunction "2_2") (pintype "bidirectional"))
      (node (ref "C165") (pin "2") (pinfunction "2_2") (pintype "bidirectional"))
      (node (ref "C166") (pin "2") (pinfunction "2_2") (pintype "bidirectional"))
      (node (ref "C167") (pin "2") (pinfunction "2_2") (pintype "bidirectional"))
      (node (ref "C168") (pin "2") (pinfunction "2_2") (pintype "bidirectional"))
      (node (ref "C169") (pin "2") (pinfunction "2_2") (pintype "bidirectional"))
      (node (ref "C17") (pin "2") (pinfunction "2_2") (pintype "bidirectional"))
      (node (ref "C170") (pin "2") (pinfunction "2_2") (pintype "bidirectional"))
      (node (ref "C171") (pin "2") (pinfunction "2_2") (pintype "bidirectional"))
      (node (ref "C172") (pin "2") (pinfunction "2_2") (pintype "bidirectional"))
      (node (ref "C173") (pin "2") (pinfunction "2_2") (pintype "bidirectional"))
      (node (ref "C174") (pin "2") (pinfunction "2_2") (pintype "bidirectional"))
      (node (ref "C175") (pin "2") (pinfunction "2_2") (pintype "bidirectional"))
      (node (ref "C176") (pin "2") (pinfunction "2_2") (pintype "bidirectional"))
      (node (ref "C177") (pin "2") (pinfunction "2_2") (pintype "bidirectional"))
      (node (ref "C178") (pin "2") (pinfunction "2_2") (pintype "bidirectional"))
      (node (ref "C179") (pin "2") (pinfunction "2_2") (pintype "bidirectional"))
      (node (ref "C18") (pin "2") (pinfunction "2_2") (pintype "bidirectional"))
      (node (ref "C180") (pin "2") (pinfunction "2_2") (pintype "bidirectional"))
      (node (ref "C181") (pin "2") (pinfunction "2_2") (pintype "bidirectional"))
      (node (ref "C182") (pin "2") (pinfunction "2_2") (pintype "bidirectional"))
      (node (ref "C183") (pin "2") (pinfunction "2_2") (pintype "bidirectional"))
      (node (ref "C184") (pin "2") (pinfunction "2_2") (pintype "bidirectional"))
      (node (ref "C185") (pin "2") (pinfunction "2_2") (pintype "bidirectional"))
      (node (ref "C186") (pin "2") (pinfunction "2_2") (pintype "bidirectional"))
      (node (ref "C187") (pin "2") (pinfunction "2_2") (pintype "bidirectional"))
      (node (ref "C188") (pin "2") (pinfunction "2_2") (pintype "bidirectional"))
      (node (ref "C189") (pin "2") (pinfunction "2_2") (pintype "bidirectional"))
      (node (ref "C19") (pin "2") (pinfunction "2_2") (pintype "bidirectional"))
      (node (ref "C190") (pin "2") (pinfunction "2_2") (pintype "bidirectional"))
      (node (ref "C191") (pin "2") (pinfunction "2_2") (pintype "bidirectional"))
      (node (ref "C192") (pin "2") (pinfunction "2_2") (pintype "bidirectional"))
      (node (ref "C193") (pin "2") (pinfunction "2_2") (pintype "bidirectional"))
      (node (ref "C194") (pin "2") (pinfunction "2_2") (pintype "bidirectional"))
      (node (ref "C195") (pin "2") (pinfunction "2_2") (pintype "bidirectional"))
      (node (ref "C196") (pin "2") (pinfunction "2_2") (pintype "bidirectional"))
      (node (ref "C197") (pin "2") (pinfunction "2_2") (pintype "bidirectional"))
      (node (ref "C198") (pin "2") (pinfunction "2_2") (pintype "bidirectional"))
      (node (ref "C199") (pin "2") (pinfunction "2_2") (pintype "bidirectional"))
      (node (ref "C2") (pin "2") (pinfunction "2_2") (pintype "bidirectional"))
      (node (ref "C200") (pin "2") (pinfunction "2_2") (pintype "bidirectional"))
      (node (ref "C201") (pin "2") (pinfunction "2_2") (pintype "bidirectional"))
      (node (ref "C202") (pin "2") (pinfunction "2_2") (pintype "bidirectional"))
      (node (ref "C203") (pin "2") (pinfunction "2_2") (pintype "bidirectional"))
      (node (ref "C204") (pin "2") (pinfunction "2_2") (pintype "bidirectional"))
      (node (ref "C205") (pin "2") (pinfunction "2_2") (pintype "bidirectional"))
      (node (ref "C206") (pin "2") (pinfunction "2_2") (pintype "bidirectional"))
      (node (ref "C208") (pin "2") (pinfunction "2_2") (pintype "bidirectional"))
      (node (ref "C209") (pin "2") (pinfunction "2_2") (pintype "bidirectional"))
      (node (ref "C210") (pin "2") (pinfunction "2_2") (pintype "bidirectional"))
      (node (ref "C211") (pin "2") (pinfunction "2_2") (pintype "bidirectional"))
      (node (ref "C212") (pin "2") (pinfunction "2_2") (pintype "bidirectional"))
      (node (ref "C213") (pin "2") (pinfunction "2_2") (pintype "bidirectional"))
      (node (ref "C214") (pin "2") (pinfunction "2_2") (pintype "bidirectional"))
      (node (ref "C215") (pin "2") (pinfunction "2_2") (pintype "bidirectional"))
      (node (ref "C217") (pin "1") (pinfunction "1_1") (pintype "bidirectional"))
      (node (ref "C218") (pin "1") (pinfunction "1_1") (pintype "bidirectional"))
      (node (ref "C219") (pin "1") (pinfunction "1_1") (pintype "bidirectional"))
      (node (ref "C220") (pin "1") (pinfunction "1_1") (pintype "bidirectional"))
      (node (ref "C221") (pin "2") (pinfunction "2_2") (pintype "bidirectional"))
      (node (ref "C222") (pin "2") (pinfunction "2_2") (pintype "bidirectional"))
      (node (ref "C223") (pin "2") (pinfunction "2_2") (pintype "bidirectional"))
      (node (ref "C224") (pin "2") (pinfunction "2_2") (pintype "bidirectional"))
      (node (ref "C225") (pin "2") (pinfunction "2_2") (pintype "bidirectional"))
      (node (ref "C226") (pin "2") (pinfunction "2_2") (pintype "bidirectional"))
      (node (ref "C227") (pin "2") (pinfunction "2_2") (pintype "bidirectional"))
      (node (ref "C228") (pin "2") (pinfunction "2_2") (pintype "bidirectional"))
      (node (ref "C229") (pin "2") (pinfunction "2_2") (pintype "bidirectional"))
      (node (ref "C230") (pin "2") (pinfunction "2_2") (pintype "bidirectional"))
      (node (ref "C231") (pin "2") (pinfunction "2_2") (pintype "bidirectional"))
      (node (ref "C233") (pin "2") (pinfunction "2_2") (pintype "bidirectional"))
      (node (ref "C234") (pin "2") (pinfunction "2_2") (pintype "bidirectional"))
      (node (ref "C235") (pin "2") (pinfunction "2_2") (pintype "bidirectional"))
      (node (ref "C236") (pin "2") (pinfunction "2_2") (pintype "bidirectional"))
      (node (ref "C237") (pin "2") (pinfunction "2_2") (pintype "bidirectional"))
      (node (ref "C238") (pin "2") (pinfunction "2_2") (pintype "bidirectional"))
      (node (ref "C239") (pin "2") (pinfunction "2_2") (pintype "bidirectional"))
      (node (ref "C24") (pin "1") (pinfunction "1_1") (pintype "bidirectional"))
      (node (ref "C240") (pin "2") (pinfunction "2_2") (pintype "bidirectional"))
      (node (ref "C241") (pin "2") (pinfunction "2_2") (pintype "bidirectional"))
      (node (ref "C242") (pin "2") (pinfunction "2_2") (pintype "bidirectional"))
      (node (ref "C243") (pin "2") (pinfunction "2_2") (pintype "bidirectional"))
      (node (ref "C244") (pin "2") (pinfunction "2_2") (pintype "bidirectional"))
      (node (ref "C245") (pin "2") (pinfunction "2_2") (pintype "bidirectional"))
      (node (ref "C246") (pin "2") (pinfunction "2_2") (pintype "bidirectional"))
      (node (ref "C247") (pin "2") (pinfunction "2_2") (pintype "bidirectional"))
      (node (ref "C248") (pin "2") (pinfunction "2_2") (pintype "bidirectional"))
      (node (ref "C249") (pin "2") (pinfunction "2_2") (pintype "bidirectional"))
      (node (ref "C25") (pin "2") (pinfunction "2_2") (pintype "bidirectional"))
      (node (ref "C250") (pin "2") (pinfunction "2_2") (pintype "bidirectional"))
      (node (ref "C251") (pin "2") (pinfunction "2_2") (pintype "bidirectional"))
      (node (ref "C252") (pin "2") (pinfunction "2_2") (pintype "bidirectional"))
      (node (ref "C253") (pin "2") (pinfunction "2_2") (pintype "bidirectional"))
      (node (ref "C254") (pin "2") (pinfunction "2_2") (pintype "bidirectional"))
      (node (ref "C255") (pin "2") (pinfunction "2_2") (pintype "bidirectional"))
      (node (ref "C256") (pin "2") (pinfunction "2_2") (pintype "bidirectional"))
      (node (ref "C261") (pin "1") (pinfunction "1_1") (pintype "bidirectional"))
      (node (ref "C262") (pin "2") (pinfunction "2_2") (pintype "bidirectional"))
      (node (ref "C264") (pin "2") (pinfunction "2_2") (pintype "bidirectional"))
      (node (ref "C265") (pin "2") (pinfunction "2_2") (pintype "bidirectional"))
      (node (ref "C266") (pin "2") (pinfunction "2_2") (pintype "bidirectional"))
      (node (ref "C27") (pin "2") (pinfunction "2_2") (pintype "bidirectional"))
      (node (ref "C28") (pin "2") (pinfunction "2_2") (pintype "bidirectional"))
      (node (ref "C29") (pin "2") (pinfunction "2_2") (pintype "bidirectional"))
      (node (ref "C3") (pin "2") (pinfunction "2_2") (pintype "bidirectional"))
      (node (ref "C30") (pin "2") (pinfunction "2_2") (pintype "bidirectional"))
      (node (ref "C31") (pin "2") (pinfunction "2_2") (pintype "bidirectional"))
      (node (ref "C32") (pin "2") (pinfunction "2_2") (pintype "bidirectional"))
      (node (ref "C33") (pin "2") (pinfunction "2_2") (pintype "bidirectional"))
      (node (ref "C34") (pin "2") (pinfunction "2_2") (pintype "bidirectional"))
      (node (ref "C35") (pin "2") (pinfunction "2_2") (pintype "bidirectional"))
      (node (ref "C36") (pin "2") (pinfunction "2_2") (pintype "bidirectional"))
      (node (ref "C37") (pin "2") (pinfunction "2_2") (pintype "bidirectional"))
      (node (ref "C38") (pin "2") (pinfunction "2_2") (pintype "bidirectional"))
      (node (ref "C39") (pin "2") (pinfunction "2_2") (pintype "bidirectional"))
      (node (ref "C4") (pin "2") (pinfunction "2_2") (pintype "bidirectional"))
      (node (ref "C40") (pin "2") (pinfunction "2_2") (pintype "bidirectional"))
      (node (ref "C41") (pin "2") (pinfunction "2_2") (pintype "bidirectional"))
      (node (ref "C42") (pin "2") (pinfunction "2_2") (pintype "bidirectional"))
      (node (ref "C43") (pin "2") (pinfunction "2_2") (pintype "bidirectional"))
      (node (ref "C44") (pin "2") (pinfunction "2_2") (pintype "bidirectional"))
      (node (ref "C45") (pin "2") (pinfunction "2_2") (pintype "bidirectional"))
      (node (ref "C46") (pin "2") (pinfunction "2_2") (pintype "bidirectional"))
      (node (ref "C47") (pin "2") (pinfunction "2_2") (pintype "bidirectional"))
      (node (ref "C48") (pin "2") (pinfunction "2_2") (pintype "bidirectional"))
      (node (ref "C49") (pin "2") (pinfunction "2_2") (pintype "bidirectional"))
      (node (ref "C5") (pin "2") (pinfunction "2_2") (pintype "bidirectional"))
      (node (ref "C50") (pin "2") (pinfunction "2_2") (pintype "bidirectional"))
      (node (ref "C51") (pin "2") (pinfunction "2_2") (pintype "bidirectional"))
      (node (ref "C53") (pin "1") (pinfunction "1_1") (pintype "bidirectional"))
      (node (ref "C54") (pin "1") (pinfunction "1_1") (pintype "bidirectional"))
      (node (ref "C55") (pin "1") (pinfunction "1_1") (pintype "bidirectional"))
      (node (ref "C56") (pin "1") (pinfunction "1_1") (pintype "bidirectional"))
      (node (ref "C57") (pin "2") (pinfunction "2_2") (pintype "bidirectional"))
      (node (ref "C58") (pin "2") (pinfunction "2_2") (pintype "bidirectional"))
      (node (ref "C59") (pin "2") (pinfunction "2_2") (pintype "bidirectional"))
      (node (ref "C6") (pin "2") (pinfunction "2_2") (pintype "bidirectional"))
      (node (ref "C60") (pin "2") (pinfunction "2_2") (pintype "bidirectional"))
      (node (ref "C61") (pin "2") (pinfunction "2_2") (pintype "bidirectional"))
      (node (ref "C62") (pin "2") (pinfunction "2_2") (pintype "bidirectional"))
      (node (ref "C63") (pin "2") (pinfunction "2_2") (pintype "bidirectional"))
      (node (ref "C64") (pin "2") (pinfunction "2_2") (pintype "bidirectional"))
      (node (ref "C65") (pin "2") (pinfunction "2_2") (pintype "bidirectional"))
      (node (ref "C66") (pin "2") (pinfunction "2_2") (pintype "bidirectional"))
      (node (ref "C67") (pin "2") (pinfunction "2_2") (pintype "bidirectional"))
      (node (ref "C68") (pin "2") (pinfunction "2_2") (pintype "bidirectional"))
      (node (ref "C69") (pin "2") (pinfunction "2_2") (pintype "bidirectional"))
      (node (ref "C7") (pin "2") (pinfunction "2_2") (pintype "bidirectional"))
      (node (ref "C70") (pin "2") (pinfunction "2_2") (pintype "bidirectional"))
      (node (ref "C71") (pin "2") (pinfunction "2_2") (pintype "bidirectional"))
      (node (ref "C72") (pin "2") (pinfunction "2_2") (pintype "bidirectional"))
      (node (ref "C73") (pin "2") (pinfunction "2_2") (pintype "bidirectional"))
      (node (ref "C74") (pin "2") (pinfunction "2_2") (pintype "bidirectional"))
      (node (ref "C75") (pin "2") (pinfunction "2_2") (pintype "bidirectional"))
      (node (ref "C76") (pin "2") (pinfunction "2_2") (pintype "bidirectional"))
      (node (ref "C78") (pin "2") (pinfunction "2_2") (pintype "bidirectional"))
      (node (ref "C79") (pin "2") (pinfunction "2_2") (pintype "bidirectional"))
      (node (ref "C8") (pin "2") (pinfunction "2_2") (pintype "bidirectional"))
      (node (ref "C80") (pin "2") (pinfunction "2_2") (pintype "bidirectional"))
      (node (ref "C81") (pin "2") (pinfunction "2_2") (pintype "bidirectional"))
      (node (ref "C82") (pin "2") (pinfunction "2_2") (pintype "bidirectional"))
      (node (ref "C83") (pin "2") (pinfunction "2_2") (pintype "bidirectional"))
      (node (ref "C84") (pin "2") (pinfunction "2_2") (pintype "bidirectional"))
      (node (ref "C85") (pin "2") (pinfunction "2_2") (pintype "bidirectional"))
      (node (ref "C86") (pin "2") (pinfunction "2_2") (pintype "bidirectional"))
      (node (ref "C87") (pin "2") (pinfunction "2_2") (pintype "bidirectional"))
      (node (ref "C88") (pin "2") (pinfunction "2_2") (pintype "bidirectional"))
      (node (ref "C89") (pin "2") (pinfunction "2_2") (pintype "bidirectional"))
      (node (ref "C9") (pin "2") (pinfunction "2_2") (pintype "bidirectional"))
      (node (ref "C90") (pin "2") (pinfunction "2_2") (pintype "bidirectional"))
      (node (ref "C91") (pin "2") (pinfunction "2_2") (pintype "bidirectional"))
      (node (ref "C92") (pin "2") (pinfunction "2_2") (pintype "bidirectional"))
      (node (ref "C93") (pin "2") (pinfunction "2_2") (pintype "bidirectional"))
      (node (ref "C94") (pin "2") (pinfunction "2_2") (pintype "bidirectional"))
      (node (ref "C95") (pin "2") (pinfunction "2_2") (pintype "bidirectional"))
      (node (ref "C96") (pin "2") (pinfunction "2_2") (pintype "bidirectional"))
      (node (ref "C97") (pin "2") (pinfunction "2_2") (pintype "bidirectional"))
      (node (ref "C98") (pin "2") (pinfunction "2_2") (pintype "bidirectional"))
      (node (ref "C99") (pin "2") (pinfunction "2_2") (pintype "bidirectional"))
      (node (ref "IC1") (pin "17") (pinfunction "GND_2_17") (pintype "power_in"))
      (node (ref "IC1") (pin "25") (pinfunction "GND_3_25") (pintype "power_in"))
      (node (ref "IC1") (pin "4") (pinfunction "GND_1_4") (pintype "power_in"))
      (node (ref "J1") (pin "A3") (pinfunction "3_A3") (pintype "bidirectional"))
      (node (ref "J1") (pin "A6") (pinfunction "6_A6") (pintype "bidirectional"))
      (node (ref "J1") (pin "A9") (pinfunction "9_A9") (pintype "bidirectional"))
      (node (ref "J1") (pin "B10") (pinfunction "10_B10") (pintype "bidirectional"))
      (node (ref "J1") (pin "B5") (pinfunction "5_B5") (pintype "bidirectional"))
      (node (ref "J1") (pin "B6") (pinfunction "6_B6") (pintype "bidirectional"))
      (node (ref "J1") (pin "B7") (pinfunction "7_B7") (pintype "bidirectional"))
      (node (ref "J1") (pin "B8") (pinfunction "8_B8") (pintype "bidirectional"))
      (node (ref "J1") (pin "B9") (pinfunction "9_B9") (pintype "bidirectional"))
      (node (ref "J1") (pin "C3") (pinfunction "3_C3") (pintype "bidirectional"))
      (node (ref "J1") (pin "C6") (pinfunction "6_C6") (pintype "bidirectional"))
      (node (ref "J1") (pin "D1") (pinfunction "1_D1") (pintype "bidirectional"))
      (node (ref "J1") (pin "D2") (pinfunction "2_D2") (pintype "bidirectional"))
      (node (ref "JP1") (pin "8") (pinfunction "8_8") (pintype "passive"))
      (node (ref "JP10") (pin "4") (pinfunction "4_4") (pintype "passive"))
      (node (ref "JP11") (pin "4") (pinfunction "4_4") (pintype "passive"))
      (node (ref "JP2") (pin "4") (pinfunction "4_4") (pintype "passive"))
      (node (ref "JP3") (pin "4") (pinfunction "4_4") (pintype "passive"))
      (node (ref "JP4") (pin "8") (pinfunction "8_8") (pintype "passive"))
      (node (ref "JP9") (pin "4") (pinfunction "4_4") (pintype "passive"))
      (node (ref "L19") (pin "1") (pinfunction "1_1") (pintype "passive"))
      (node (ref "L6") (pin "1") (pinfunction "1_1") (pintype "passive"))
      (node (ref "R10") (pin "2") (pinfunction "2_2") (pintype "bidirectional"))
      (node (ref "R15") (pin "2") (pinfunction "2_2") (pintype "bidirectional"))
      (node (ref "R16") (pin "2") (pinfunction "2_2") (pintype "bidirectional"))
      (node (ref "R17") (pin "2") (pinfunction "2_2") (pintype "bidirectional"))
      (node (ref "R18") (pin "2") (pinfunction "2_2") (pintype "bidirectional"))
      (node (ref "R19") (pin "2") (pinfunction "2_2") (pintype "bidirectional"))
      (node (ref "R20") (pin "2") (pinfunction "2_2") (pintype "bidirectional"))
      (node (ref "R23") (pin "2") (pinfunction "2_2") (pintype "bidirectional"))
      (node (ref "R24") (pin "2") (pinfunction "2_2") (pintype "bidirectional"))
      (node (ref "R25") (pin "2") (pinfunction "2_2") (pintype "bidirectional"))
      (node (ref "R26") (pin "2") (pinfunction "2_2") (pintype "bidirectional"))
      (node (ref "R27") (pin "2") (pinfunction "2_2") (pintype "bidirectional"))
      (node (ref "R28") (pin "2") (pinfunction "2_2") (pintype "bidirectional"))
      (node (ref "R3") (pin "2") (pinfunction "2_2") (pintype "bidirectional"))
      (node (ref "R33") (pin "2") (pinfunction "2_2") (pintype "bidirectional"))
      (node (ref "R40") (pin "2") (pinfunction "2_2") (pintype "bidirectional"))
      (node (ref "R45") (pin "2") (pinfunction "2_2") (pintype "bidirectional"))
      (node (ref "R47") (pin "2") (pinfunction "2_2") (pintype "bidirectional"))
      (node (ref "R49") (pin "2") (pinfunction "2_2") (pintype "bidirectional"))
      (node (ref "R51") (pin "2") (pinfunction "2_2") (pintype "bidirectional"))
      (node (ref "R52") (pin "2") (pinfunction "2_2") (pintype "bidirectional"))
      (node (ref "R55") (pin "2") (pinfunction "2_2") (pintype "bidirectional"))
      (node (ref "R56") (pin "2") (pinfunction "2_2") (pintype "bidirectional"))
      (node (ref "R59") (pin "2") (pinfunction "2_2") (pintype "bidirectional"))
      (node (ref "R60") (pin "2") (pinfunction "2_2") (pintype "bidirectional"))
      (node (ref "R65") (pin "2") (pinfunction "2_2") (pintype "bidirectional"))
      (node (ref "R70") (pin "2") (pinfunction "2_2") (pintype "bidirectional"))
      (node (ref "R74") (pin "2") (pinfunction "2_2") (pintype "bidirectional"))
      (node (ref "R75") (pin "1") (pinfunction "1_1") (pintype "bidirectional"))
      (node (ref "R77") (pin "2") (pinfunction "2_2") (pintype "bidirectional"))
      (node (ref "R88") (pin "2") (pinfunction "2_2") (pintype "bidirectional"))
      (node (ref "R9") (pin "2") (pinfunction "2_2") (pintype "bidirectional"))
      (node (ref "R90") (pin "2") (pinfunction "2_2") (pintype "bidirectional"))
      (node (ref "R91") (pin "2") (pinfunction "2_2") (pintype "bidirectional"))
      (node (ref "U1") (pin "32") (pinfunction "EXT_XOSC_32") (pintype "input"))
      (node (ref "U1") (pin "33") (pinfunction "GND_33") (pintype "power_in"))
      (node (ref "U10") (pin "13") (pinfunction "GND_13") (pintype "power_in"))
      (node (ref "U10") (pin "17") (pinfunction "PPAD_17") (pintype "power_in"))
      (node (ref "U11") (pin "13") (pinfunction "GND_13") (pintype "power_in"))
      (node (ref "U11") (pin "17") (pinfunction "PPAD_17") (pintype "power_in"))
      (node (ref "U12") (pin "1") (pinfunction "A1_1") (pintype "passive"))
      (node (ref "U12") (pin "2") (pinfunction "A0_2") (pintype "passive"))
      (node (ref "U12") (pin "7") (pinfunction "GND_7") (pintype "power_in"))
      (node (ref "U13") (pin "1") (pinfunction "A1_1") (pintype "passive"))
      (node (ref "U13") (pin "7") (pinfunction "GND_7") (pintype "power_in"))
      (node (ref "U14") (pin "2") (pinfunction "GND_2") (pintype "power_in"))
      (node (ref "U15") (pin "4") (pinfunction "VSS_4") (pintype "bidirectional"))
      (node (ref "U15") (pin "9") (pinfunction "VSS_9") (pintype "bidirectional"))
      (node (ref "U16") (pin "4") (pinfunction "VSS_4") (pintype "bidirectional"))
      (node (ref "U16") (pin "9") (pinfunction "VSS_9") (pintype "bidirectional"))
      (node (ref "U17") (pin "1") (pinfunction "GND_1") (pintype "bidirectional"))
      (node (ref "U17") (pin "10") (pinfunction "GND_10") (pintype "bidirectional"))
      (node (ref "U17") (pin "12") (pinfunction "GND_12") (pintype "bidirectional"))
      (node (ref "U17") (pin "13") (pinfunction "GND_13") (pintype "bidirectional"))
      (node (ref "U17") (pin "3") (pinfunction "GND_3") (pintype "bidirectional"))
      (node (ref "U17") (pin "4") (pinfunction "GND_4") (pintype "bidirectional"))
      (node (ref "U17") (pin "6") (pinfunction "GND_6") (pintype "bidirectional"))
      (node (ref "U18") (pin "1") (pinfunction "A1_1") (pintype "passive"))
      (node (ref "U18") (pin "7") (pinfunction "GND_7") (pintype "power_in"))
      (node (ref "U19") (pin "10") (pinfunction "PGND_2_10") (pintype "passive"))
      (node (ref "U19") (pin "11") (pinfunction "PGND_3_11") (pintype "passive"))
      (node (ref "U19") (pin "12") (pinfunction "PGND_4_12") (pintype "passive"))
      (node (ref "U19") (pin "13") (pinfunction "PGND_5_13") (pintype "passive"))
      (node (ref "U19") (pin "14") (pinfunction "PGND_14") (pintype "passive"))
      (node (ref "U19") (pin "22") (pinfunction "GND_22") (pintype "passive"))
      (node (ref "U19") (pin "27") (pinfunction "GND1_27") (pintype "passive"))
      (node (ref "U19") (pin "28") (pinfunction "GND2_28") (pintype "passive"))
      (node (ref "U19") (pin "29") (pinfunction "EPAD_29") (pintype "passive"))
      (node (ref "U2") (pin "A1") (pinfunction "VSS_2_A1") (pintype "power_in"))
      (node (ref "U2") (pin "A10") (pinfunction "VSS_3_A10") (pintype "power_in"))
      (node (ref "U2") (pin "A19") (pinfunction "VSS_4_A19") (pintype "power_in"))
      (node (ref "U2") (pin "E12") (pinfunction "VSS_8_E12") (pintype "power_in"))
      (node (ref "U2") (pin "E14") (pinfunction "VSS_9_E14") (pintype "power_in"))
      (node (ref "U2") (pin "E15") (pinfunction "VSS_10_E15") (pintype "power_in"))
      (node (ref "U2") (pin "E5") (pinfunction "VSS_5_E5") (pintype "power_in"))
      (node (ref "U2") (pin "E6") (pinfunction "VSS_6_E6") (pintype "power_in"))
      (node (ref "U2") (pin "E8") (pinfunction "VSS_7_E8") (pintype "power_in"))
      (node (ref "U2") (pin "F12") (pinfunction "VSS_14_F12") (pintype "power_in"))
      (node (ref "U2") (pin "F14") (pinfunction "VSS_15_F14") (pintype "power_in"))
      (node (ref "U2") (pin "F15") (pinfunction "VSS_16_F15") (pintype "power_in"))
      (node (ref "U2") (pin "F5") (pinfunction "VSS_11_F5") (pintype "power_in"))
      (node (ref "U2") (pin "F6") (pinfunction "VSS_12_F6") (pintype "power_in"))
      (node (ref "U2") (pin "F8") (pinfunction "VSS_13_F8") (pintype "power_in"))
      (node (ref "U2") (pin "G16") (pinfunction "VSS_17_G16") (pintype "power_in"))
      (node (ref "U2") (pin "G17") (pinfunction "VSS_18_G17") (pintype "power_in"))
      (node (ref "U2") (pin "H10") (pinfunction "VSS_21_H10") (pintype "power_in"))
      (node (ref "U2") (pin "H11") (pinfunction "VSS_22_H11") (pintype "power_in"))
      (node (ref "U2") (pin "H12") (pinfunction "VSS_23_H12") (pintype "power_in"))
      (node (ref "U2") (pin "H14") (pinfunction "VSS_24_H14") (pintype "power_in"))
      (node (ref "U2") (pin "H15") (pinfunction "VSS_25_H15") (pintype "power_in"))
      (node (ref "U2") (pin "H18") (pinfunction "VSSOSC_2_H18") (pintype "power_in"))
      (node (ref "U2") (pin "H19") (pinfunction "VSSOSC_H19") (pintype "power_in"))
      (node (ref "U2") (pin "H8") (pinfunction "VSS_19_H8") (pintype "power_in"))
      (node (ref "U2") (pin "H9") (pinfunction "VSS_20_H9") (pintype "power_in"))
      (node (ref "U2") (pin "J10") (pinfunction "VSS_30_J10") (pintype "power_in"))
      (node (ref "U2") (pin "J11") (pinfunction "VSS_31_J11") (pintype "power_in"))
      (node (ref "U2") (pin "J12") (pinfunction "VSS_32_J12") (pintype "power_in"))
      (node (ref "U2") (pin "J5") (pinfunction "VSS_26_J5") (pintype "power_in"))
      (node (ref "U2") (pin "J6") (pinfunction "VSS_27_J6") (pintype "power_in"))
      (node (ref "U2") (pin "J8") (pinfunction "VSS_28_J8") (pintype "power_in"))
      (node (ref "U2") (pin "J9") (pinfunction "VSS_29_J9") (pintype "power_in"))
      (node (ref "U2") (pin "K10") (pinfunction "VSS_35_K10") (pintype "power_in"))
      (node (ref "U2") (pin "K11") (pinfunction "VSS_36_K11") (pintype "power_in"))
      (node (ref "U2") (pin "K12") (pinfunction "VSS_37_K12") (pintype "power_in"))
      (node (ref "U2") (pin "K14") (pinfunction "VSS_38_K14") (pintype "power_in"))
      (node (ref "U2") (pin "K15") (pinfunction "VSS_39_K15") (pintype "power_in"))
      (node (ref "U2") (pin "K8") (pinfunction "VSS_33_K8") (pintype "power_in"))
      (node (ref "U2") (pin "K9") (pinfunction "VSS_34_K9") (pintype "power_in"))
      (node (ref "U2") (pin "L10") (pinfunction "VSS_44_L10") (pintype "power_in"))
      (node (ref "U2") (pin "L11") (pinfunction "VSS_45_L11") (pintype "power_in"))
      (node (ref "U2") (pin "L12") (pinfunction "VSS_46_L12") (pintype "power_in"))
      (node (ref "U2") (pin "L18") (pinfunction "VSS_47_L18") (pintype "power_in"))
      (node (ref "U2") (pin "L5") (pinfunction "VSS_40_L5") (pintype "power_in"))
      (node (ref "U2") (pin "L6") (pinfunction "VSS_41_L6") (pintype "power_in"))
      (node (ref "U2") (pin "L8") (pinfunction "VSS_42_L8") (pintype "power_in"))
      (node (ref "U2") (pin "L9") (pinfunction "VSS_43_L9") (pintype "power_in"))
      (node (ref "U2") (pin "M10") (pinfunction "VSS_50_M10") (pintype "power_in"))
      (node (ref "U2") (pin "M11") (pinfunction "VSS_51_M11") (pintype "power_in"))
      (node (ref "U2") (pin "M12") (pinfunction "VSS_52_M12") (pintype "power_in"))
      (node (ref "U2") (pin "M14") (pinfunction "VSS_53_M14") (pintype "power_in"))
      (node (ref "U2") (pin "M15") (pinfunction "VSS_54_M15") (pintype "power_in"))
      (node (ref "U2") (pin "M8") (pinfunction "VSS_48_M8") (pintype "power_in"))
      (node (ref "U2") (pin "M9") (pinfunction "VSS_49_M9") (pintype "power_in"))
      (node (ref "U2") (pin "N1") (pinfunction "VSS_55_N1") (pintype "power_in"))
      (node (ref "U2") (pin "N5") (pinfunction "VSS_56_N5") (pintype "power_in"))
      (node (ref "U2") (pin "N6") (pinfunction "VSS_57_N6") (pintype "power_in"))
      (node (ref "U2") (pin "P1") (pinfunction "VSSA_2_P1") (pintype "power_in"))
      (node (ref "U2") (pin "P11") (pinfunction "VSS_60_P11") (pintype "power_in"))
      (node (ref "U2") (pin "P12") (pinfunction "VSS_61_P12") (pintype "power_in"))
      (node (ref "U2") (pin "P14") (pinfunction "VSS_62_P14") (pintype "power_in"))
      (node (ref "U2") (pin "P15") (pinfunction "VSS_63_P15") (pintype "power_in"))
      (node (ref "U2") (pin "P2") (pinfunction "VREFLOC_P2") (pintype "passive"))
      (node (ref "U2") (pin "P5") (pinfunction "VSSA_3_P5") (pintype "power_in"))
      (node (ref "U2") (pin "P7") (pinfunction "VSS_58_P7") (pintype "power_in"))
      (node (ref "U2") (pin "P8") (pinfunction "VSS_59_P8") (pintype "power_in"))
      (node (ref "U2") (pin "R14") (pinfunction "VSS_66_R14") (pintype "power_in"))
      (node (ref "U2") (pin "R15") (pinfunction "VSS_67_R15") (pintype "power_in"))
      (node (ref "U2") (pin "R2") (pinfunction "VREFLOA_R2") (pintype "passive"))
      (node (ref "U2") (pin "R5") (pinfunction "VSSA_4_R5") (pintype "power_in"))
      (node (ref "U2") (pin "R7") (pinfunction "VSS_64_R7") (pintype "power_in"))
      (node (ref "U2") (pin "R8") (pinfunction "VSS_65_R8") (pintype "power_in"))
      (node (ref "U2") (pin "V6") (pinfunction "VREFLOB_V6") (pintype "passive"))
      (node (ref "U2") (pin "V7") (pinfunction "VSSA_5_V7") (pintype "power_in"))
      (node (ref "U2") (pin "W1") (pinfunction "VSSA_W1") (pintype "power_in"))
      (node (ref "U2") (pin "W19") (pinfunction "VSS_W19") (pintype "power_in"))
      (node (ref "U2") (pin "W6") (pinfunction "VREFLOD_W6") (pintype "passive"))
      (node (ref "U2") (pin "W7") (pinfunction "VSS_68_W7") (pintype "power_in"))
      (node (ref "U20") (pin "32") (pinfunction "EXT_XOSC_32") (pintype "input"))
      (node (ref "U20") (pin "33") (pinfunction "GND_33") (pintype "power_in"))
      (node (ref "U21") (pin "12") (pinfunction "GND_2_12") (pintype "power_in"))
      (node (ref "U21") (pin "27") (pinfunction "GND_3_27") (pintype "power_in"))
      (node (ref "U21") (pin "3") (pinfunction "GNDA_3") (pintype "power_in"))
      (node (ref "U21") (pin "39") (pinfunction "GND_4_39") (pintype "power_in"))
      (node (ref "U21") (pin "55") (pinfunction "GND_55") (pintype "power_in"))
      (node (ref "U22") (pin "2") (pinfunction "GND_2") (pintype "power_in"))
      (node (ref "U23") (pin "2") (pinfunction "GND_2") (pintype "power_in"))
      (node (ref "U24") (pin "4") (pinfunction "VSS_4") (pintype "bidirectional"))
      (node (ref "U24") (pin "9") (pinfunction "VSS_9") (pintype "bidirectional"))
      (node (ref "U3") (pin "12") (pinfunction "GND_2_12") (pintype "power_in"))
      (node (ref "U3") (pin "27") (pinfunction "GND_3_27") (pintype "power_in"))
      (node (ref "U3") (pin "3") (pinfunction "GNDA_3") (pintype "power_in"))
      (node (ref "U3") (pin "39") (pinfunction "GND_4_39") (pintype "power_in"))
      (node (ref "U3") (pin "55") (pinfunction "GND_55") (pintype "power_in"))
      (node (ref "U34") (pin "P$2") (pinfunction "GND_P$2") (pintype "power_in"))
      (node (ref "U34") (pin "P$3") (pinfunction "ADR1_P$3") (pintype "bidirectional"))
      (node (ref "U34") (pin "P$5") (pinfunction "ADR0_P$5") (pintype "bidirectional"))
      (node (ref "U4") (pin "2") (pinfunction "GND_2") (pintype "power_in"))
      (node (ref "U5") (pin "2") (pinfunction "GND_2") (pintype "power_in"))
      (node (ref "U6") (pin "A1") (pinfunction "VSS_A1") (pintype "bidirectional"))
      (node (ref "U6") (pin "A3") (pinfunction "VSSQ_A3") (pintype "bidirectional"))
      (node (ref "U6") (pin "B7") (pinfunction "VSSQ_B7") (pintype "bidirectional"))
      (node (ref "U6") (pin "C3") (pinfunction "VSSQ_C3") (pintype "bidirectional"))
      (node (ref "U6") (pin "D7") (pinfunction "VSSQ_D7") (pintype "bidirectional"))
      (node (ref "U6") (pin "E3") (pinfunction "VSS_E3") (pintype "bidirectional"))
      (node (ref "U6") (pin "J1") (pinfunction "VSS_J1") (pintype "bidirectional"))
      (node (ref "U7") (pin "P$2") (pinfunction "GND_P$2") (pintype "power_in"))
      (node (ref "U7") (pin "P$3") (pinfunction "ADR1_P$3") (pintype "bidirectional"))
      (node (ref "U8") (pin "1") (pinfunction "SDO_1") (pintype "bidirectional"))
      (node (ref "U8") (pin "2") (pinfunction "GND_2") (pintype "power_in"))
      (node (ref "U8") (pin "3") (pinfunction "GND_3") (pintype "power_in"))
      (node (ref "U8") (pin "6") (pinfunction "GNDIO_6") (pintype "power_in"))
      (node (ref "U8") (pin "7") (pinfunction "GND_7") (pintype "power_in"))
      (node (ref "U9") (pin "2") (pinfunction "GND_2") (pintype "power_in"))
      (node (ref "U9") (pin "3") (pinfunction "GND_3") (pintype "power_in"))
      (node (ref "U9") (pin "6") (pinfunction "GNDIO_6") (pintype "power_in"))
      (node (ref "U9") (pin "7") (pinfunction "GND_7") (pintype "power_in"))
      (node (ref "X2") (pin "2") (pinfunction "2_2") (pintype "passive"))
      (node (ref "X2") (pin "3") (pinfunction "2_3") (pintype "passive"))
      (node (ref "X2") (pin "4") (pinfunction "2_4") (pintype "passive"))
      (node (ref "X2") (pin "5") (pinfunction "2_5") (pintype "passive"))
      (node (ref "X3") (pin "3") (pinfunction "KL_3") (pintype "passive"))
      (node (ref "X3") (pin "5") (pinfunction "KL_5") (pintype "passive"))
      (node (ref "X3") (pin "9") (pinfunction "KL_9") (pintype "passive"))
      (node (ref "X4") (pin "3") (pinfunction "KL_3") (pintype "passive"))
      (node (ref "X4") (pin "5") (pinfunction "KL_5") (pintype "passive"))
      (node (ref "X4") (pin "9") (pinfunction "KL_9") (pintype "passive"))
      (node (ref "X5") (pin "3") (pinfunction "KL_3") (pintype "passive"))
      (node (ref "X5") (pin "5") (pinfunction "KL_5") (pintype "passive"))
      (node (ref "X5") (pin "9") (pinfunction "KL_9") (pintype "passive"))
      (node (ref "X6") (pin "1") (pinfunction "S_1") (pintype "passive"))
      (node (ref "X6") (pin "3") (pinfunction "S_3") (pintype "passive"))
      (node (ref "X8") (pin "3") (pinfunction "KL_3") (pintype "passive"))
      (node (ref "X8") (pin "5") (pinfunction "KL_5") (pintype "passive"))
      (node (ref "X8") (pin "9") (pinfunction "KL_9") (pintype "passive"))
      (node (ref "Y1") (pin "2") (pinfunction "VSS_2") (pintype "bidirectional"))
      (node (ref "Y1") (pin "4") (pinfunction "VSS_4") (pintype "bidirectional"))
      (node (ref "Y2") (pin "2") (pinfunction "VSS_2") (pintype "bidirectional"))
      (node (ref "Y2") (pin "4") (pinfunction "VSS_4") (pintype "bidirectional"))
      (node (ref "Y3") (pin "2") (pinfunction "VSS_2") (pintype "bidirectional"))
      (node (ref "Y3") (pin "4") (pinfunction "VSS_4") (pintype "bidirectional"))
    )
    (net (code "225") (name "unconnected-(IC1-I{slash}O_15-Pad22)") (class "Default")
      (node (ref "IC1") (pin "22") (pinfunction "I/O_15_22") (pintype "bidirectional"))
    )
    (net (code "226") (name "unconnected-(IC1-I{slash}O_16-Pad23)") (class "Default")
      (node (ref "IC1") (pin "23") (pinfunction "I/O_16_23") (pintype "bidirectional"))
    )
    (net (code "227") (name "unconnected-(IC1-I{slash}O_19-Pad29)") (class "Default")
      (node (ref "IC1") (pin "29") (pinfunction "I/O_19_29") (pintype "bidirectional"))
    )
    (net (code "228") (name "unconnected-(IC1-I{slash}O_20-Pad30)") (class "Default")
      (node (ref "IC1") (pin "30") (pinfunction "I/O_20_30") (pintype "bidirectional"))
    )
    (net (code "229") (name "unconnected-(IC1-I{slash}O_21-Pad31)") (class "Default")
      (node (ref "IC1") (pin "31") (pinfunction "I/O_21_31") (pintype "bidirectional"))
    )
    (net (code "230") (name "unconnected-(IC1-I{slash}O_22-Pad32)") (class "Default")
      (node (ref "IC1") (pin "32") (pinfunction "I/O_22_32") (pintype "bidirectional"))
    )
    (net (code "231") (name "unconnected-(IC1-I{slash}O{slash}GCK3-Pad1)") (class "Default")
      (node (ref "IC1") (pin "1") (pinfunction "I/O/GCK3_1") (pintype "bidirectional"))
    )
    (net (code "232") (name "unconnected-(IC1-I{slash}O{slash}GSR-Pad33)") (class "Default")
      (node (ref "IC1") (pin "33") (pinfunction "I/O/GSR_33") (pintype "bidirectional"))
    )
    (net (code "233") (name "unconnected-(IC1-I{slash}O{slash}GTS2-Pad34)") (class "Default")
      (node (ref "IC1") (pin "34") (pinfunction "I/O/GTS2_34") (pintype "bidirectional"))
    )
    (net (code "234") (name "unconnected-(U1-GPIO0-Pad10)") (class "Default")
      (node (ref "U1") (pin "10") (pinfunction "GPIO0_10") (pintype "bidirectional"))
    )
    (net (code "235") (name "unconnected-(U1-GPIO2-Pad4)") (class "Default")
      (node (ref "U1") (pin "4") (pinfunction "GPIO2_4") (pintype "bidirectional"))
    )
    (net (code "236") (name "unconnected-(U1-GPIO3-Pad3)") (class "Default")
      (node (ref "U1") (pin "3") (pinfunction "GPIO3_3") (pintype "bidirectional"))
    )
    (net (code "237") (name "unconnected-(U1-NC-Pad16)") (class "Default")
      (node (ref "U1") (pin "16") (pinfunction "NC_16") (pintype "passive"))
    )
    (net (code "238") (name "unconnected-(U2B-ADCIN14_CMPIN4P-PadT4)") (class "Default")
      (node (ref "U2") (pin "T4") (pinfunction "ADCIN14_CMPIN4P_T4") (pintype "passive"))
    )
    (net (code "239") (name "unconnected-(U2B-ADCIN15_CMPIN4N-PadU4)") (class "Default")
      (node (ref "U2") (pin "U4") (pinfunction "ADCIN15_CMPIN4N_U4") (pintype "passive"))
    )
    (net (code "240") (name "unconnected-(U2B-ADCINC2_CMPIN6P-PadR3)") (class "Default")
      (node (ref "U2") (pin "R3") (pinfunction "ADCINC2_CMPIN6P_R3") (pintype "passive"))
    )
    (net (code "241") (name "unconnected-(U2B-ADCINC3_CMPIN6N-PadP3)") (class "Default")
      (node (ref "U2") (pin "P3") (pinfunction "ADCINC3_CMPIN6N_P3") (pintype "passive"))
    )
    (net (code "242") (name "unconnected-(U2B-ADCINC4_CMPIN5P-PadR4)") (class "Default")
      (node (ref "U2") (pin "R4") (pinfunction "ADCINC4_CMPIN5P_R4") (pintype "passive"))
    )
    (net (code "243") (name "unconnected-(U2B-ADCINC5_CMPIN5N-PadP4)") (class "Default")
      (node (ref "U2") (pin "P4") (pinfunction "ADCINC5_CMPIN5N_P4") (pintype "passive"))
    )
    (net (code "244") (name "unconnected-(U2B-ADCIND0_CMPIN7P-PadT5)") (class "Default")
      (node (ref "U2") (pin "T5") (pinfunction "ADCIND0_CMPIN7P_T5") (pintype "passive"))
    )
    (net (code "245") (name "unconnected-(U2B-ADCIND1_CMPIN7N-PadU5)") (class "Default")
      (node (ref "U2") (pin "U5") (pinfunction "ADCIND1_CMPIN7N_U5") (pintype "passive"))
    )
    (net (code "246") (name "unconnected-(U2B-ADCIND2_CMPIN8P-PadT6)") (class "Default")
      (node (ref "U2") (pin "T6") (pinfunction "ADCIND2_CMPIN8P_T6") (pintype "passive"))
    )
    (net (code "247") (name "unconnected-(U2B-ADCIND3_CMPIN8N-PadU6)") (class "Default")
      (node (ref "U2") (pin "U6") (pinfunction "ADCIND3_CMPIN8N_U6") (pintype "passive"))
    )
    (net (code "248") (name "unconnected-(U2B-ADCIND4-PadT7)") (class "Default")
      (node (ref "U2") (pin "T7") (pinfunction "ADCIND4_T7") (pintype "passive"))
    )
    (net (code "249") (name "unconnected-(U2B-ADCIND5-PadU7)") (class "Default")
      (node (ref "U2") (pin "U7") (pinfunction "ADCIND5_U7") (pintype "passive"))
    )
    (net (code "250") (name "unconnected-(U2C-FLT1-PadW12)") (class "Default")
      (node (ref "U2") (pin "W12") (pinfunction "FLT1_W12") (pintype "bidirectional"))
    )
    (net (code "251") (name "unconnected-(U2C-FLT2-PadV13)") (class "Default")
      (node (ref "U2") (pin "V13") (pinfunction "FLT2_V13") (pintype "bidirectional"))
    )
    (net (code "252") (name "unconnected-(U2C-NC-PadJ18)") (class "Default")
      (node (ref "U2") (pin "J18") (pinfunction "NC_J18") (pintype "passive"))
    )
    (net (code "253") (name "unconnected-(U2C-NC_2-PadH4)") (class "Default")
      (node (ref "U2") (pin "H4") (pinfunction "NC_2_H4") (pintype "passive"))
    )
    (net (code "254") (name "unconnected-(U2D-GPIO26-PadK1)") (class "Default")
      (node (ref "U2") (pin "K1") (pinfunction "GPIO26_K1") (pintype "bidirectional"))
    )
    (net (code "255") (name "unconnected-(U2D-GPIO27-PadL1)") (class "Default")
      (node (ref "U2") (pin "L1") (pinfunction "GPIO27_L1") (pintype "bidirectional"))
    )
    (net (code "256") (name "unconnected-(U2D-GPIO28-PadV11)") (class "Default")
      (node (ref "U2") (pin "V11") (pinfunction "GPIO28_V11") (pintype "bidirectional"))
    )
    (net (code "257") (name "unconnected-(U2E-GPIO44-PadK18)") (class "Default")
      (node (ref "U2") (pin "K18") (pinfunction "GPIO44_K18") (pintype "bidirectional"))
    )
    (net (code "258") (name "unconnected-(U2E-GPIO53-PadP17)") (class "Default")
      (node (ref "U2") (pin "P17") (pinfunction "GPIO53_P17") (pintype "bidirectional"))
    )
    (net (code "259") (name "unconnected-(U2E-GPIO54-PadP18)") (class "Default")
      (node (ref "U2") (pin "P18") (pinfunction "GPIO54_P18") (pintype "bidirectional"))
    )
    (net (code "260") (name "unconnected-(U2E-GPIO63-PadJ16)") (class "Default")
      (node (ref "U2") (pin "J16") (pinfunction "GPIO63_J16") (pintype "bidirectional"))
    )
    (net (code "261") (name "unconnected-(U2E-GPIO64-PadL17)") (class "Default")
      (node (ref "U2") (pin "L17") (pinfunction "GPIO64_L17") (pintype "bidirectional"))
    )
    (net (code "262") (name "unconnected-(U2E-GPIO65-PadK16)") (class "Default")
      (node (ref "U2") (pin "K16") (pinfunction "GPIO65_K16") (pintype "bidirectional"))
    )
    (net (code "263") (name "unconnected-(U2E-GPIO66-PadK17)") (class "Default")
      (node (ref "U2") (pin "K17") (pinfunction "GPIO66_K17") (pintype "bidirectional"))
    )
    (net (code "264") (name "unconnected-(U2E-GPIO67-PadB19)") (class "Default")
      (node (ref "U2") (pin "B19") (pinfunction "GPIO67_B19") (pintype "bidirectional"))
    )
    (net (code "265") (name "unconnected-(U2E-GPIO68-PadC18)") (class "Default")
      (node (ref "U2") (pin "C18") (pinfunction "GPIO68_C18") (pintype "bidirectional"))
    )
    (net (code "266") (name "unconnected-(U2E-GPIO77-PadA15)") (class "Default")
      (node (ref "U2") (pin "A15") (pinfunction "GPIO77_A15") (pintype "bidirectional"))
    )
    (net (code "267") (name "unconnected-(U2E-GPIO78-PadB15)") (class "Default")
      (node (ref "U2") (pin "B15") (pinfunction "GPIO78_B15") (pintype "bidirectional"))
    )
    (net (code "268") (name "unconnected-(U2E-GPIO79-PadC15)") (class "Default")
      (node (ref "U2") (pin "C15") (pinfunction "GPIO79_C15") (pintype "bidirectional"))
    )
    (net (code "269") (name "unconnected-(U2E-GPIO80-PadD15)") (class "Default")
      (node (ref "U2") (pin "D15") (pinfunction "GPIO80_D15") (pintype "bidirectional"))
    )
    (net (code "270") (name "unconnected-(U2E-GPIO81-PadA14)") (class "Default")
      (node (ref "U2") (pin "A14") (pinfunction "GPIO81_A14") (pintype "bidirectional"))
    )
    (net (code "271") (name "unconnected-(U2E-GPIO82-PadB14)") (class "Default")
      (node (ref "U2") (pin "B14") (pinfunction "GPIO82_B14") (pintype "bidirectional"))
    )
    (net (code "272") (name "unconnected-(U2F-GPIO90-PadA5)") (class "Default")
      (node (ref "U2") (pin "A5") (pinfunction "GPIO90_A5") (pintype "bidirectional"))
    )
    (net (code "273") (name "unconnected-(U2F-GPIO91-PadB5)") (class "Default")
      (node (ref "U2") (pin "B5") (pinfunction "GPIO91_B5") (pintype "bidirectional"))
    )
    (net (code "274") (name "unconnected-(U2F-GPIO92-PadA4)") (class "Default")
      (node (ref "U2") (pin "A4") (pinfunction "GPIO92_A4") (pintype "bidirectional"))
    )
    (net (code "275") (name "unconnected-(U2F-GPIO93-PadB4)") (class "Default")
      (node (ref "U2") (pin "B4") (pinfunction "GPIO93_B4") (pintype "bidirectional"))
    )
    (net (code "276") (name "unconnected-(U2F-GPIO94-PadA3)") (class "Default")
      (node (ref "U2") (pin "A3") (pinfunction "GPIO94_A3") (pintype "bidirectional"))
    )
    (net (code "277") (name "unconnected-(U2F-GPIO95-PadB3)") (class "Default")
      (node (ref "U2") (pin "B3") (pinfunction "GPIO95_B3") (pintype "bidirectional"))
    )
    (net (code "278") (name "unconnected-(U2F-GPIO96-PadC3)") (class "Default")
      (node (ref "U2") (pin "C3") (pinfunction "GPIO96_C3") (pintype "bidirectional"))
    )
    (net (code "279") (name "unconnected-(U2F-GPIO97-PadA2)") (class "Default")
      (node (ref "U2") (pin "A2") (pinfunction "GPIO97_A2") (pintype "bidirectional"))
    )
    (net (code "280") (name "unconnected-(U2F-GPIO98-PadF1)") (class "Default")
      (node (ref "U2") (pin "F1") (pinfunction "GPIO98_F1") (pintype "bidirectional"))
    )
    (net (code "281") (name "unconnected-(U2F-GPIO99-PadG1)") (class "Default")
      (node (ref "U2") (pin "G1") (pinfunction "GPIO99_G1") (pintype "bidirectional"))
    )
    (net (code "282") (name "unconnected-(U2F-GPIO100-PadH1)") (class "Default")
      (node (ref "U2") (pin "H1") (pinfunction "GPIO100_H1") (pintype "bidirectional"))
    )
    (net (code "283") (name "unconnected-(U2F-GPIO101-PadH2)") (class "Default")
      (node (ref "U2") (pin "H2") (pinfunction "GPIO101_H2") (pintype "bidirectional"))
    )
    (net (code "284") (name "unconnected-(U2F-GPIO102-PadH3)") (class "Default")
      (node (ref "U2") (pin "H3") (pinfunction "GPIO102_H3") (pintype "bidirectional"))
    )
    (net (code "285") (name "unconnected-(U2F-GPIO103-PadJ1)") (class "Default")
      (node (ref "U2") (pin "J1") (pinfunction "GPIO103_J1") (pintype "bidirectional"))
    )
    (net (code "286") (name "unconnected-(U2F-GPIO106-PadL2)") (class "Default")
      (node (ref "U2") (pin "L2") (pinfunction "GPIO106_L2") (pintype "bidirectional"))
    )
    (net (code "287") (name "unconnected-(U2F-GPIO107-PadL3)") (class "Default")
      (node (ref "U2") (pin "L3") (pinfunction "GPIO107_L3") (pintype "bidirectional"))
    )
    (net (code "288") (name "unconnected-(U2F-GPIO108-PadL4)") (class "Default")
      (node (ref "U2") (pin "L4") (pinfunction "GPIO108_L4") (pintype "bidirectional"))
    )
    (net (code "289") (name "unconnected-(U2F-GPIO109-PadN2)") (class "Default")
      (node (ref "U2") (pin "N2") (pinfunction "GPIO109_N2") (pintype "bidirectional"))
    )
    (net (code "290") (name "unconnected-(U2F-GPIO110-PadM2)") (class "Default")
      (node (ref "U2") (pin "M2") (pinfunction "GPIO110_M2") (pintype "bidirectional"))
    )
    (net (code "291") (name "unconnected-(U2F-GPIO111-PadM4)") (class "Default")
      (node (ref "U2") (pin "M4") (pinfunction "GPIO111_M4") (pintype "bidirectional"))
    )
    (net (code "292") (name "unconnected-(U2F-GPIO112-PadM3)") (class "Default")
      (node (ref "U2") (pin "M3") (pinfunction "GPIO112_M3") (pintype "bidirectional"))
    )
    (net (code "293") (name "unconnected-(U2F-GPIO113-PadN4)") (class "Default")
      (node (ref "U2") (pin "N4") (pinfunction "GPIO113_N4") (pintype "bidirectional"))
    )
    (net (code "294") (name "unconnected-(U2F-GPIO114-PadN3)") (class "Default")
      (node (ref "U2") (pin "N3") (pinfunction "GPIO114_N3") (pintype "bidirectional"))
    )
    (net (code "295") (name "unconnected-(U2F-GPIO115-PadV12)") (class "Default")
      (node (ref "U2") (pin "V12") (pinfunction "GPIO115_V12") (pintype "bidirectional"))
    )
    (net (code "296") (name "unconnected-(U2F-GPIO116-PadW10)") (class "Default")
      (node (ref "U2") (pin "W10") (pinfunction "GPIO116_W10") (pintype "bidirectional"))
    )
    (net (code "297") (name "unconnected-(U2F-GPIO117-PadU12)") (class "Default")
      (node (ref "U2") (pin "U12") (pinfunction "GPIO117_U12") (pintype "bidirectional"))
    )
    (net (code "298") (name "unconnected-(U2F-GPIO118-PadT12)") (class "Default")
      (node (ref "U2") (pin "T12") (pinfunction "GPIO118_T12") (pintype "bidirectional"))
    )
    (net (code "299") (name "unconnected-(U2F-GPIO119-PadT15)") (class "Default")
      (node (ref "U2") (pin "T15") (pinfunction "GPIO119_T15") (pintype "bidirectional"))
    )
    (net (code "300") (name "unconnected-(U2F-GPIO120-PadU15)") (class "Default")
      (node (ref "U2") (pin "U15") (pinfunction "GPIO120_U15") (pintype "bidirectional"))
    )
    (net (code "301") (name "unconnected-(U2F-GPIO121-PadW16)") (class "Default")
      (node (ref "U2") (pin "W16") (pinfunction "GPIO121_W16") (pintype "bidirectional"))
    )
    (net (code "302") (name "unconnected-(U2F-GPIO122-PadT8)") (class "Default")
      (node (ref "U2") (pin "T8") (pinfunction "GPIO122_T8") (pintype "bidirectional"))
    )
    (net (code "303") (name "unconnected-(U2F-GPIO123-PadU8)") (class "Default")
      (node (ref "U2") (pin "U8") (pinfunction "GPIO123_U8") (pintype "bidirectional"))
    )
    (net (code "304") (name "unconnected-(U2F-GPIO124-PadV8)") (class "Default")
      (node (ref "U2") (pin "V8") (pinfunction "GPIO124_V8") (pintype "bidirectional"))
    )
    (net (code "305") (name "unconnected-(U2F-GPIO125-PadT9)") (class "Default")
      (node (ref "U2") (pin "T9") (pinfunction "GPIO125_T9") (pintype "bidirectional"))
    )
    (net (code "306") (name "unconnected-(U2G-GPIO126-PadU9)") (class "Default")
      (node (ref "U2") (pin "U9") (pinfunction "GPIO126_U9") (pintype "bidirectional"))
    )
    (net (code "307") (name "unconnected-(U2G-GPIO127-PadV9)") (class "Default")
      (node (ref "U2") (pin "V9") (pinfunction "GPIO127_V9") (pintype "bidirectional"))
    )
    (net (code "308") (name "unconnected-(U2G-GPIO128-PadW9)") (class "Default")
      (node (ref "U2") (pin "W9") (pinfunction "GPIO128_W9") (pintype "bidirectional"))
    )
    (net (code "309") (name "unconnected-(U2G-GPIO129-PadT10)") (class "Default")
      (node (ref "U2") (pin "T10") (pinfunction "GPIO129_T10") (pintype "bidirectional"))
    )
    (net (code "310") (name "unconnected-(U2G-GPIO130-PadU10)") (class "Default")
      (node (ref "U2") (pin "U10") (pinfunction "GPIO130_U10") (pintype "bidirectional"))
    )
    (net (code "311") (name "unconnected-(U2G-GPIO131-PadV10)") (class "Default")
      (node (ref "U2") (pin "V10") (pinfunction "GPIO131_V10") (pintype "bidirectional"))
    )
    (net (code "312") (name "unconnected-(U2G-GPIO132-PadW18)") (class "Default")
      (node (ref "U2") (pin "W18") (pinfunction "GPIO132_W18") (pintype "bidirectional"))
    )
    (net (code "313") (name "unconnected-(U2G-GPIO133-PadG18)") (class "Default")
      (node (ref "U2") (pin "G18") (pinfunction "GPIO133_G18") (pintype "bidirectional"))
    )
    (net (code "314") (name "unconnected-(U2G-GPIO134-PadV18)") (class "Default")
      (node (ref "U2") (pin "V18") (pinfunction "GPIO134_V18") (pintype "bidirectional"))
    )
    (net (code "315") (name "unconnected-(U2G-GPIO135-PadU18)") (class "Default")
      (node (ref "U2") (pin "U18") (pinfunction "GPIO135_U18") (pintype "bidirectional"))
    )
    (net (code "316") (name "unconnected-(U2G-GPIO136-PadT17)") (class "Default")
      (node (ref "U2") (pin "T17") (pinfunction "GPIO136_T17") (pintype "bidirectional"))
    )
    (net (code "317") (name "unconnected-(U2G-GPIO137-PadT18)") (class "Default")
      (node (ref "U2") (pin "T18") (pinfunction "GPIO137_T18") (pintype "bidirectional"))
    )
    (net (code "318") (name "unconnected-(U2G-GPIO138-PadT19)") (class "Default")
      (node (ref "U2") (pin "T19") (pinfunction "GPIO138_T19") (pintype "bidirectional"))
    )
    (net (code "319") (name "unconnected-(U2G-GPIO139-PadN19)") (class "Default")
      (node (ref "U2") (pin "N19") (pinfunction "GPIO139_N19") (pintype "bidirectional"))
    )
    (net (code "320") (name "unconnected-(U2G-GPIO140-PadM19)") (class "Default")
      (node (ref "U2") (pin "M19") (pinfunction "GPIO140_M19") (pintype "bidirectional"))
    )
    (net (code "321") (name "unconnected-(U2G-GPIO141-PadM18)") (class "Default")
      (node (ref "U2") (pin "M18") (pinfunction "GPIO141_M18") (pintype "bidirectional"))
    )
    (net (code "322") (name "unconnected-(U2G-GPIO142-PadL19)") (class "Default")
      (node (ref "U2") (pin "L19") (pinfunction "GPIO142_L19") (pintype "bidirectional"))
    )
    (net (code "323") (name "unconnected-(U2G-GPIO143-PadF18)") (class "Default")
      (node (ref "U2") (pin "F18") (pinfunction "GPIO143_F18") (pintype "bidirectional"))
    )
    (net (code "324") (name "unconnected-(U2G-GPIO144-PadF17)") (class "Default")
      (node (ref "U2") (pin "F17") (pinfunction "GPIO144_F17") (pintype "bidirectional"))
    )
    (net (code "325") (name "unconnected-(U2G-GPIO145-PadE17)") (class "Default")
      (node (ref "U2") (pin "E17") (pinfunction "GPIO145_E17") (pintype "bidirectional"))
    )
    (net (code "326") (name "unconnected-(U2G-GPIO146-PadD18)") (class "Default")
      (node (ref "U2") (pin "D18") (pinfunction "GPIO146_D18") (pintype "bidirectional"))
    )
    (net (code "327") (name "unconnected-(U2G-GPIO147-PadD17)") (class "Default")
      (node (ref "U2") (pin "D17") (pinfunction "GPIO147_D17") (pintype "bidirectional"))
    )
    (net (code "328") (name "unconnected-(U2G-GPIO148-PadD14)") (class "Default")
      (node (ref "U2") (pin "D14") (pinfunction "GPIO148_D14") (pintype "bidirectional"))
    )
    (net (code "329") (name "unconnected-(U2G-GPIO149-PadA13)") (class "Default")
      (node (ref "U2") (pin "A13") (pinfunction "GPIO149_A13") (pintype "bidirectional"))
    )
    (net (code "330") (name "unconnected-(U2G-GPIO150-PadB13)") (class "Default")
      (node (ref "U2") (pin "B13") (pinfunction "GPIO150_B13") (pintype "bidirectional"))
    )
    (net (code "331") (name "unconnected-(U2G-GPIO151-PadC13)") (class "Default")
      (node (ref "U2") (pin "C13") (pinfunction "GPIO151_C13") (pintype "bidirectional"))
    )
    (net (code "332") (name "unconnected-(U2G-GPIO152-PadD13)") (class "Default")
      (node (ref "U2") (pin "D13") (pinfunction "GPIO152_D13") (pintype "bidirectional"))
    )
    (net (code "333") (name "unconnected-(U2G-GPIO153-PadA12)") (class "Default")
      (node (ref "U2") (pin "A12") (pinfunction "GPIO153_A12") (pintype "bidirectional"))
    )
    (net (code "334") (name "unconnected-(U2G-GPIO154-PadB12)") (class "Default")
      (node (ref "U2") (pin "B12") (pinfunction "GPIO154_B12") (pintype "bidirectional"))
    )
    (net (code "335") (name "unconnected-(U2G-GPIO155-PadC12)") (class "Default")
      (node (ref "U2") (pin "C12") (pinfunction "GPIO155_C12") (pintype "bidirectional"))
    )
    (net (code "336") (name "unconnected-(U2G-GPIO156-PadD12)") (class "Default")
      (node (ref "U2") (pin "D12") (pinfunction "GPIO156_D12") (pintype "bidirectional"))
    )
    (net (code "337") (name "unconnected-(U2G-GPIO157-PadB10)") (class "Default")
      (node (ref "U2") (pin "B10") (pinfunction "GPIO157_B10") (pintype "bidirectional"))
    )
    (net (code "338") (name "unconnected-(U2G-GPIO158-PadC10)") (class "Default")
      (node (ref "U2") (pin "C10") (pinfunction "GPIO158_C10") (pintype "bidirectional"))
    )
    (net (code "339") (name "unconnected-(U2G-GPIO159-PadD10)") (class "Default")
      (node (ref "U2") (pin "D10") (pinfunction "GPIO159_D10") (pintype "bidirectional"))
    )
    (net (code "340") (name "unconnected-(U2G-GPIO160-PadB9)") (class "Default")
      (node (ref "U2") (pin "B9") (pinfunction "GPIO160_B9") (pintype "bidirectional"))
    )
    (net (code "341") (name "unconnected-(U2G-GPIO161-PadC9)") (class "Default")
      (node (ref "U2") (pin "C9") (pinfunction "GPIO161_C9") (pintype "bidirectional"))
    )
    (net (code "342") (name "unconnected-(U2G-GPIO162-PadD9)") (class "Default")
      (node (ref "U2") (pin "D9") (pinfunction "GPIO162_D9") (pintype "bidirectional"))
    )
    (net (code "343") (name "unconnected-(U2G-GPIO163-PadA8)") (class "Default")
      (node (ref "U2") (pin "A8") (pinfunction "GPIO163_A8") (pintype "bidirectional"))
    )
    (net (code "344") (name "unconnected-(U2G-GPIO164-PadB8)") (class "Default")
      (node (ref "U2") (pin "B8") (pinfunction "GPIO164_B8") (pintype "bidirectional"))
    )
    (net (code "345") (name "unconnected-(U2G-GPIO165-PadC5)") (class "Default")
      (node (ref "U2") (pin "C5") (pinfunction "GPIO165_C5") (pintype "bidirectional"))
    )
    (net (code "346") (name "unconnected-(U2G-GPIO166-PadD5)") (class "Default")
      (node (ref "U2") (pin "D5") (pinfunction "GPIO166_D5") (pintype "bidirectional"))
    )
    (net (code "347") (name "unconnected-(U2G-GPIO167-PadC4)") (class "Default")
      (node (ref "U2") (pin "C4") (pinfunction "GPIO167_C4") (pintype "bidirectional"))
    )
    (net (code "348") (name "unconnected-(U2G-GPIO168-PadD4)") (class "Default")
      (node (ref "U2") (pin "D4") (pinfunction "GPIO168_D4") (pintype "bidirectional"))
    )
    (net (code "349") (name "unconnected-(U3-PA6-Pad23)") (class "Default")
      (node (ref "U3") (pin "23") (pinfunction "PA6_23") (pintype "bidirectional"))
    )
    (net (code "350") (name "unconnected-(U3-PA7-Pad24)") (class "Default")
      (node (ref "U3") (pin "24") (pinfunction "PA7_24") (pintype "bidirectional"))
    )
    (net (code "351") (name "unconnected-(U3-PB0-Pad45)") (class "Default")
      (node (ref "U3") (pin "45") (pinfunction "PB0_45") (pintype "bidirectional"))
    )
    (net (code "352") (name "unconnected-(U3-PB1-Pad46)") (class "Default")
      (node (ref "U3") (pin "46") (pinfunction "PB1_46") (pintype "bidirectional"))
    )
    (net (code "353") (name "unconnected-(U3-PC4-Pad16)") (class "Default")
      (node (ref "U3") (pin "16") (pinfunction "PC4_16") (pintype "bidirectional"))
    )
    (net (code "354") (name "unconnected-(U3-PC5-Pad15)") (class "Default")
      (node (ref "U3") (pin "15") (pinfunction "PC5_15") (pintype "bidirectional"))
    )
    (net (code "355") (name "unconnected-(U3-PC6-Pad14)") (class "Default")
      (node (ref "U3") (pin "14") (pinfunction "PC6_14") (pintype "bidirectional"))
    )
    (net (code "356") (name "unconnected-(U3-PC7-Pad13)") (class "Default")
      (node (ref "U3") (pin "13") (pinfunction "PC7_13") (pintype "bidirectional"))
    )
    (net (code "357") (name "unconnected-(U3-PD0-Pad61)") (class "Default")
      (node (ref "U3") (pin "61") (pinfunction "PD0_61") (pintype "bidirectional"))
    )
    (net (code "358") (name "unconnected-(U3-PD1-Pad62)") (class "Default")
      (node (ref "U3") (pin "62") (pinfunction "PD1_62") (pintype "bidirectional"))
    )
    (net (code "359") (name "unconnected-(U3-PD2-Pad63)") (class "Default")
      (node (ref "U3") (pin "63") (pinfunction "PD2_63") (pintype "bidirectional"))
    )
    (net (code "360") (name "unconnected-(U3-PD3-Pad64)") (class "Default")
      (node (ref "U3") (pin "64") (pinfunction "PD3_64") (pintype "bidirectional"))
    )
    (net (code "361") (name "unconnected-(U3-PD4-Pad43)") (class "Default")
      (node (ref "U3") (pin "43") (pinfunction "PD4_43") (pintype "bidirectional"))
    )
    (net (code "362") (name "unconnected-(U3-PD5-Pad44)") (class "Default")
      (node (ref "U3") (pin "44") (pinfunction "PD5_44") (pintype "bidirectional"))
    )
    (net (code "363") (name "unconnected-(U3-PE0-Pad9)") (class "Default")
      (node (ref "U3") (pin "9") (pinfunction "PE0_9") (pintype "bidirectional"))
    )
    (net (code "364") (name "unconnected-(U3-PE1-Pad8)") (class "Default")
      (node (ref "U3") (pin "8") (pinfunction "PE1_8") (pintype "bidirectional"))
    )
    (net (code "365") (name "unconnected-(U3-PE2-Pad7)") (class "Default")
      (node (ref "U3") (pin "7") (pinfunction "PE2_7") (pintype "bidirectional"))
    )
    (net (code "366") (name "unconnected-(U3-PE3-Pad6)") (class "Default")
      (node (ref "U3") (pin "6") (pinfunction "PE3_6") (pintype "bidirectional"))
    )
    (net (code "367") (name "unconnected-(U3-PE4-Pad59)") (class "Default")
      (node (ref "U3") (pin "59") (pinfunction "PE4_59") (pintype "bidirectional"))
    )
    (net (code "368") (name "unconnected-(U3-PE5-Pad60)") (class "Default")
      (node (ref "U3") (pin "60") (pinfunction "PE5_60") (pintype "bidirectional"))
    )
    (net (code "369") (name "unconnected-(U3-PG0-Pad37)") (class "Default")
      (node (ref "U3") (pin "37") (pinfunction "PG0_37") (pintype "bidirectional"))
    )
    (net (code "370") (name "unconnected-(U3-PG1-Pad36)") (class "Default")
      (node (ref "U3") (pin "36") (pinfunction "PG1_36") (pintype "bidirectional"))
    )
    (net (code "371") (name "unconnected-(U3-PG2-Pad35)") (class "Default")
      (node (ref "U3") (pin "35") (pinfunction "PG2_35") (pintype "bidirectional"))
    )
    (net (code "372") (name "unconnected-(U3-PG3-Pad34)") (class "Default")
      (node (ref "U3") (pin "34") (pinfunction "PG3_34") (pintype "bidirectional"))
    )
    (net (code "373") (name "unconnected-(U3-PG4-Pad33)") (class "Default")
      (node (ref "U3") (pin "33") (pinfunction "PG4_33") (pintype "bidirectional"))
    )
    (net (code "374") (name "unconnected-(U3-PG5-Pad32)") (class "Default")
      (node (ref "U3") (pin "32") (pinfunction "PG5_32") (pintype "bidirectional"))
    )
    (net (code "375") (name "unconnected-(U6-NC-PadE2)") (class "Default")
      (node (ref "U6") (pin "E2") (pinfunction "NC_E2") (pintype "bidirectional"))
    )
    (net (code "376") (name "unconnected-(U7-ADR0-PadP$5)") (class "Default")
      (node (ref "U7") (pin "P$5") (pinfunction "ADR0_P$5") (pintype "bidirectional"))
    )
    (net (code "377") (name "unconnected-(U10-NC-Pad11)") (class "Default")
      (node (ref "U10") (pin "11") (pinfunction "NC_11") (pintype "passive"))
    )
    (net (code "378") (name "unconnected-(U11-NC-Pad11)") (class "Default")
      (node (ref "U11") (pin "11") (pinfunction "NC_11") (pintype "passive"))
    )
    (net (code "379") (name "unconnected-(U19-DNC-Pad26)") (class "Default")
      (node (ref "U19") (pin "26") (pinfunction "DNC_26") (pintype "no_connect"))
    )
    (net (code "380") (name "unconnected-(U19-NC-Pad18)") (class "Default")
      (node (ref "U19") (pin "18") (pinfunction "NC_18") (pintype "no_connect"))
    )
    (net (code "381") (name "unconnected-(U19-NC_2-Pad5)") (class "Default")
      (node (ref "U19") (pin "5") (pinfunction "NC_2_5") (pintype "no_connect"))
    )
    (net (code "382") (name "unconnected-(U20-GPIO0-Pad10)") (class "Default")
      (node (ref "U20") (pin "10") (pinfunction "GPIO0_10") (pintype "bidirectional"))
    )
    (net (code "383") (name "unconnected-(U20-GPIO2-Pad4)") (class "Default")
      (node (ref "U20") (pin "4") (pinfunction "GPIO2_4") (pintype "bidirectional"))
    )
    (net (code "384") (name "unconnected-(U20-GPIO3-Pad3)") (class "Default")
      (node (ref "U20") (pin "3") (pinfunction "GPIO3_3") (pintype "bidirectional"))
    )
    (net (code "385") (name "unconnected-(U20-NC-Pad16)") (class "Default")
      (node (ref "U20") (pin "16") (pinfunction "NC_16") (pintype "passive"))
    )
    (net (code "386") (name "unconnected-(U21-PA6-Pad23)") (class "Default")
      (node (ref "U21") (pin "23") (pinfunction "PA6_23") (pintype "bidirectional"))
    )
    (net (code "387") (name "unconnected-(U21-PA7-Pad24)") (class "Default")
      (node (ref "U21") (pin "24") (pinfunction "PA7_24") (pintype "bidirectional"))
    )
    (net (code "388") (name "unconnected-(U21-PB0-Pad45)") (class "Default")
      (node (ref "U21") (pin "45") (pinfunction "PB0_45") (pintype "bidirectional"))
    )
    (net (code "389") (name "unconnected-(U21-PB1-Pad46)") (class "Default")
      (node (ref "U21") (pin "46") (pinfunction "PB1_46") (pintype "bidirectional"))
    )
    (net (code "390") (name "unconnected-(U21-PC4-Pad16)") (class "Default")
      (node (ref "U21") (pin "16") (pinfunction "PC4_16") (pintype "bidirectional"))
    )
    (net (code "391") (name "unconnected-(U21-PC5-Pad15)") (class "Default")
      (node (ref "U21") (pin "15") (pinfunction "PC5_15") (pintype "bidirectional"))
    )
    (net (code "392") (name "unconnected-(U21-PC6-Pad14)") (class "Default")
      (node (ref "U21") (pin "14") (pinfunction "PC6_14") (pintype "bidirectional"))
    )
    (net (code "393") (name "unconnected-(U21-PC7-Pad13)") (class "Default")
      (node (ref "U21") (pin "13") (pinfunction "PC7_13") (pintype "bidirectional"))
    )
    (net (code "394") (name "unconnected-(U21-PD0-Pad61)") (class "Default")
      (node (ref "U21") (pin "61") (pinfunction "PD0_61") (pintype "bidirectional"))
    )
    (net (code "395") (name "unconnected-(U21-PD1-Pad62)") (class "Default")
      (node (ref "U21") (pin "62") (pinfunction "PD1_62") (pintype "bidirectional"))
    )
    (net (code "396") (name "unconnected-(U21-PD2-Pad63)") (class "Default")
      (node (ref "U21") (pin "63") (pinfunction "PD2_63") (pintype "bidirectional"))
    )
    (net (code "397") (name "unconnected-(U21-PD3-Pad64)") (class "Default")
      (node (ref "U21") (pin "64") (pinfunction "PD3_64") (pintype "bidirectional"))
    )
    (net (code "398") (name "unconnected-(U21-PD4-Pad43)") (class "Default")
      (node (ref "U21") (pin "43") (pinfunction "PD4_43") (pintype "bidirectional"))
    )
    (net (code "399") (name "unconnected-(U21-PD5-Pad44)") (class "Default")
      (node (ref "U21") (pin "44") (pinfunction "PD5_44") (pintype "bidirectional"))
    )
    (net (code "400") (name "unconnected-(U21-PE0-Pad9)") (class "Default")
      (node (ref "U21") (pin "9") (pinfunction "PE0_9") (pintype "bidirectional"))
    )
    (net (code "401") (name "unconnected-(U21-PE1-Pad8)") (class "Default")
      (node (ref "U21") (pin "8") (pinfunction "PE1_8") (pintype "bidirectional"))
    )
    (net (code "402") (name "unconnected-(U21-PE2-Pad7)") (class "Default")
      (node (ref "U21") (pin "7") (pinfunction "PE2_7") (pintype "bidirectional"))
    )
    (net (code "403") (name "unconnected-(U21-PE3-Pad6)") (class "Default")
      (node (ref "U21") (pin "6") (pinfunction "PE3_6") (pintype "bidirectional"))
    )
    (net (code "404") (name "unconnected-(U21-PE4-Pad59)") (class "Default")
      (node (ref "U21") (pin "59") (pinfunction "PE4_59") (pintype "bidirectional"))
    )
    (net (code "405") (name "unconnected-(U21-PE5-Pad60)") (class "Default")
      (node (ref "U21") (pin "60") (pinfunction "PE5_60") (pintype "bidirectional"))
    )
    (net (code "406") (name "unconnected-(U21-PG0-Pad37)") (class "Default")
      (node (ref "U21") (pin "37") (pinfunction "PG0_37") (pintype "bidirectional"))
    )
    (net (code "407") (name "unconnected-(U21-PG1-Pad36)") (class "Default")
      (node (ref "U21") (pin "36") (pinfunction "PG1_36") (pintype "bidirectional"))
    )
    (net (code "408") (name "unconnected-(U21-PG2-Pad35)") (class "Default")
      (node (ref "U21") (pin "35") (pinfunction "PG2_35") (pintype "bidirectional"))
    )
    (net (code "409") (name "unconnected-(U21-PG3-Pad34)") (class "Default")
      (node (ref "U21") (pin "34") (pinfunction "PG3_34") (pintype "bidirectional"))
    )
    (net (code "410") (name "unconnected-(U21-PG4-Pad33)") (class "Default")
      (node (ref "U21") (pin "33") (pinfunction "PG4_33") (pintype "bidirectional"))
    )
    (net (code "411") (name "unconnected-(U21-PG5-Pad32)") (class "Default")
      (node (ref "U21") (pin "32") (pinfunction "PG5_32") (pintype "bidirectional"))
    )
    (net (code "412") (name "unconnected-(X3H-KL-Pad7)") (class "Default")
      (node (ref "X3") (pin "7") (pinfunction "KL_7") (pintype "passive"))
    )
    (net (code "413") (name "unconnected-(X4H-KL-Pad7)") (class "Default")
      (node (ref "X4") (pin "7") (pinfunction "KL_7") (pintype "passive"))
    )
    (net (code "414") (name "unconnected-(X5B-KL-Pad10)") (class "Default")
      (node (ref "X5") (pin "10") (pinfunction "KL_10") (pintype "passive"))
    )
    (net (code "415") (name "unconnected-(X5H-KL-Pad7)") (class "Default")
      (node (ref "X5") (pin "7") (pinfunction "KL_7") (pintype "passive"))
    )
    (net (code "416") (name "unconnected-(X8H-KL-Pad7)") (class "Default")
      (node (ref "X8") (pin "7") (pinfunction "KL_7") (pintype "passive"))
    )
    (net (code "417") (name "~{ADCS_FAILURE}") (class "Default")
      (node (ref "C184") (pin "1") (pinfunction "1_1") (pintype "bidirectional"))
      (node (ref "IC1") (pin "2") (pinfunction "I/O_1_2") (pintype "bidirectional"))
      (node (ref "R42") (pin "2") (pinfunction "2_2") (pintype "bidirectional"))
    )
    (net (code "418") (name "~{CC1200_1_RESET}") (class "Default")
      (node (ref "C51") (pin "1") (pinfunction "1_1") (pintype "bidirectional"))
      (node (ref "R34") (pin "2") (pinfunction "2_2") (pintype "bidirectional"))
      (node (ref "U1") (pin "2") (pinfunction "RESET_N_2") (pintype "input"))
      (node (ref "U3") (pin "4") (pinfunction "PB7_4") (pintype "bidirectional"))
    )
    (net (code "419") (name "~{CC1200_1_SPI_CS}") (class "Default")
      (node (ref "U1") (pin "11") (pinfunction "CS_N_11") (pintype "input"))
      (node (ref "U3") (pin "20") (pinfunction "PA3_SSI0FSS_20") (pintype "bidirectional"))
    )
    (net (code "420") (name "~{CC1200_2_RESET}") (class "Default")
      (node (ref "C215") (pin "1") (pinfunction "1_1") (pintype "bidirectional"))
      (node (ref "R78") (pin "2") (pinfunction "2_2") (pintype "bidirectional"))
      (node (ref "U20") (pin "2") (pinfunction "RESET_N_2") (pintype "input"))
      (node (ref "U21") (pin "4") (pinfunction "PB7_4") (pintype "bidirectional"))
    )
    (net (code "421") (name "~{CC1200_2_SPI_CS}") (class "Default")
      (node (ref "U20") (pin "11") (pinfunction "CS_N_11") (pintype "input"))
      (node (ref "U21") (pin "20") (pinfunction "PA3_SSI0FSS_20") (pintype "bidirectional"))
    )
    (net (code "422") (name "~{COMMS1_ERROR}") (class "Default")
      (node (ref "IC1") (pin "14") (pinfunction "I/O_9_14") (pintype "bidirectional"))
      (node (ref "R61") (pin "2") (pinfunction "2_2") (pintype "bidirectional"))
      (node (ref "U3") (pin "53") (pinfunction "PD6_53") (pintype "bidirectional"))
    )
    (net (code "423") (name "~{COMMS1_JTAG_RST}") (class "Default")
      (node (ref "C32") (pin "1") (pinfunction "1_1") (pintype "bidirectional"))
      (node (ref "R5") (pin "2") (pinfunction "2_2") (pintype "bidirectional"))
      (node (ref "R7") (pin "2") (pinfunction "2_2") (pintype "bidirectional"))
      (node (ref "U5") (pin "6") (pinfunction "C_6") (pintype "input"))
    )
    (net (code "424") (name "~{COMMS1_NAND_CS}") (class "Default")
      (node (ref "U15") (pin "1") (pinfunction "~{CS}_1") (pintype "bidirectional"))
      (node (ref "U3") (pin "31") (pinfunction "PF3_31") (pintype "bidirectional"))
    )
    (net (code "425") (name "~{COMMS1_RESET}") (class "Default")
      (node (ref "C3") (pin "1") (pinfunction "1_1") (pintype "bidirectional"))
      (node (ref "IC1") (pin "5") (pinfunction "I/O_3_5") (pintype "bidirectional"))
      (node (ref "R6") (pin "2") (pinfunction "2_2") (pintype "bidirectional"))
      (node (ref "U5") (pin "1") (pinfunction "A_1") (pintype "input"))
    )
    (net (code "426") (name "~{COMMS1_UNRESPONSIVE_FROM_SMC}") (class "Default")
      (node (ref "IC1") (pin "18") (pinfunction "I/O_11_18") (pintype "bidirectional"))
      (node (ref "R62") (pin "2") (pinfunction "2_2") (pintype "bidirectional"))
      (node (ref "U2") (pin "F2") (pinfunction "GPIO20_F2") (pintype "bidirectional"))
    )
    (net (code "427") (name "~{COMMS2_ERROR}") (class "Default")
      (node (ref "IC1") (pin "16") (pinfunction "I/O_10_16") (pintype "bidirectional"))
      (node (ref "R92") (pin "2") (pinfunction "2_2") (pintype "bidirectional"))
      (node (ref "U21") (pin "53") (pinfunction "PD6_53") (pintype "bidirectional"))
    )
    (net (code "428") (name "~{COMMS2_JTAG_RST}") (class "Default")
      (node (ref "C237") (pin "1") (pinfunction "1_1") (pintype "bidirectional"))
      (node (ref "R81") (pin "2") (pinfunction "2_2") (pintype "bidirectional"))
      (node (ref "R83") (pin "2") (pinfunction "2_2") (pintype "bidirectional"))
      (node (ref "U23") (pin "6") (pinfunction "C_6") (pintype "input"))
    )
    (net (code "429") (name "~{COMMS2_NAND_CS}") (class "Default")
      (node (ref "U21") (pin "31") (pinfunction "PF3_31") (pintype "bidirectional"))
      (node (ref "U24") (pin "1") (pinfunction "~{CS}_1") (pintype "bidirectional"))
    )
    (net (code "430") (name "~{COMMS2_RESET}") (class "Default")
      (node (ref "C240") (pin "1") (pinfunction "1_1") (pintype "bidirectional"))
      (node (ref "IC1") (pin "6") (pinfunction "I/O_4_6") (pintype "bidirectional"))
      (node (ref "R82") (pin "2") (pinfunction "2_2") (pintype "bidirectional"))
      (node (ref "U23") (pin "1") (pinfunction "A_1") (pintype "input"))
    )
    (net (code "431") (name "~{COMMS2_UNRESPONSIVE_FROM_SMC}") (class "Default")
      (node (ref "IC1") (pin "19") (pinfunction "I/O_12_19") (pintype "bidirectional"))
      (node (ref "R63") (pin "2") (pinfunction "2_2") (pintype "bidirectional"))
      (node (ref "U2") (pin "F3") (pinfunction "GPIO21_F3") (pintype "bidirectional"))
    )
    (net (code "432") (name "~{GLOBAL_RESET}") (class "Default")
      (node (ref "C118") (pin "1") (pinfunction "1_1") (pintype "bidirectional"))
      (node (ref "C241") (pin "1") (pinfunction "1_1") (pintype "bidirectional"))
      (node (ref "C4") (pin "1") (pinfunction "1_1") (pintype "bidirectional"))
      (node (ref "IC1") (pin "44") (pinfunction "I/O/GCK2_44") (pintype "bidirectional"))
      (node (ref "R2") (pin "2") (pinfunction "2_2") (pintype "bidirectional"))
      (node (ref "R4") (pin "2") (pinfunction "2_2") (pintype "bidirectional"))
      (node (ref "R86") (pin "2") (pinfunction "2_2") (pintype "bidirectional"))
      (node (ref "U2") (pin "F19") (pinfunction "XRS_N_F19") (pintype "bidirectional"))
      (node (ref "U23") (pin "3") (pinfunction "B_3") (pintype "input"))
      (node (ref "U5") (pin "3") (pinfunction "B_3") (pintype "input"))
    )
    (net (code "433") (name "~{MTQ_12_FAULT}") (class "Default")
      (node (ref "R14") (pin "2") (pinfunction "2_2") (pintype "bidirectional"))
      (node (ref "U10") (pin "8") (pinfunction "FAULT_N_8") (pintype "open_collector"))
      (node (ref "U2") (pin "C11") (pinfunction "GPIO86_C11") (pintype "bidirectional"))
    )
    (net (code "434") (name "~{MTQ_12_SLEEP}") (class "Default")
      (node (ref "R13") (pin "2") (pinfunction "2_2") (pintype "bidirectional"))
      (node (ref "U10") (pin "1") (pinfunction "SLEEP_N_1") (pintype "input"))
      (node (ref "U2") (pin "B11") (pinfunction "GPIO85_B11") (pintype "bidirectional"))
    )
    (net (code "435") (name "~{MTQ_34_FAULT}") (class "Default")
      (node (ref "R22") (pin "2") (pinfunction "2_2") (pintype "bidirectional"))
      (node (ref "U11") (pin "8") (pinfunction "FAULT_N_8") (pintype "open_collector"))
      (node (ref "U2") (pin "D6") (pinfunction "GPIO89_D6") (pintype "bidirectional"))
    )
    (net (code "436") (name "~{MTQ_34_SLEEP}") (class "Default")
      (node (ref "R21") (pin "2") (pinfunction "2_2") (pintype "bidirectional"))
      (node (ref "U11") (pin "1") (pinfunction "SLEEP_N_1") (pintype "input"))
      (node (ref "U2") (pin "C6") (pinfunction "GPIO88_C6") (pintype "bidirectional"))
    )
    (net (code "437") (name "~{SDRAM_CAS}") (class "Default")
      (node (ref "U2") (pin "K4") (pinfunction "GPIO23_K4") (pintype "bidirectional"))
      (node (ref "U6") (pin "F7") (pinfunction "~{CAS}_F7") (pintype "bidirectional"))
    )
    (net (code "438") (name "~{SDRAM_CS}") (class "Default")
      (node (ref "U2") (pin "U13") (pinfunction "GPIO32_U13") (pintype "bidirectional"))
      (node (ref "U6") (pin "G9") (pinfunction "~{CS}_G9") (pintype "bidirectional"))
    )
    (net (code "439") (name "~{SDRAM_RAS}") (class "Default")
      (node (ref "U2") (pin "J4") (pinfunction "GPIO22_J4") (pintype "bidirectional"))
      (node (ref "U6") (pin "F8") (pinfunction "~{RAS}_F8") (pintype "bidirectional"))
    )
    (net (code "440") (name "~{SDRAM_WE}") (class "Default")
      (node (ref "U2") (pin "U11") (pinfunction "GPIO31_U11") (pintype "bidirectional"))
      (node (ref "U6") (pin "F9") (pinfunction "~{WE}_F9") (pintype "bidirectional"))
    )
    (net (code "441") (name "~{SMC_NAND_CS}") (class "Default")
      (node (ref "U16") (pin "1") (pinfunction "~{CS}_1") (pintype "bidirectional"))
      (node (ref "U2") (pin "E4") (pinfunction "GPIO19_E4") (pintype "bidirectional"))
    )
    (net (code "442") (name "~{SMC_TRST}") (class "Default")
      (node (ref "C119") (pin "1") (pinfunction "1_1") (pintype "bidirectional"))
      (node (ref "R10") (pin "1") (pinfunction "1_1") (pintype "bidirectional"))
      (node (ref "U2") (pin "V14") (pinfunction "TRST_N_V14") (pintype "input"))
      (node (ref "X4") (pin "10") (pinfunction "KL_10") (pintype "passive"))
    )
    (net (code "443") (name "~{SMC_UNRESPONSIVE1_PRE}") (class "Default")
      (node (ref "R93") (pin "1") (pinfunction "1_1") (pintype "bidirectional"))
      (node (ref "U3") (pin "5") (pinfunction "PF4_5") (pintype "bidirectional"))
    )
    (net (code "444") (name "~{SMC_UNRESPONSIVE2_PRE}") (class "Default")
      (node (ref "R94") (pin "1") (pinfunction "1_1") (pintype "bidirectional"))
      (node (ref "U21") (pin "5") (pinfunction "PF4_5") (pintype "bidirectional"))
    )
    (net (code "445") (name "~{SMC_UNRESPONSIVE_FROM_COMMS1}") (class "Default")
      (node (ref "IC1") (pin "28") (pinfunction "I/O_18_28") (pintype "bidirectional"))
      (node (ref "R93") (pin "2") (pinfunction "2_2") (pintype "bidirectional"))
      (node (ref "R95") (pin "2") (pinfunction "2_2") (pintype "bidirectional"))
    )
    (net (code "446") (name "~{SMC_UNRESPONSIVE_FROM_COMMS2}") (class "Default")
      (node (ref "IC1") (pin "27") (pinfunction "I/O_17_27") (pintype "bidirectional"))
      (node (ref "R94") (pin "2") (pinfunction "2_2") (pintype "bidirectional"))
      (node (ref "R96") (pin "2") (pinfunction "2_2") (pintype "bidirectional"))
    )
    (net (code "447") (name "~{TPS53513_PGOOD}") (class "Default")
      (node (ref "R68") (pin "2") (pinfunction "2_2") (pintype "bidirectional"))
      (node (ref "R71") (pin "2") (pinfunction "2_2") (pintype "bidirectional"))
      (node (ref "R72") (pin "2") (pinfunction "2_2") (pintype "bidirectional"))
      (node (ref "U19") (pin "2") (pinfunction "PGOOD_2") (pintype "power_in"))
    )
  )
)
